# Sheet_1_2022-11-05.net
KiCad netlist of a schematic drawn in Altium Designer
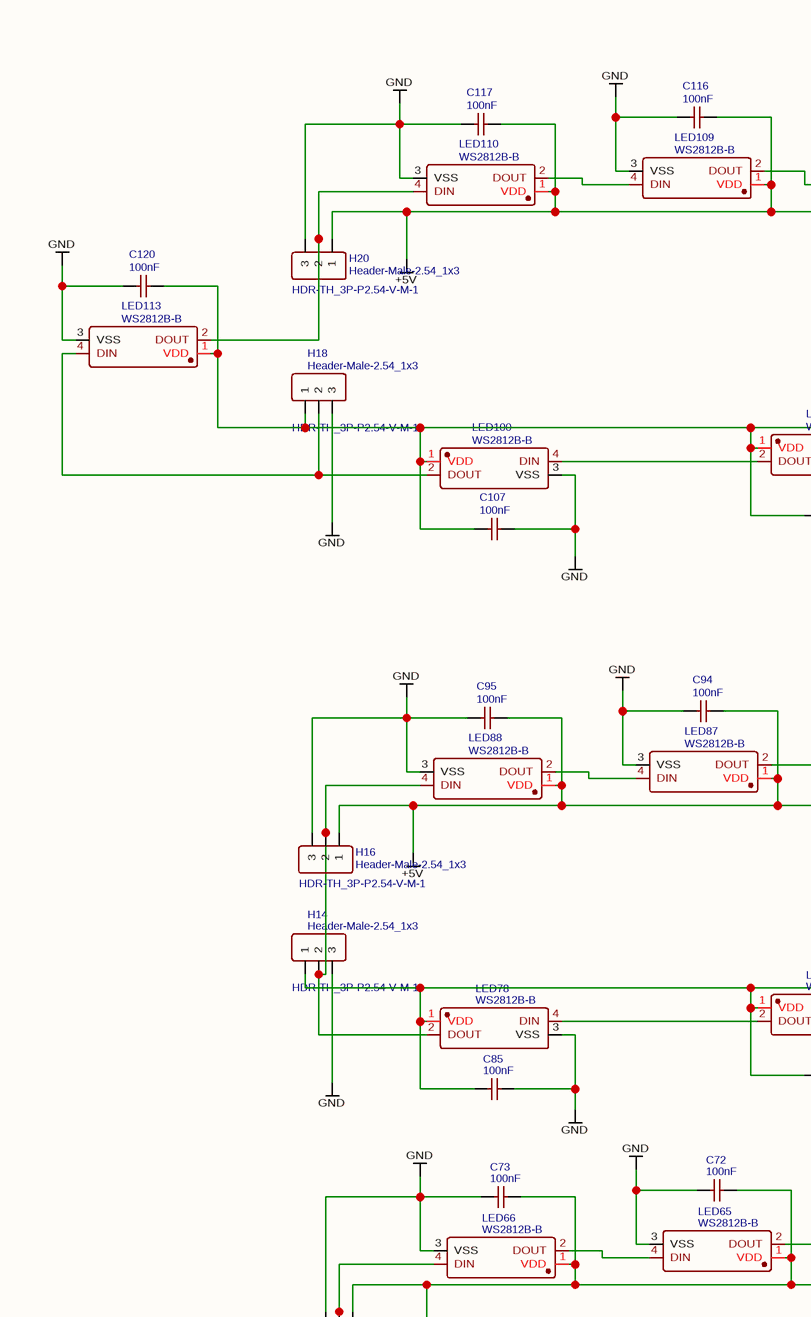
[diagram p0: Sheet_1_2022-11-05.schdoc, top left]
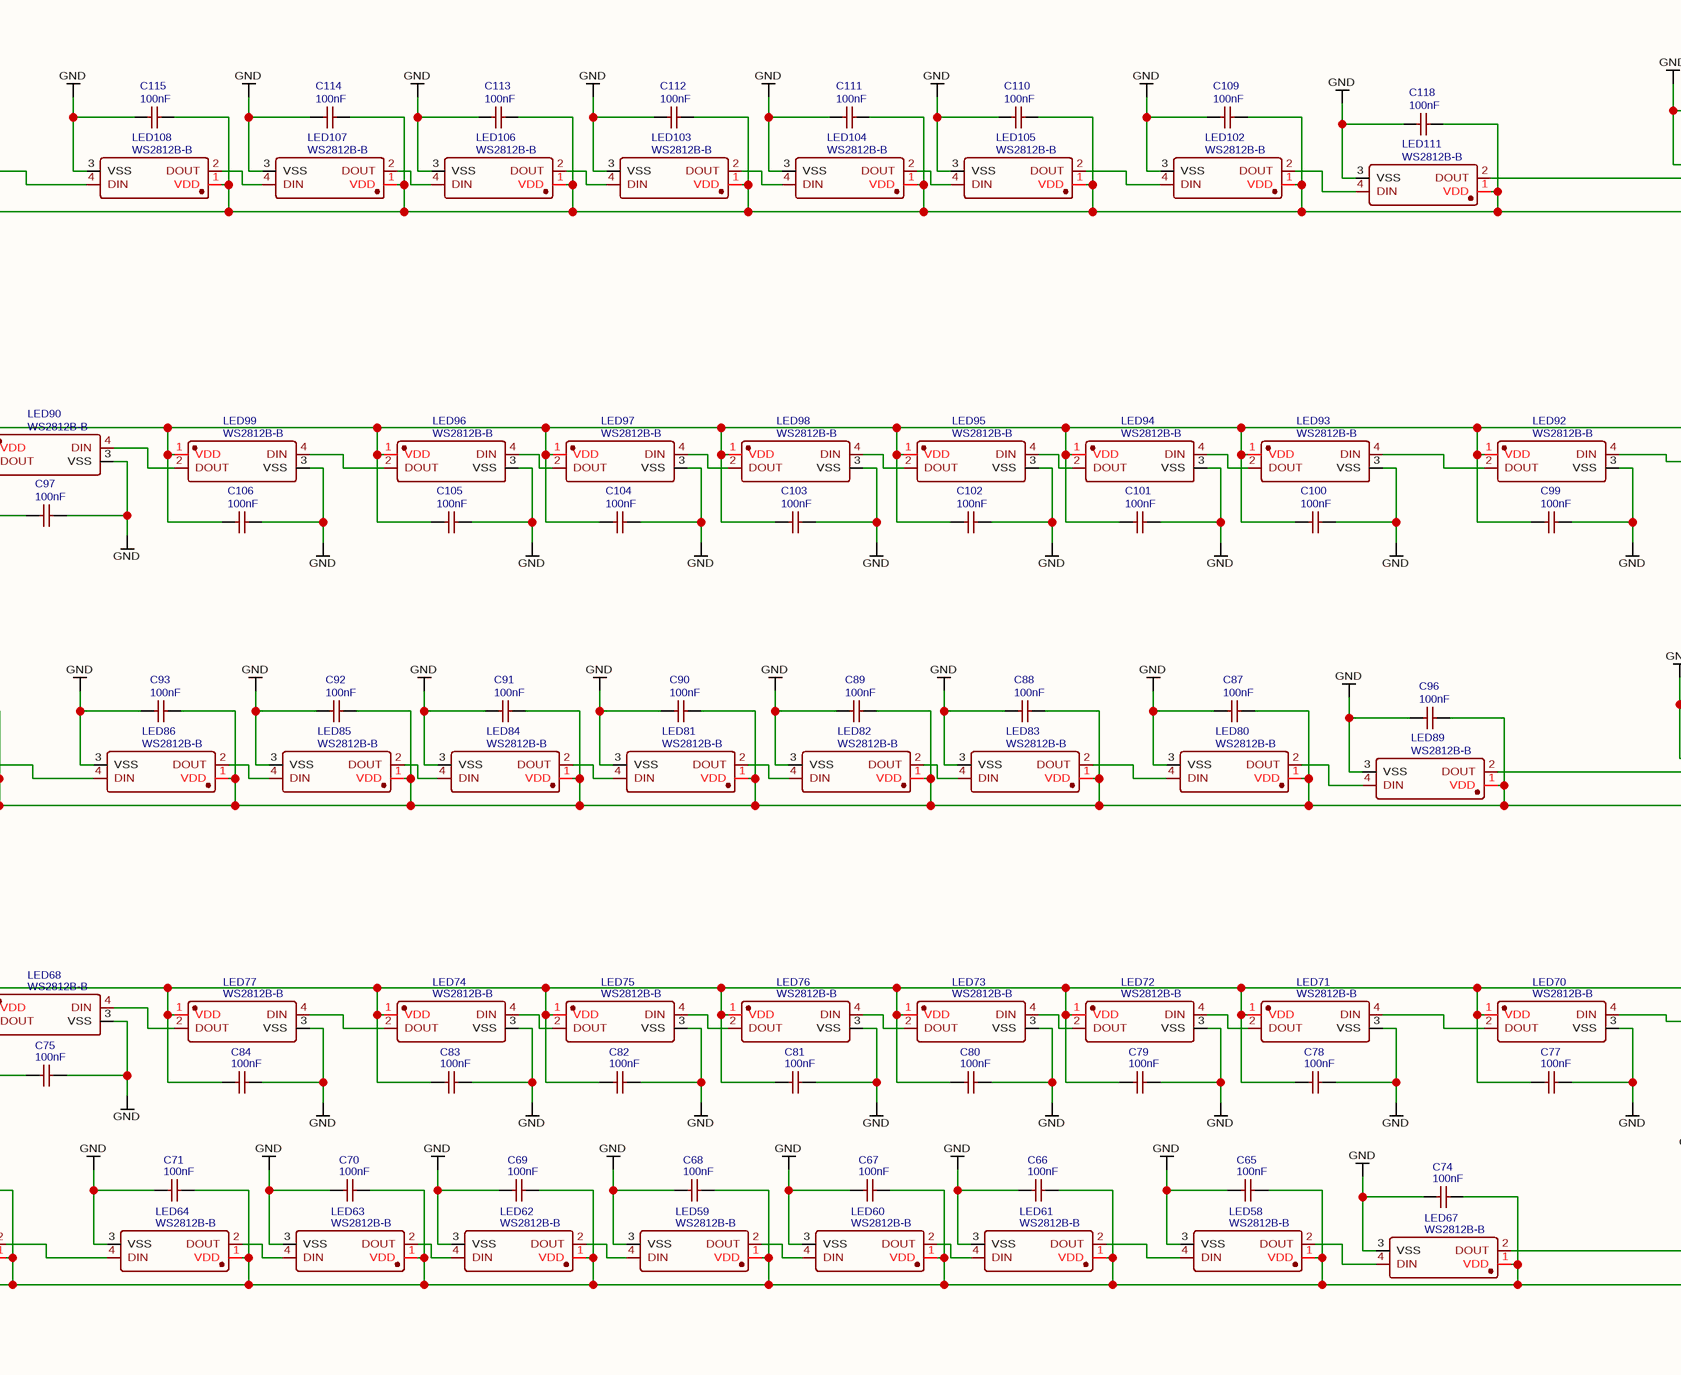
[diagram p1: Sheet_1_2022-11-05.schdoc, top middle]
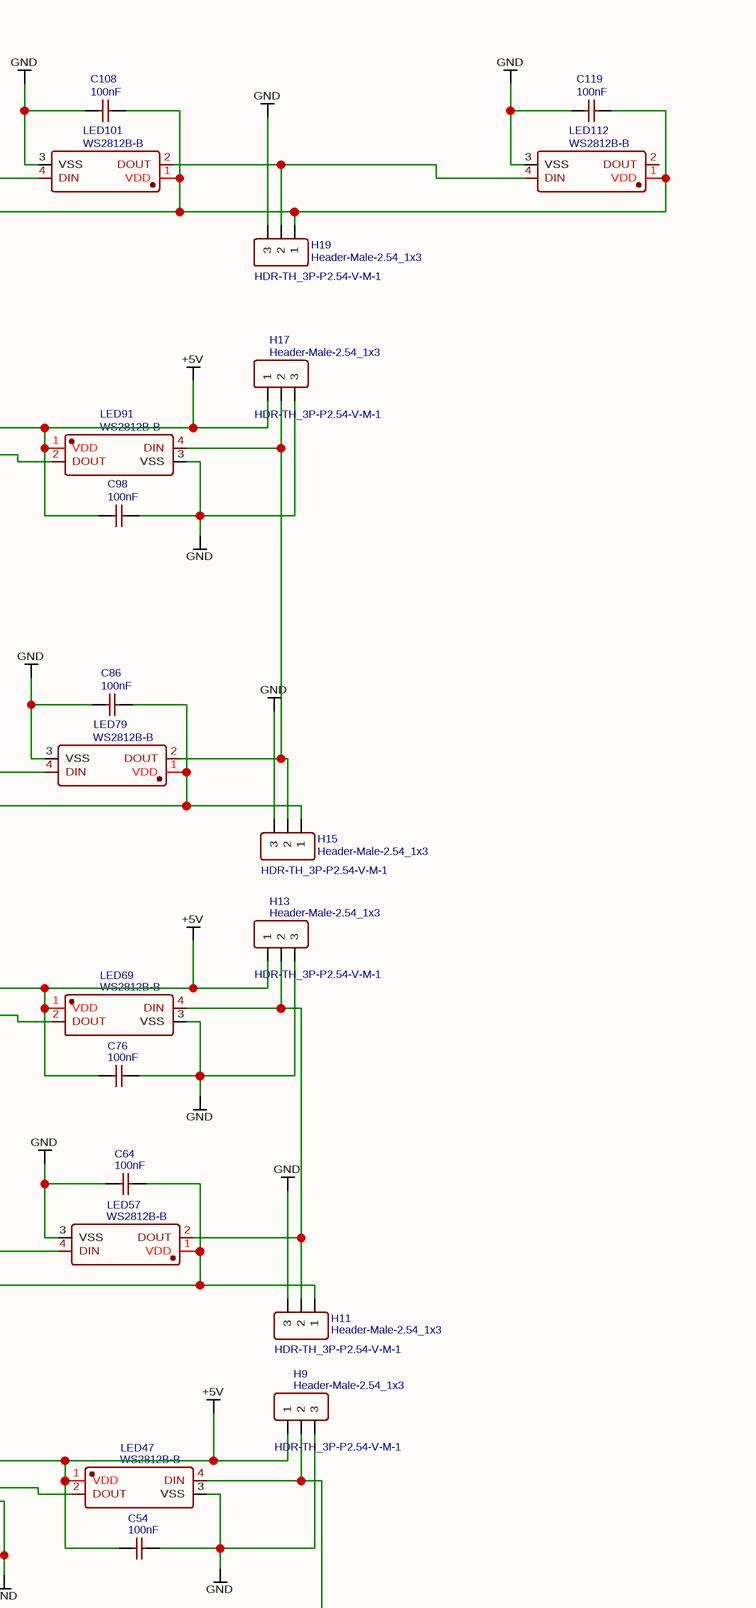
[diagram p2: Sheet_1_2022-11-05.schdoc, top right]
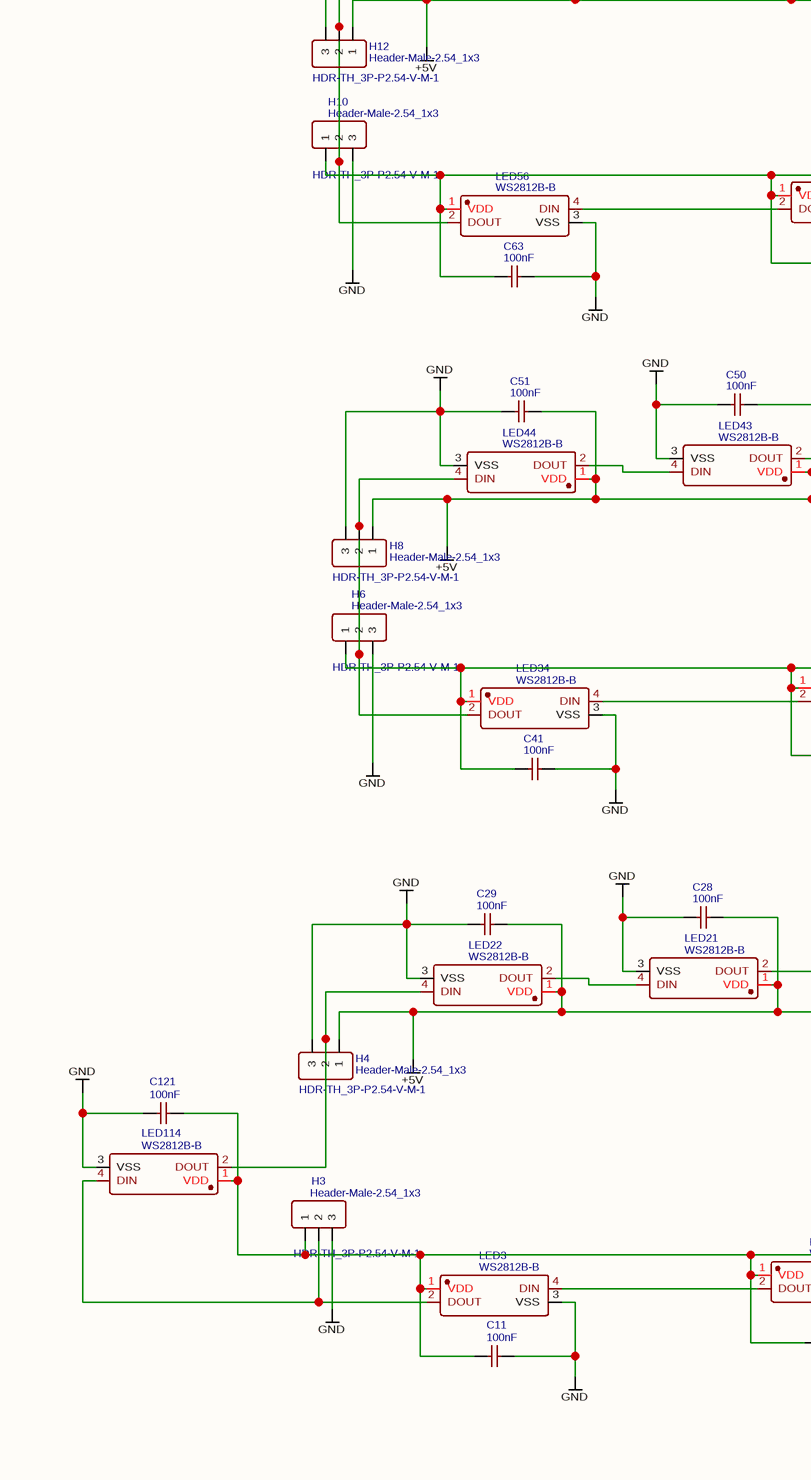
[diagram p3: Sheet_1_2022-11-05.schdoc, centre left]
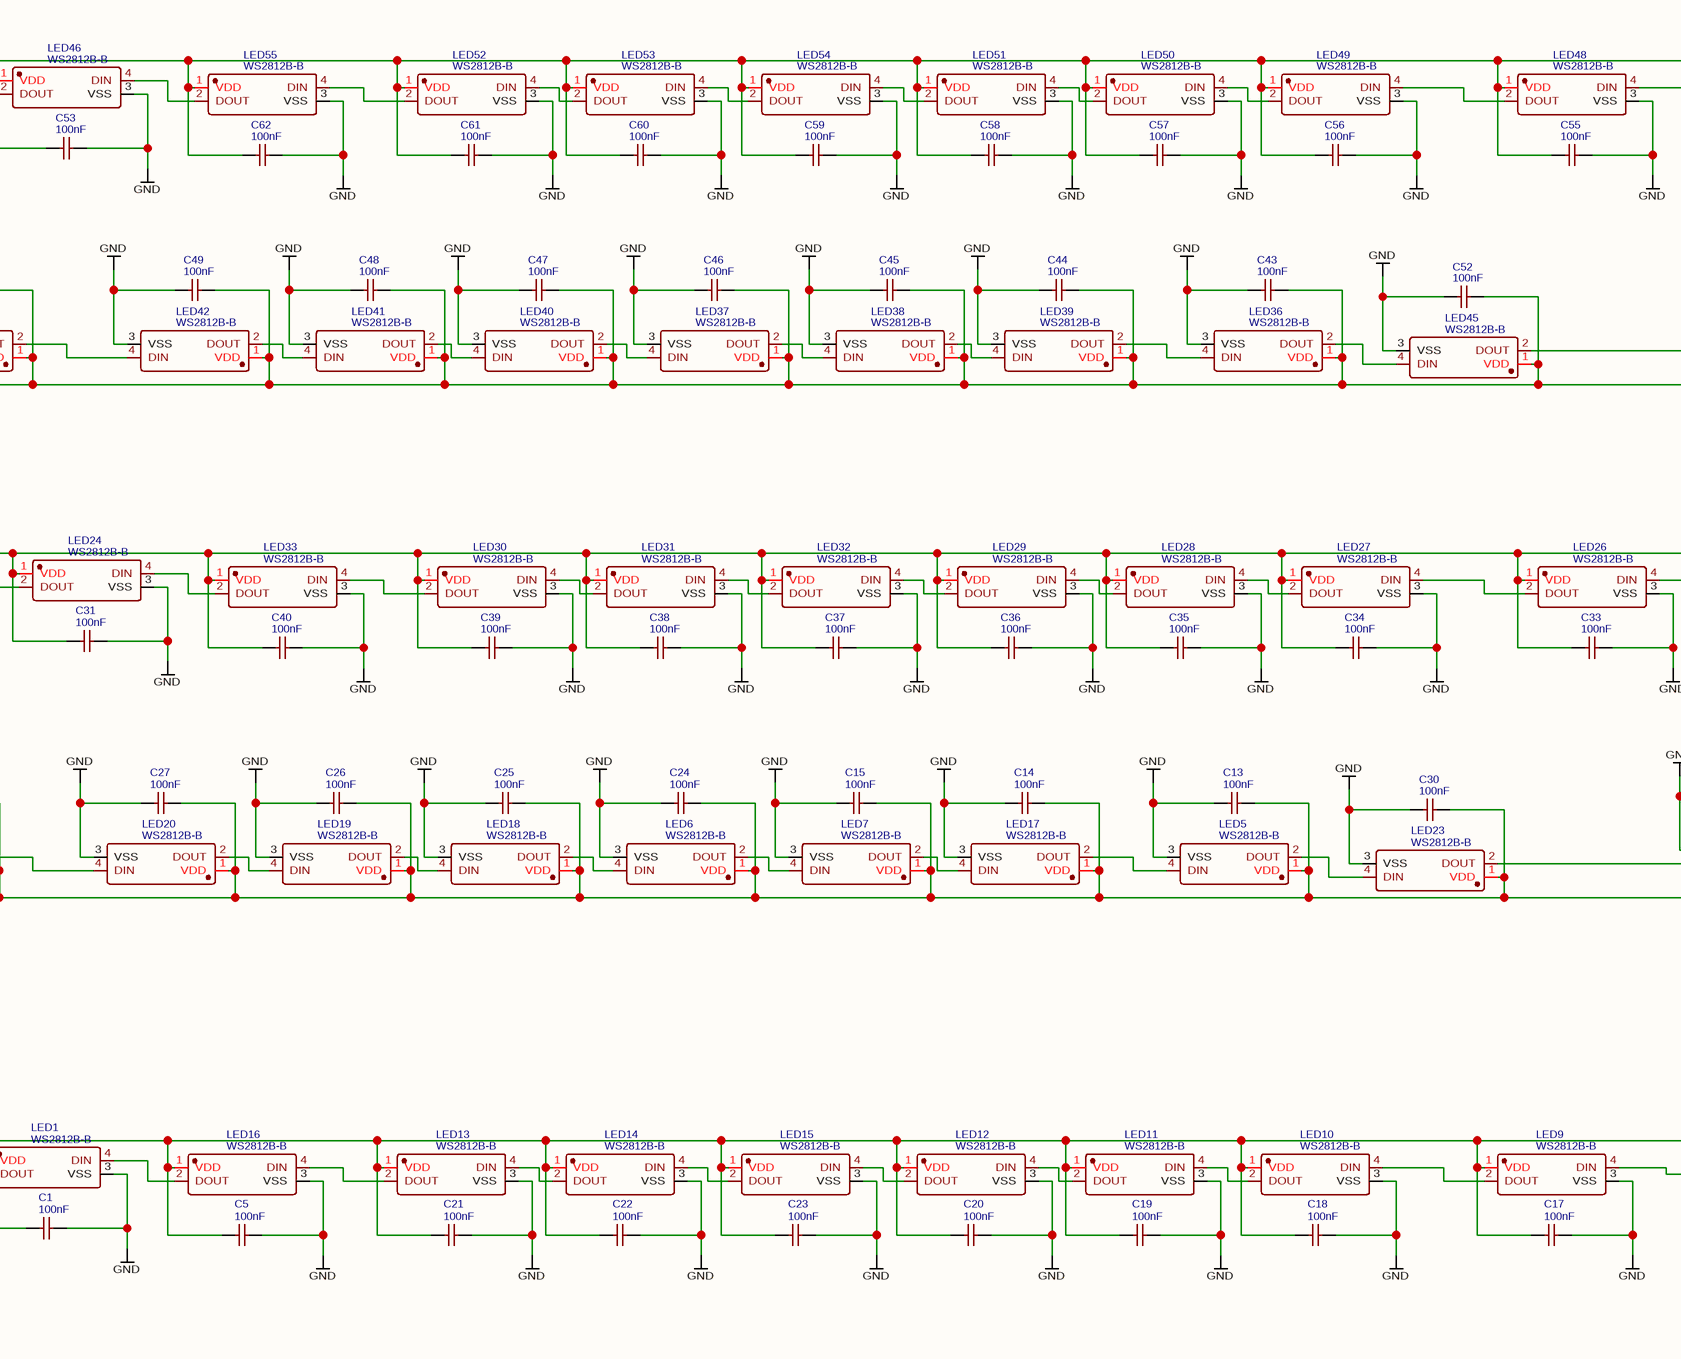
[diagram p4: Sheet_1_2022-11-05.schdoc, centre middle]
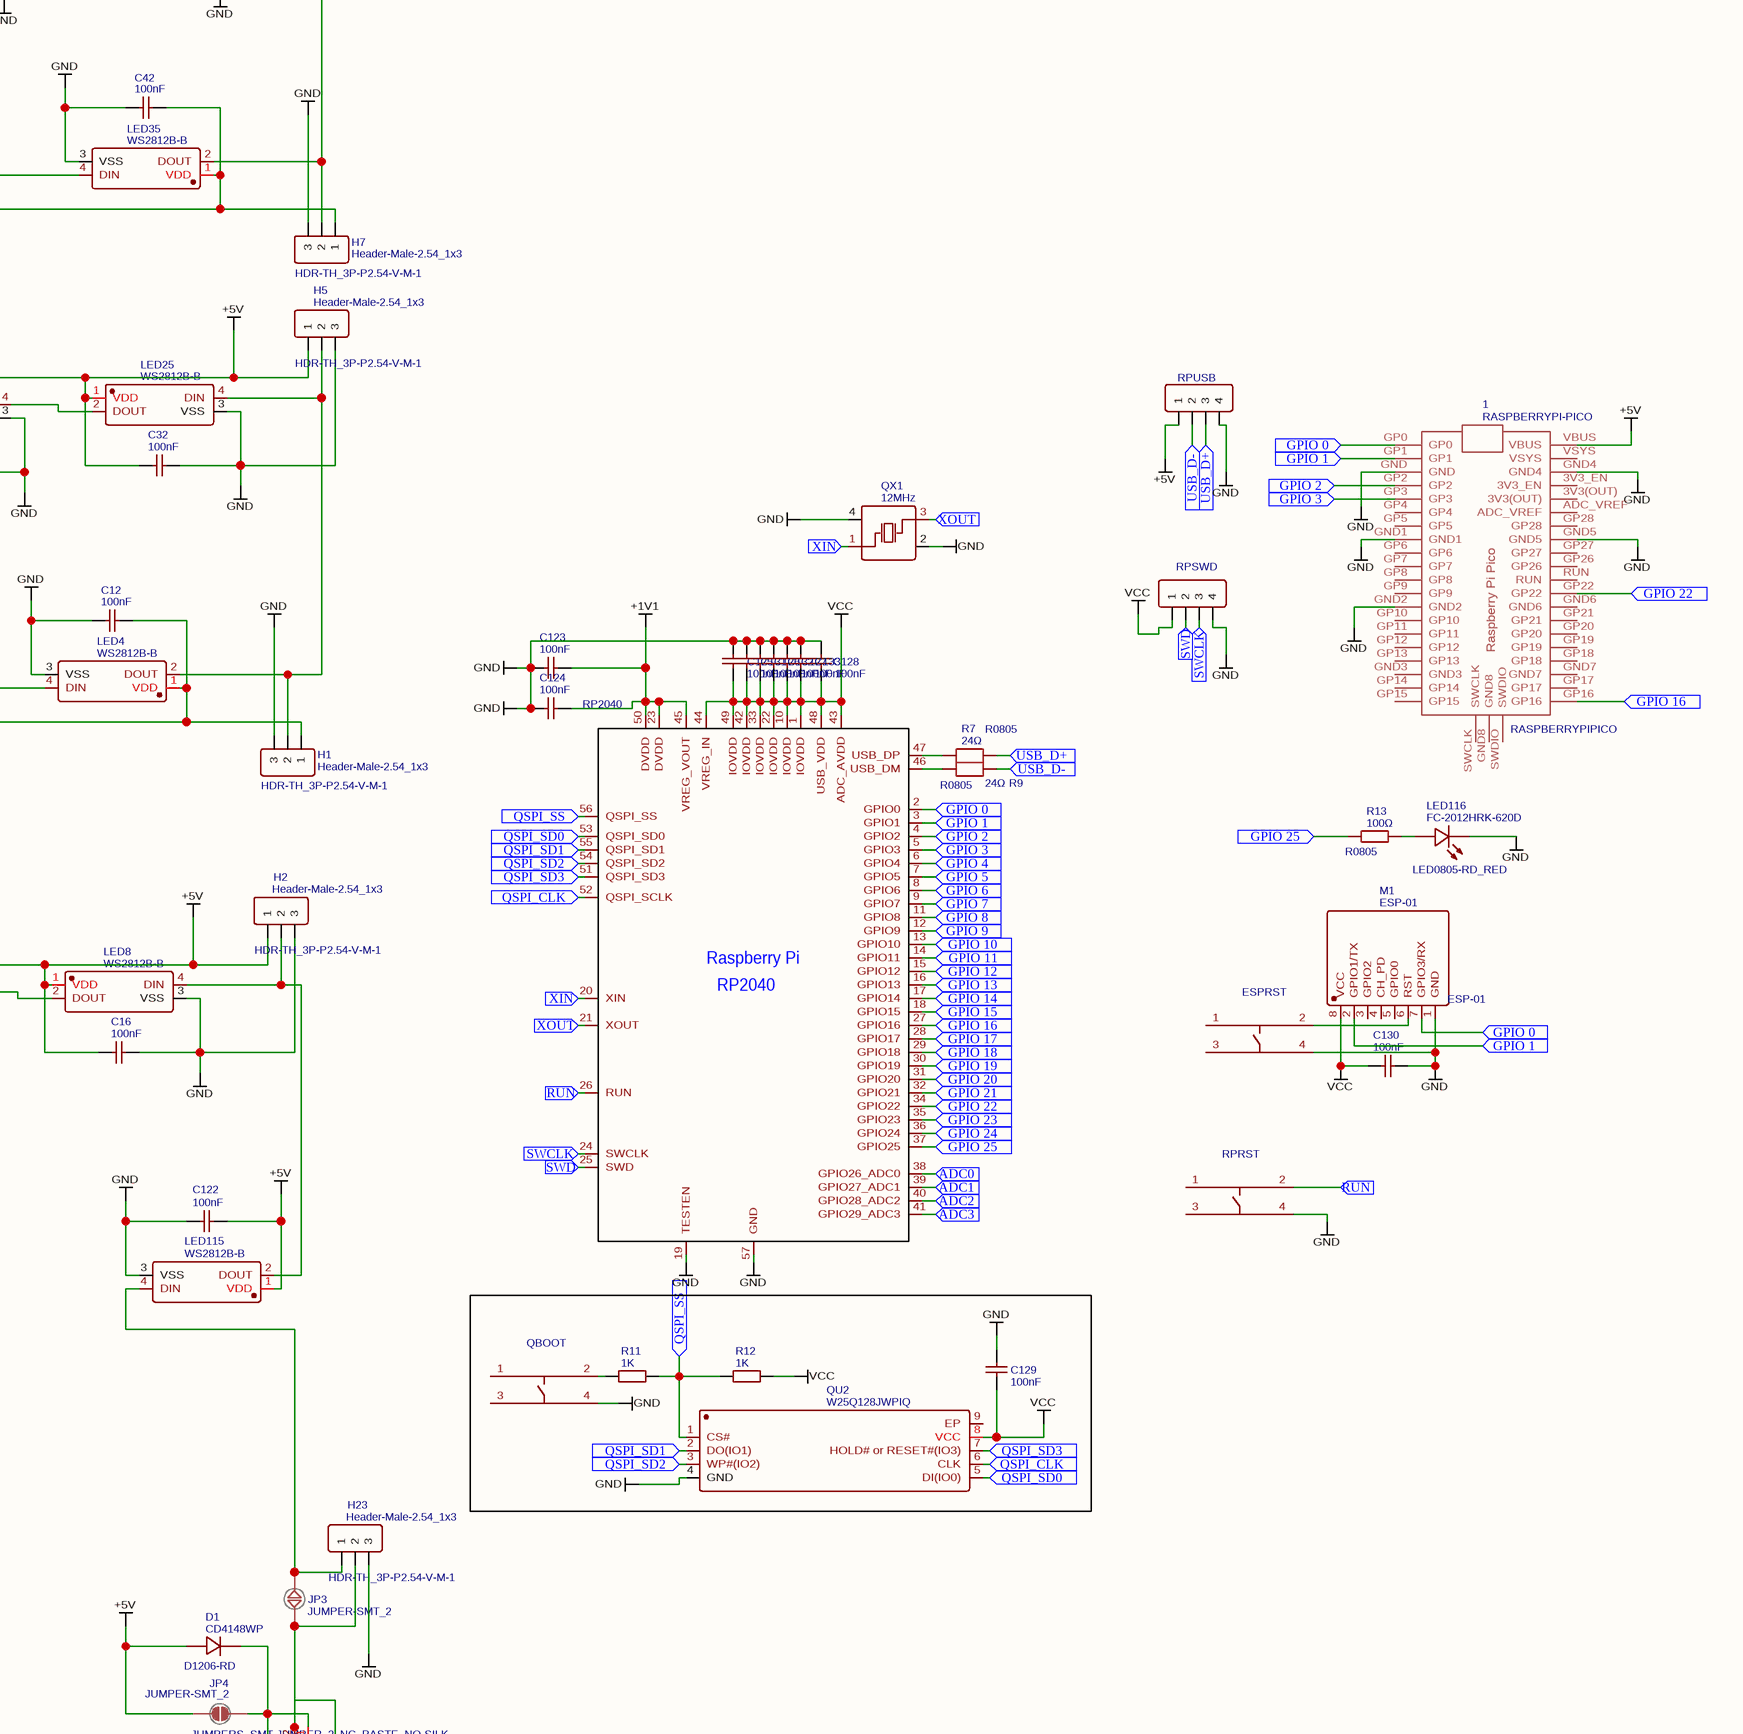
[diagram p5: Sheet_1_2022-11-05.schdoc, centre right]
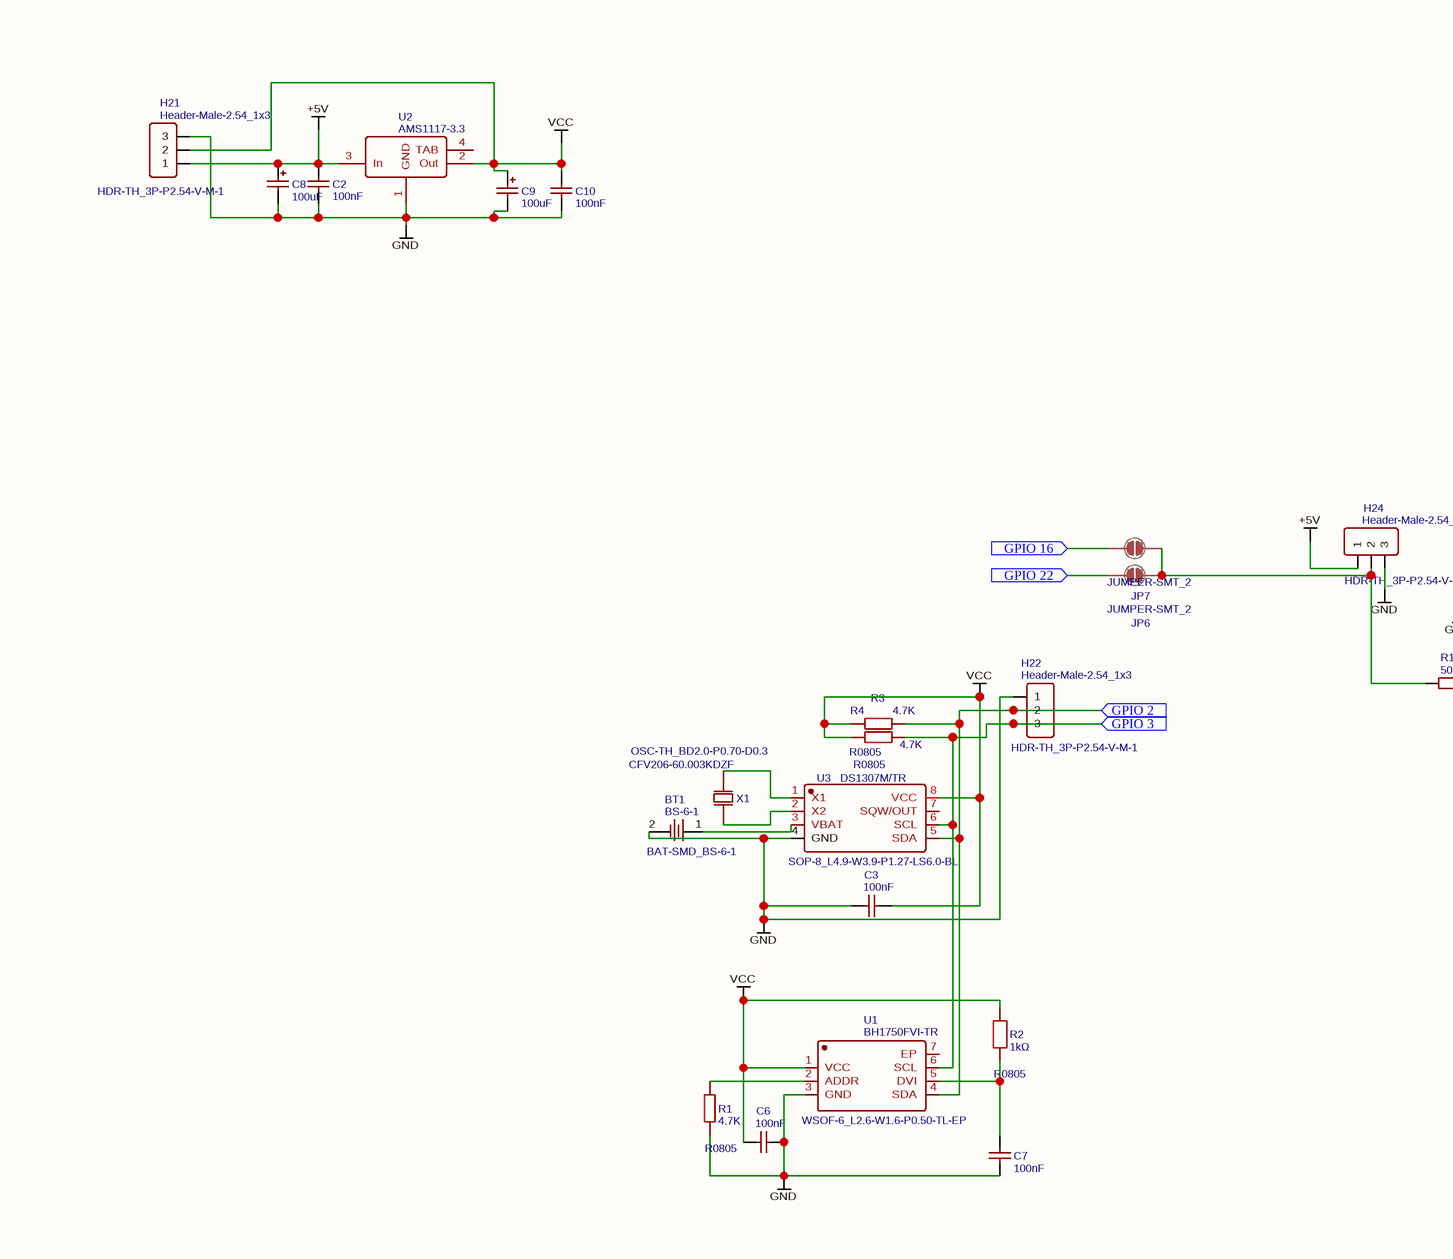
[diagram p6: Sheet_1_2022-11-05.schdoc, bottom middle]
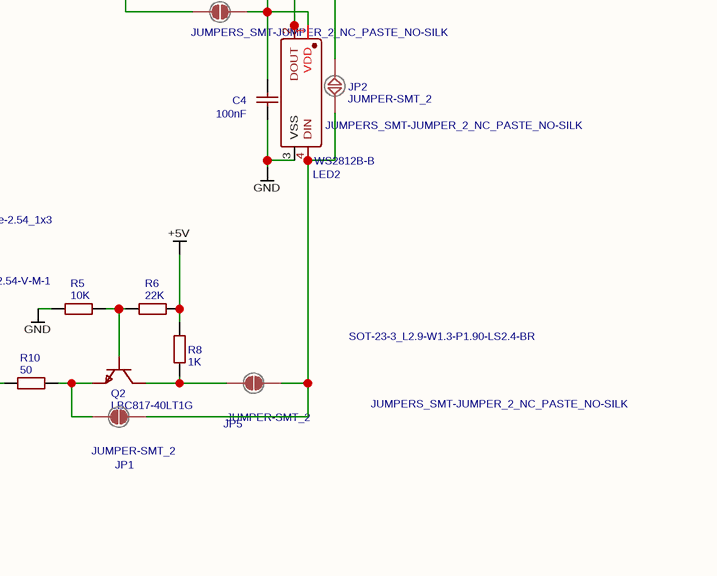
[diagram p7: Sheet_1_2022-11-05.schdoc, bottom right]

(export (version "E")
  (design (tool "Eeschema 10.0.6"))
  (components
    (comp (ref "1")
      (value "RASPBERRYPI-PICO")
      (fields
        (field (name "BOM_MANUFACTURER PART") "RASPBERRY PI PICO")
        (field (name "BOM_SUPPLIER PART") "3643332")
        (field (name "CONTRIBUTOR") "iylee")
      )
      (libsource (lib "altium-import") (part "root_3_RASPBERRYPI-PICO_"))
    )
    (comp (ref "BT1")
      (value "BS-6-1")
      (fields (field (name "BOM_SUPPLIER PART") "C969909") (field (name "CONTRIBUTOR") "LCSC"))
      (libsource (lib "altium-import") (part "root_0_BS-6-1_"))
    )
    (comp (ref "C1")
      (value "100nF")
      (fields
        (field (name "BOM_MANUFACTURER PART") "CC0805KRX7R9BB104")
        (field (name "BOM_SUPPLIER PART") "C49678")
      )
      (libsource (lib "altium-import") (part "root_0_100nF_"))
    )
    (comp (ref "C2")
      (value "100nF")
      (fields
        (field (name "BOM_MANUFACTURER PART") "CC0805KRX7R9BB104")
        (field (name "BOM_SUPPLIER PART") "C49678")
      )
      (libsource (lib "altium-import") (part "root_1_100nF_"))
    )
    (comp (ref "C3")
      (value "100nF")
      (fields
        (field (name "BOM_MANUFACTURER PART") "CC0805KRX7R9BB104")
        (field (name "BOM_SUPPLIER PART") "C49678")
      )
      (libsource (lib "altium-import") (part "root_2_100nF_"))
    )
    (comp (ref "C4")
      (value "100nF")
      (fields
        (field (name "BOM_MANUFACTURER PART") "CC0805KRX7R9BB104")
        (field (name "BOM_SUPPLIER PART") "C49678")
      )
      (libsource (lib "altium-import") (part "root_3_100nF_"))
    )
    (comp (ref "C5")
      (value "100nF")
      (fields
        (field (name "BOM_MANUFACTURER PART") "CC0805KRX7R9BB104")
        (field (name "BOM_SUPPLIER PART") "C49678")
      )
      (libsource (lib "altium-import") (part "root_0_100nF_"))
    )
    (comp (ref "C6")
      (value "100nF")
      (fields
        (field (name "BOM_MANUFACTURER PART") "CC0805KRX7R9BB104")
        (field (name "BOM_SUPPLIER PART") "C49678")
      )
      (libsource (lib "altium-import") (part "root_2_100nF_"))
    )
    (comp (ref "C7")
      (value "100nF")
      (fields
        (field (name "BOM_MANUFACTURER PART") "CC0805KRX7R9BB104")
        (field (name "BOM_SUPPLIER PART") "C49678")
      )
      (libsource (lib "altium-import") (part "root_3_100nF_"))
    )
    (comp (ref "C8")
      (value "100uF")
      (fields
        (field (name "BOM_MANUFACTURER PART") "TAJB107K006RNJ")
        (field (name "BOM_SUPPLIER PART") "C16133")
      )
      (libsource (lib "altium-import") (part "root_3_100uF_"))
    )
    (comp (ref "C9")
      (value "100uF")
      (fields
        (field (name "BOM_MANUFACTURER PART") "TAJB107K006RNJ")
        (field (name "BOM_SUPPLIER PART") "C16133")
      )
      (libsource (lib "altium-import") (part "root_3_100uF_"))
    )
    (comp (ref "C10")
      (value "100nF")
      (fields
        (field (name "BOM_MANUFACTURER PART") "CC0805KRX7R9BB104")
        (field (name "BOM_SUPPLIER PART") "C49678")
      )
      (libsource (lib "altium-import") (part "root_1_100nF_"))
    )
    (comp (ref "C11")
      (value "100nF")
      (fields
        (field (name "BOM_MANUFACTURER PART") "CC0805KRX7R9BB104")
        (field (name "BOM_SUPPLIER PART") "C49678")
      )
      (libsource (lib "altium-import") (part "root_0_100nF_"))
    )
    (comp (ref "C12")
      (value "100nF")
      (fields
        (field (name "BOM_MANUFACTURER PART") "CC0805KRX7R9BB104")
        (field (name "BOM_SUPPLIER PART") "C49678")
      )
      (libsource (lib "altium-import") (part "root_2_100nF_"))
    )
    (comp (ref "C13")
      (value "100nF")
      (fields
        (field (name "BOM_MANUFACTURER PART") "CC0805KRX7R9BB104")
        (field (name "BOM_SUPPLIER PART") "C49678")
      )
      (libsource (lib "altium-import") (part "root_2_100nF_"))
    )
    (comp (ref "C14")
      (value "100nF")
      (fields
        (field (name "BOM_MANUFACTURER PART") "CC0805KRX7R9BB104")
        (field (name "BOM_SUPPLIER PART") "C49678")
      )
      (libsource (lib "altium-import") (part "root_2_100nF_"))
    )
    (comp (ref "C15")
      (value "100nF")
      (fields
        (field (name "BOM_MANUFACTURER PART") "CC0805KRX7R9BB104")
        (field (name "BOM_SUPPLIER PART") "C49678")
      )
      (libsource (lib "altium-import") (part "root_2_100nF_"))
    )
    (comp (ref "C16")
      (value "100nF")
      (fields
        (field (name "BOM_MANUFACTURER PART") "CC0805KRX7R9BB104")
        (field (name "BOM_SUPPLIER PART") "C49678")
      )
      (libsource (lib "altium-import") (part "root_0_100nF_"))
    )
    (comp (ref "C17")
      (value "100nF")
      (fields
        (field (name "BOM_MANUFACTURER PART") "CC0805KRX7R9BB104")
        (field (name "BOM_SUPPLIER PART") "C49678")
      )
      (libsource (lib "altium-import") (part "root_0_100nF_"))
    )
    (comp (ref "C18")
      (value "100nF")
      (fields
        (field (name "BOM_MANUFACTURER PART") "CC0805KRX7R9BB104")
        (field (name "BOM_SUPPLIER PART") "C49678")
      )
      (libsource (lib "altium-import") (part "root_0_100nF_"))
    )
    (comp (ref "C19")
      (value "100nF")
      (fields
        (field (name "BOM_MANUFACTURER PART") "CC0805KRX7R9BB104")
        (field (name "BOM_SUPPLIER PART") "C49678")
      )
      (libsource (lib "altium-import") (part "root_0_100nF_"))
    )
    (comp (ref "C20")
      (value "100nF")
      (fields
        (field (name "BOM_MANUFACTURER PART") "CC0805KRX7R9BB104")
        (field (name "BOM_SUPPLIER PART") "C49678")
      )
      (libsource (lib "altium-import") (part "root_0_100nF_"))
    )
    (comp (ref "C21")
      (value "100nF")
      (fields
        (field (name "BOM_MANUFACTURER PART") "CC0805KRX7R9BB104")
        (field (name "BOM_SUPPLIER PART") "C49678")
      )
      (libsource (lib "altium-import") (part "root_0_100nF_"))
    )
    (comp (ref "C22")
      (value "100nF")
      (fields
        (field (name "BOM_MANUFACTURER PART") "CC0805KRX7R9BB104")
        (field (name "BOM_SUPPLIER PART") "C49678")
      )
      (libsource (lib "altium-import") (part "root_0_100nF_"))
    )
    (comp (ref "C23")
      (value "100nF")
      (fields
        (field (name "BOM_MANUFACTURER PART") "CC0805KRX7R9BB104")
        (field (name "BOM_SUPPLIER PART") "C49678")
      )
      (libsource (lib "altium-import") (part "root_0_100nF_"))
    )
    (comp (ref "C24")
      (value "100nF")
      (fields
        (field (name "BOM_MANUFACTURER PART") "CC0805KRX7R9BB104")
        (field (name "BOM_SUPPLIER PART") "C49678")
      )
      (libsource (lib "altium-import") (part "root_2_100nF_"))
    )
    (comp (ref "C25")
      (value "100nF")
      (fields
        (field (name "BOM_MANUFACTURER PART") "CC0805KRX7R9BB104")
        (field (name "BOM_SUPPLIER PART") "C49678")
      )
      (libsource (lib "altium-import") (part "root_2_100nF_"))
    )
    (comp (ref "C26")
      (value "100nF")
      (fields
        (field (name "BOM_MANUFACTURER PART") "CC0805KRX7R9BB104")
        (field (name "BOM_SUPPLIER PART") "C49678")
      )
      (libsource (lib "altium-import") (part "root_2_100nF_"))
    )
    (comp (ref "C27")
      (value "100nF")
      (fields
        (field (name "BOM_MANUFACTURER PART") "CC0805KRX7R9BB104")
        (field (name "BOM_SUPPLIER PART") "C49678")
      )
      (libsource (lib "altium-import") (part "root_2_100nF_"))
    )
    (comp (ref "C28")
      (value "100nF")
      (fields
        (field (name "BOM_MANUFACTURER PART") "CC0805KRX7R9BB104")
        (field (name "BOM_SUPPLIER PART") "C49678")
      )
      (libsource (lib "altium-import") (part "root_2_100nF_"))
    )
    (comp (ref "C29")
      (value "100nF")
      (fields
        (field (name "BOM_MANUFACTURER PART") "CC0805KRX7R9BB104")
        (field (name "BOM_SUPPLIER PART") "C49678")
      )
      (libsource (lib "altium-import") (part "root_2_100nF_"))
    )
    (comp (ref "C30")
      (value "100nF")
      (fields
        (field (name "BOM_MANUFACTURER PART") "CC0805KRX7R9BB104")
        (field (name "BOM_SUPPLIER PART") "C49678")
      )
      (libsource (lib "altium-import") (part "root_2_100nF_"))
    )
    (comp (ref "C31")
      (value "100nF")
      (fields
        (field (name "BOM_MANUFACTURER PART") "CC0805KRX7R9BB104")
        (field (name "BOM_SUPPLIER PART") "C49678")
      )
      (libsource (lib "altium-import") (part "root_0_100nF_"))
    )
    (comp (ref "C32")
      (value "100nF")
      (fields
        (field (name "BOM_MANUFACTURER PART") "CC0805KRX7R9BB104")
        (field (name "BOM_SUPPLIER PART") "C49678")
      )
      (libsource (lib "altium-import") (part "root_0_100nF_"))
    )
    (comp (ref "C33")
      (value "100nF")
      (fields
        (field (name "BOM_MANUFACTURER PART") "CC0805KRX7R9BB104")
        (field (name "BOM_SUPPLIER PART") "C49678")
      )
      (libsource (lib "altium-import") (part "root_0_100nF_"))
    )
    (comp (ref "C34")
      (value "100nF")
      (fields
        (field (name "BOM_MANUFACTURER PART") "CC0805KRX7R9BB104")
        (field (name "BOM_SUPPLIER PART") "C49678")
      )
      (libsource (lib "altium-import") (part "root_0_100nF_"))
    )
    (comp (ref "C35")
      (value "100nF")
      (fields
        (field (name "BOM_MANUFACTURER PART") "CC0805KRX7R9BB104")
        (field (name "BOM_SUPPLIER PART") "C49678")
      )
      (libsource (lib "altium-import") (part "root_0_100nF_"))
    )
    (comp (ref "C36")
      (value "100nF")
      (fields
        (field (name "BOM_MANUFACTURER PART") "CC0805KRX7R9BB104")
        (field (name "BOM_SUPPLIER PART") "C49678")
      )
      (libsource (lib "altium-import") (part "root_0_100nF_"))
    )
    (comp (ref "C37")
      (value "100nF")
      (fields
        (field (name "BOM_MANUFACTURER PART") "CC0805KRX7R9BB104")
        (field (name "BOM_SUPPLIER PART") "C49678")
      )
      (libsource (lib "altium-import") (part "root_0_100nF_"))
    )
    (comp (ref "C38")
      (value "100nF")
      (fields
        (field (name "BOM_MANUFACTURER PART") "CC0805KRX7R9BB104")
        (field (name "BOM_SUPPLIER PART") "C49678")
      )
      (libsource (lib "altium-import") (part "root_0_100nF_"))
    )
    (comp (ref "C39")
      (value "100nF")
      (fields
        (field (name "BOM_MANUFACTURER PART") "CC0805KRX7R9BB104")
        (field (name "BOM_SUPPLIER PART") "C49678")
      )
      (libsource (lib "altium-import") (part "root_0_100nF_"))
    )
    (comp (ref "C40")
      (value "100nF")
      (fields
        (field (name "BOM_MANUFACTURER PART") "CC0805KRX7R9BB104")
        (field (name "BOM_SUPPLIER PART") "C49678")
      )
      (libsource (lib "altium-import") (part "root_0_100nF_"))
    )
    (comp (ref "C41")
      (value "100nF")
      (fields
        (field (name "BOM_MANUFACTURER PART") "CC0805KRX7R9BB104")
        (field (name "BOM_SUPPLIER PART") "C49678")
      )
      (libsource (lib "altium-import") (part "root_0_100nF_"))
    )
    (comp (ref "C42")
      (value "100nF")
      (fields
        (field (name "BOM_MANUFACTURER PART") "CC0805KRX7R9BB104")
        (field (name "BOM_SUPPLIER PART") "C49678")
      )
      (libsource (lib "altium-import") (part "root_2_100nF_"))
    )
    (comp (ref "C43")
      (value "100nF")
      (fields
        (field (name "BOM_MANUFACTURER PART") "CC0805KRX7R9BB104")
        (field (name "BOM_SUPPLIER PART") "C49678")
      )
      (libsource (lib "altium-import") (part "root_2_100nF_"))
    )
    (comp (ref "C44")
      (value "100nF")
      (fields
        (field (name "BOM_MANUFACTURER PART") "CC0805KRX7R9BB104")
        (field (name "BOM_SUPPLIER PART") "C49678")
      )
      (libsource (lib "altium-import") (part "root_2_100nF_"))
    )
    (comp (ref "C45")
      (value "100nF")
      (fields
        (field (name "BOM_MANUFACTURER PART") "CC0805KRX7R9BB104")
        (field (name "BOM_SUPPLIER PART") "C49678")
      )
      (libsource (lib "altium-import") (part "root_2_100nF_"))
    )
    (comp (ref "C46")
      (value "100nF")
      (fields
        (field (name "BOM_MANUFACTURER PART") "CC0805KRX7R9BB104")
        (field (name "BOM_SUPPLIER PART") "C49678")
      )
      (libsource (lib "altium-import") (part "root_2_100nF_"))
    )
    (comp (ref "C47")
      (value "100nF")
      (fields
        (field (name "BOM_MANUFACTURER PART") "CC0805KRX7R9BB104")
        (field (name "BOM_SUPPLIER PART") "C49678")
      )
      (libsource (lib "altium-import") (part "root_2_100nF_"))
    )
    (comp (ref "C48")
      (value "100nF")
      (fields
        (field (name "BOM_MANUFACTURER PART") "CC0805KRX7R9BB104")
        (field (name "BOM_SUPPLIER PART") "C49678")
      )
      (libsource (lib "altium-import") (part "root_2_100nF_"))
    )
    (comp (ref "C49")
      (value "100nF")
      (fields
        (field (name "BOM_MANUFACTURER PART") "CC0805KRX7R9BB104")
        (field (name "BOM_SUPPLIER PART") "C49678")
      )
      (libsource (lib "altium-import") (part "root_2_100nF_"))
    )
    (comp (ref "C50")
      (value "100nF")
      (fields
        (field (name "BOM_MANUFACTURER PART") "CC0805KRX7R9BB104")
        (field (name "BOM_SUPPLIER PART") "C49678")
      )
      (libsource (lib "altium-import") (part "root_2_100nF_"))
    )
    (comp (ref "C51")
      (value "100nF")
      (fields
        (field (name "BOM_MANUFACTURER PART") "CC0805KRX7R9BB104")
        (field (name "BOM_SUPPLIER PART") "C49678")
      )
      (libsource (lib "altium-import") (part "root_2_100nF_"))
    )
    (comp (ref "C52")
      (value "100nF")
      (fields
        (field (name "BOM_MANUFACTURER PART") "CC0805KRX7R9BB104")
        (field (name "BOM_SUPPLIER PART") "C49678")
      )
      (libsource (lib "altium-import") (part "root_2_100nF_"))
    )
    (comp (ref "C53")
      (value "100nF")
      (fields
        (field (name "BOM_MANUFACTURER PART") "CC0805KRX7R9BB104")
        (field (name "BOM_SUPPLIER PART") "C49678")
      )
      (libsource (lib "altium-import") (part "root_0_100nF_"))
    )
    (comp (ref "C54")
      (value "100nF")
      (fields
        (field (name "BOM_MANUFACTURER PART") "CC0805KRX7R9BB104")
        (field (name "BOM_SUPPLIER PART") "C49678")
      )
      (libsource (lib "altium-import") (part "root_0_100nF_"))
    )
    (comp (ref "C55")
      (value "100nF")
      (fields
        (field (name "BOM_MANUFACTURER PART") "CC0805KRX7R9BB104")
        (field (name "BOM_SUPPLIER PART") "C49678")
      )
      (libsource (lib "altium-import") (part "root_0_100nF_"))
    )
    (comp (ref "C56")
      (value "100nF")
      (fields
        (field (name "BOM_MANUFACTURER PART") "CC0805KRX7R9BB104")
        (field (name "BOM_SUPPLIER PART") "C49678")
      )
      (libsource (lib "altium-import") (part "root_0_100nF_"))
    )
    (comp (ref "C57")
      (value "100nF")
      (fields
        (field (name "BOM_MANUFACTURER PART") "CC0805KRX7R9BB104")
        (field (name "BOM_SUPPLIER PART") "C49678")
      )
      (libsource (lib "altium-import") (part "root_0_100nF_"))
    )
    (comp (ref "C58")
      (value "100nF")
      (fields
        (field (name "BOM_MANUFACTURER PART") "CC0805KRX7R9BB104")
        (field (name "BOM_SUPPLIER PART") "C49678")
      )
      (libsource (lib "altium-import") (part "root_0_100nF_"))
    )
    (comp (ref "C59")
      (value "100nF")
      (fields
        (field (name "BOM_MANUFACTURER PART") "CC0805KRX7R9BB104")
        (field (name "BOM_SUPPLIER PART") "C49678")
      )
      (libsource (lib "altium-import") (part "root_0_100nF_"))
    )
    (comp (ref "C60")
      (value "100nF")
      (fields
        (field (name "BOM_MANUFACTURER PART") "CC0805KRX7R9BB104")
        (field (name "BOM_SUPPLIER PART") "C49678")
      )
      (libsource (lib "altium-import") (part "root_0_100nF_"))
    )
    (comp (ref "C61")
      (value "100nF")
      (fields
        (field (name "BOM_MANUFACTURER PART") "CC0805KRX7R9BB104")
        (field (name "BOM_SUPPLIER PART") "C49678")
      )
      (libsource (lib "altium-import") (part "root_0_100nF_"))
    )
    (comp (ref "C62")
      (value "100nF")
      (fields
        (field (name "BOM_MANUFACTURER PART") "CC0805KRX7R9BB104")
        (field (name "BOM_SUPPLIER PART") "C49678")
      )
      (libsource (lib "altium-import") (part "root_0_100nF_"))
    )
    (comp (ref "C63")
      (value "100nF")
      (fields
        (field (name "BOM_MANUFACTURER PART") "CC0805KRX7R9BB104")
        (field (name "BOM_SUPPLIER PART") "C49678")
      )
      (libsource (lib "altium-import") (part "root_0_100nF_"))
    )
    (comp (ref "C64")
      (value "100nF")
      (fields
        (field (name "BOM_MANUFACTURER PART") "CC0805KRX7R9BB104")
        (field (name "BOM_SUPPLIER PART") "C49678")
      )
      (libsource (lib "altium-import") (part "root_2_100nF_"))
    )
    (comp (ref "C65")
      (value "100nF")
      (fields
        (field (name "BOM_MANUFACTURER PART") "CC0805KRX7R9BB104")
        (field (name "BOM_SUPPLIER PART") "C49678")
      )
      (libsource (lib "altium-import") (part "root_2_100nF_"))
    )
    (comp (ref "C66")
      (value "100nF")
      (fields
        (field (name "BOM_MANUFACTURER PART") "CC0805KRX7R9BB104")
        (field (name "BOM_SUPPLIER PART") "C49678")
      )
      (libsource (lib "altium-import") (part "root_2_100nF_"))
    )
    (comp (ref "C67")
      (value "100nF")
      (fields
        (field (name "BOM_MANUFACTURER PART") "CC0805KRX7R9BB104")
        (field (name "BOM_SUPPLIER PART") "C49678")
      )
      (libsource (lib "altium-import") (part "root_2_100nF_"))
    )
    (comp (ref "C68")
      (value "100nF")
      (fields
        (field (name "BOM_MANUFACTURER PART") "CC0805KRX7R9BB104")
        (field (name "BOM_SUPPLIER PART") "C49678")
      )
      (libsource (lib "altium-import") (part "root_2_100nF_"))
    )
    (comp (ref "C69")
      (value "100nF")
      (fields
        (field (name "BOM_MANUFACTURER PART") "CC0805KRX7R9BB104")
        (field (name "BOM_SUPPLIER PART") "C49678")
      )
      (libsource (lib "altium-import") (part "root_2_100nF_"))
    )
    (comp (ref "C70")
      (value "100nF")
      (fields
        (field (name "BOM_MANUFACTURER PART") "CC0805KRX7R9BB104")
        (field (name "BOM_SUPPLIER PART") "C49678")
      )
      (libsource (lib "altium-import") (part "root_2_100nF_"))
    )
    (comp (ref "C71")
      (value "100nF")
      (fields
        (field (name "BOM_MANUFACTURER PART") "CC0805KRX7R9BB104")
        (field (name "BOM_SUPPLIER PART") "C49678")
      )
      (libsource (lib "altium-import") (part "root_2_100nF_"))
    )
    (comp (ref "C72")
      (value "100nF")
      (fields
        (field (name "BOM_MANUFACTURER PART") "CC0805KRX7R9BB104")
        (field (name "BOM_SUPPLIER PART") "C49678")
      )
      (libsource (lib "altium-import") (part "root_2_100nF_"))
    )
    (comp (ref "C73")
      (value "100nF")
      (fields
        (field (name "BOM_MANUFACTURER PART") "CC0805KRX7R9BB104")
        (field (name "BOM_SUPPLIER PART") "C49678")
      )
      (libsource (lib "altium-import") (part "root_2_100nF_"))
    )
    (comp (ref "C74")
      (value "100nF")
      (fields
        (field (name "BOM_MANUFACTURER PART") "CC0805KRX7R9BB104")
        (field (name "BOM_SUPPLIER PART") "C49678")
      )
      (libsource (lib "altium-import") (part "root_2_100nF_"))
    )
    (comp (ref "C75")
      (value "100nF")
      (fields
        (field (name "BOM_MANUFACTURER PART") "CC0805KRX7R9BB104")
        (field (name "BOM_SUPPLIER PART") "C49678")
      )
      (libsource (lib "altium-import") (part "root_0_100nF_"))
    )
    (comp (ref "C76")
      (value "100nF")
      (fields
        (field (name "BOM_MANUFACTURER PART") "CC0805KRX7R9BB104")
        (field (name "BOM_SUPPLIER PART") "C49678")
      )
      (libsource (lib "altium-import") (part "root_0_100nF_"))
    )
    (comp (ref "C77")
      (value "100nF")
      (fields
        (field (name "BOM_MANUFACTURER PART") "CC0805KRX7R9BB104")
        (field (name "BOM_SUPPLIER PART") "C49678")
      )
      (libsource (lib "altium-import") (part "root_0_100nF_"))
    )
    (comp (ref "C78")
      (value "100nF")
      (fields
        (field (name "BOM_MANUFACTURER PART") "CC0805KRX7R9BB104")
        (field (name "BOM_SUPPLIER PART") "C49678")
      )
      (libsource (lib "altium-import") (part "root_0_100nF_"))
    )
    (comp (ref "C79")
      (value "100nF")
      (fields
        (field (name "BOM_MANUFACTURER PART") "CC0805KRX7R9BB104")
        (field (name "BOM_SUPPLIER PART") "C49678")
      )
      (libsource (lib "altium-import") (part "root_0_100nF_"))
    )
    (comp (ref "C80")
      (value "100nF")
      (fields
        (field (name "BOM_MANUFACTURER PART") "CC0805KRX7R9BB104")
        (field (name "BOM_SUPPLIER PART") "C49678")
      )
      (libsource (lib "altium-import") (part "root_0_100nF_"))
    )
    (comp (ref "C81")
      (value "100nF")
      (fields
        (field (name "BOM_MANUFACTURER PART") "CC0805KRX7R9BB104")
        (field (name "BOM_SUPPLIER PART") "C49678")
      )
      (libsource (lib "altium-import") (part "root_0_100nF_"))
    )
    (comp (ref "C82")
      (value "100nF")
      (fields
        (field (name "BOM_MANUFACTURER PART") "CC0805KRX7R9BB104")
        (field (name "BOM_SUPPLIER PART") "C49678")
      )
      (libsource (lib "altium-import") (part "root_0_100nF_"))
    )
    (comp (ref "C83")
      (value "100nF")
      (fields
        (field (name "BOM_MANUFACTURER PART") "CC0805KRX7R9BB104")
        (field (name "BOM_SUPPLIER PART") "C49678")
      )
      (libsource (lib "altium-import") (part "root_0_100nF_"))
    )
    (comp (ref "C84")
      (value "100nF")
      (fields
        (field (name "BOM_MANUFACTURER PART") "CC0805KRX7R9BB104")
        (field (name "BOM_SUPPLIER PART") "C49678")
      )
      (libsource (lib "altium-import") (part "root_0_100nF_"))
    )
    (comp (ref "C85")
      (value "100nF")
      (fields
        (field (name "BOM_MANUFACTURER PART") "CC0805KRX7R9BB104")
        (field (name "BOM_SUPPLIER PART") "C49678")
      )
      (libsource (lib "altium-import") (part "root_0_100nF_"))
    )
    (comp (ref "C86")
      (value "100nF")
      (fields
        (field (name "BOM_MANUFACTURER PART") "CC0805KRX7R9BB104")
        (field (name "BOM_SUPPLIER PART") "C49678")
      )
      (libsource (lib "altium-import") (part "root_2_100nF_"))
    )
    (comp (ref "C87")
      (value "100nF")
      (fields
        (field (name "BOM_MANUFACTURER PART") "CC0805KRX7R9BB104")
        (field (name "BOM_SUPPLIER PART") "C49678")
      )
      (libsource (lib "altium-import") (part "root_2_100nF_"))
    )
    (comp (ref "C88")
      (value "100nF")
      (fields
        (field (name "BOM_MANUFACTURER PART") "CC0805KRX7R9BB104")
        (field (name "BOM_SUPPLIER PART") "C49678")
      )
      (libsource (lib "altium-import") (part "root_2_100nF_"))
    )
    (comp (ref "C89")
      (value "100nF")
      (fields
        (field (name "BOM_MANUFACTURER PART") "CC0805KRX7R9BB104")
        (field (name "BOM_SUPPLIER PART") "C49678")
      )
      (libsource (lib "altium-import") (part "root_2_100nF_"))
    )
    (comp (ref "C90")
      (value "100nF")
      (fields
        (field (name "BOM_MANUFACTURER PART") "CC0805KRX7R9BB104")
        (field (name "BOM_SUPPLIER PART") "C49678")
      )
      (libsource (lib "altium-import") (part "root_2_100nF_"))
    )
    (comp (ref "C91")
      (value "100nF")
      (fields
        (field (name "BOM_MANUFACTURER PART") "CC0805KRX7R9BB104")
        (field (name "BOM_SUPPLIER PART") "C49678")
      )
      (libsource (lib "altium-import") (part "root_2_100nF_"))
    )
    (comp (ref "C92")
      (value "100nF")
      (fields
        (field (name "BOM_MANUFACTURER PART") "CC0805KRX7R9BB104")
        (field (name "BOM_SUPPLIER PART") "C49678")
      )
      (libsource (lib "altium-import") (part "root_2_100nF_"))
    )
    (comp (ref "C93")
      (value "100nF")
      (fields
        (field (name "BOM_MANUFACTURER PART") "CC0805KRX7R9BB104")
        (field (name "BOM_SUPPLIER PART") "C49678")
      )
      (libsource (lib "altium-import") (part "root_2_100nF_"))
    )
    (comp (ref "C94")
      (value "100nF")
      (fields
        (field (name "BOM_MANUFACTURER PART") "CC0805KRX7R9BB104")
        (field (name "BOM_SUPPLIER PART") "C49678")
      )
      (libsource (lib "altium-import") (part "root_2_100nF_"))
    )
    (comp (ref "C95")
      (value "100nF")
      (fields
        (field (name "BOM_MANUFACTURER PART") "CC0805KRX7R9BB104")
        (field (name "BOM_SUPPLIER PART") "C49678")
      )
      (libsource (lib "altium-import") (part "root_2_100nF_"))
    )
    (comp (ref "C96")
      (value "100nF")
      (fields
        (field (name "BOM_MANUFACTURER PART") "CC0805KRX7R9BB104")
        (field (name "BOM_SUPPLIER PART") "C49678")
      )
      (libsource (lib "altium-import") (part "root_2_100nF_"))
    )
    (comp (ref "C97")
      (value "100nF")
      (fields
        (field (name "BOM_MANUFACTURER PART") "CC0805KRX7R9BB104")
        (field (name "BOM_SUPPLIER PART") "C49678")
      )
      (libsource (lib "altium-import") (part "root_0_100nF_"))
    )
    (comp (ref "C98")
      (value "100nF")
      (fields
        (field (name "BOM_MANUFACTURER PART") "CC0805KRX7R9BB104")
        (field (name "BOM_SUPPLIER PART") "C49678")
      )
      (libsource (lib "altium-import") (part "root_0_100nF_"))
    )
    (comp (ref "C99")
      (value "100nF")
      (fields
        (field (name "BOM_MANUFACTURER PART") "CC0805KRX7R9BB104")
        (field (name "BOM_SUPPLIER PART") "C49678")
      )
      (libsource (lib "altium-import") (part "root_0_100nF_"))
    )
    (comp (ref "C100")
      (value "100nF")
      (fields
        (field (name "BOM_MANUFACTURER PART") "CC0805KRX7R9BB104")
        (field (name "BOM_SUPPLIER PART") "C49678")
      )
      (libsource (lib "altium-import") (part "root_0_100nF_"))
    )
    (comp (ref "C101")
      (value "100nF")
      (fields
        (field (name "BOM_MANUFACTURER PART") "CC0805KRX7R9BB104")
        (field (name "BOM_SUPPLIER PART") "C49678")
      )
      (libsource (lib "altium-import") (part "root_0_100nF_"))
    )
    (comp (ref "C102")
      (value "100nF")
      (fields
        (field (name "BOM_MANUFACTURER PART") "CC0805KRX7R9BB104")
        (field (name "BOM_SUPPLIER PART") "C49678")
      )
      (libsource (lib "altium-import") (part "root_0_100nF_"))
    )
    (comp (ref "C103")
      (value "100nF")
      (fields
        (field (name "BOM_MANUFACTURER PART") "CC0805KRX7R9BB104")
        (field (name "BOM_SUPPLIER PART") "C49678")
      )
      (libsource (lib "altium-import") (part "root_0_100nF_"))
    )
    (comp (ref "C104")
      (value "100nF")
      (fields
        (field (name "BOM_MANUFACTURER PART") "CC0805KRX7R9BB104")
        (field (name "BOM_SUPPLIER PART") "C49678")
      )
      (libsource (lib "altium-import") (part "root_0_100nF_"))
    )
    (comp (ref "C105")
      (value "100nF")
      (fields
        (field (name "BOM_MANUFACTURER PART") "CC0805KRX7R9BB104")
        (field (name "BOM_SUPPLIER PART") "C49678")
      )
      (libsource (lib "altium-import") (part "root_0_100nF_"))
    )
    (comp (ref "C106")
      (value "100nF")
      (fields
        (field (name "BOM_MANUFACTURER PART") "CC0805KRX7R9BB104")
        (field (name "BOM_SUPPLIER PART") "C49678")
      )
      (libsource (lib "altium-import") (part "root_0_100nF_"))
    )
    (comp (ref "C107")
      (value "100nF")
      (fields
        (field (name "BOM_MANUFACTURER PART") "CC0805KRX7R9BB104")
        (field (name "BOM_SUPPLIER PART") "C49678")
      )
      (libsource (lib "altium-import") (part "root_0_100nF_"))
    )
    (comp (ref "C108")
      (value "100nF")
      (fields
        (field (name "BOM_MANUFACTURER PART") "CC0805KRX7R9BB104")
        (field (name "BOM_SUPPLIER PART") "C49678")
      )
      (libsource (lib "altium-import") (part "root_2_100nF_"))
    )
    (comp (ref "C109")
      (value "100nF")
      (fields
        (field (name "BOM_MANUFACTURER PART") "CC0805KRX7R9BB104")
        (field (name "BOM_SUPPLIER PART") "C49678")
      )
      (libsource (lib "altium-import") (part "root_2_100nF_"))
    )
    (comp (ref "C110")
      (value "100nF")
      (fields
        (field (name "BOM_MANUFACTURER PART") "CC0805KRX7R9BB104")
        (field (name "BOM_SUPPLIER PART") "C49678")
      )
      (libsource (lib "altium-import") (part "root_2_100nF_"))
    )
    (comp (ref "C111")
      (value "100nF")
      (fields
        (field (name "BOM_MANUFACTURER PART") "CC0805KRX7R9BB104")
        (field (name "BOM_SUPPLIER PART") "C49678")
      )
      (libsource (lib "altium-import") (part "root_2_100nF_"))
    )
    (comp (ref "C112")
      (value "100nF")
      (fields
        (field (name "BOM_MANUFACTURER PART") "CC0805KRX7R9BB104")
        (field (name "BOM_SUPPLIER PART") "C49678")
      )
      (libsource (lib "altium-import") (part "root_2_100nF_"))
    )
    (comp (ref "C113")
      (value "100nF")
      (fields
        (field (name "BOM_MANUFACTURER PART") "CC0805KRX7R9BB104")
        (field (name "BOM_SUPPLIER PART") "C49678")
      )
      (libsource (lib "altium-import") (part "root_2_100nF_"))
    )
    (comp (ref "C114")
      (value "100nF")
      (fields
        (field (name "BOM_MANUFACTURER PART") "CC0805KRX7R9BB104")
        (field (name "BOM_SUPPLIER PART") "C49678")
      )
      (libsource (lib "altium-import") (part "root_2_100nF_"))
    )
    (comp (ref "C115")
      (value "100nF")
      (fields
        (field (name "BOM_MANUFACTURER PART") "CC0805KRX7R9BB104")
        (field (name "BOM_SUPPLIER PART") "C49678")
      )
      (libsource (lib "altium-import") (part "root_2_100nF_"))
    )
    (comp (ref "C116")
      (value "100nF")
      (fields
        (field (name "BOM_MANUFACTURER PART") "CC0805KRX7R9BB104")
        (field (name "BOM_SUPPLIER PART") "C49678")
      )
      (libsource (lib "altium-import") (part "root_2_100nF_"))
    )
    (comp (ref "C117")
      (value "100nF")
      (fields
        (field (name "BOM_MANUFACTURER PART") "CC0805KRX7R9BB104")
        (field (name "BOM_SUPPLIER PART") "C49678")
      )
      (libsource (lib "altium-import") (part "root_2_100nF_"))
    )
    (comp (ref "C118")
      (value "100nF")
      (fields
        (field (name "BOM_MANUFACTURER PART") "CC0805KRX7R9BB104")
        (field (name "BOM_SUPPLIER PART") "C49678")
      )
      (libsource (lib "altium-import") (part "root_2_100nF_"))
    )
    (comp (ref "C119")
      (value "100nF")
      (fields
        (field (name "BOM_MANUFACTURER PART") "CC0805KRX7R9BB104")
        (field (name "BOM_SUPPLIER PART") "C49678")
      )
      (libsource (lib "altium-import") (part "root_2_100nF_"))
    )
    (comp (ref "C120")
      (value "100nF")
      (fields
        (field (name "BOM_MANUFACTURER PART") "CC0805KRX7R9BB104")
        (field (name "BOM_SUPPLIER PART") "C49678")
      )
      (libsource (lib "altium-import") (part "root_2_100nF_"))
    )
    (comp (ref "C121")
      (value "100nF")
      (fields
        (field (name "BOM_MANUFACTURER PART") "CC0805KRX7R9BB104")
        (field (name "BOM_SUPPLIER PART") "C49678")
      )
      (libsource (lib "altium-import") (part "root_2_100nF_"))
    )
    (comp (ref "C122")
      (value "100nF")
      (fields
        (field (name "BOM_MANUFACTURER PART") "CC0805KRX7R9BB104")
        (field (name "BOM_SUPPLIER PART") "C49678")
      )
      (libsource (lib "altium-import") (part "root_2_100nF_"))
    )
    (comp (ref "C123")
      (value "100nF")
      (fields
        (field (name "BOM_MANUFACTURER PART") "CC0805KRX7R9BB104")
        (field (name "BOM_SUPPLIER PART") "C49678")
      )
      (libsource (lib "altium-import") (part "root_2_100nF_"))
    )
    (comp (ref "C124")
      (value "100nF")
      (fields
        (field (name "BOM_MANUFACTURER PART") "CC0805KRX7R9BB104")
        (field (name "BOM_SUPPLIER PART") "C49678")
      )
      (libsource (lib "altium-import") (part "root_2_100nF_"))
    )
    (comp (ref "C125")
      (value "100nF")
      (fields
        (field (name "BOM_MANUFACTURER PART") "CC0805KRX7R9BB104")
        (field (name "BOM_SUPPLIER PART") "C49678")
      )
      (libsource (lib "altium-import") (part "root_3_100nF_"))
    )
    (comp (ref "C126")
      (value "100nF")
      (fields
        (field (name "BOM_MANUFACTURER PART") "CC0805KRX7R9BB104")
        (field (name "BOM_SUPPLIER PART") "C49678")
      )
      (libsource (lib "altium-import") (part "root_3_100nF_"))
    )
    (comp (ref "C127")
      (value "100nF")
      (fields
        (field (name "BOM_MANUFACTURER PART") "CC0805KRX7R9BB104")
        (field (name "BOM_SUPPLIER PART") "C49678")
      )
      (libsource (lib "altium-import") (part "root_3_100nF_"))
    )
    (comp (ref "C128")
      (value "100nF")
      (fields
        (field (name "BOM_MANUFACTURER PART") "CC0805KRX7R9BB104")
        (field (name "BOM_SUPPLIER PART") "C49678")
      )
      (libsource (lib "altium-import") (part "root_3_100nF_"))
    )
    (comp (ref "C129")
      (value "100nF")
      (fields
        (field (name "BOM_MANUFACTURER PART") "CC0805KRX7R9BB104")
        (field (name "BOM_SUPPLIER PART") "C49678")
      )
      (libsource (lib "altium-import") (part "root_3_100nF_"))
    )
    (comp (ref "C130")
      (value "100nF")
      (fields
        (field (name "BOM_MANUFACTURER PART") "CC0805KRX7R9BB104")
        (field (name "BOM_SUPPLIER PART") "C49678")
      )
      (libsource (lib "altium-import") (part "root_0_100nF_"))
    )
    (comp (ref "C131")
      (value "100nF")
      (fields
        (field (name "BOM_MANUFACTURER PART") "CC0805KRX7R9BB104")
        (field (name "BOM_SUPPLIER PART") "C49678")
      )
      (libsource (lib "altium-import") (part "root_3_100nF_"))
    )
    (comp (ref "C132")
      (value "100nF")
      (fields
        (field (name "BOM_MANUFACTURER PART") "CC0805KRX7R9BB104")
        (field (name "BOM_SUPPLIER PART") "C49678")
      )
      (libsource (lib "altium-import") (part "root_3_100nF_"))
    )
    (comp (ref "C133")
      (value "100nF")
      (fields
        (field (name "BOM_MANUFACTURER PART") "CC0805KRX7R9BB104")
        (field (name "BOM_SUPPLIER PART") "C49678")
      )
      (libsource (lib "altium-import") (part "root_3_100nF_"))
    )
    (comp (ref "D1")
      (value "CD4148WP")
      (fields (field (name "BOM_SUPPLIER PART") "C109000"))
      (libsource (lib "altium-import") (part "root_2_CD4148WP_"))
    )
    (comp (ref "ESPRST")
      (value "PTS810SJM250SMTRLFS")
      (fields (field (name "BOM_SUPPLIER PART") "C116501") (field (name "CONTRIBUTOR") "LCSC"))
      (libsource (lib "altium-import") (part "root_0_PTS810SJM250SMTRLFS_"))
    )
    (comp (ref "H1")
      (value "Header-Male-2.54_1x3")
      (fields
        (field (name "BOM_MANUFACTURER PART") "Header2.54mm 1*3P")
        (field (name "BOM_SUPPLIER PART") "C49257")
      )
      (libsource (lib "altium-import") (part "root_3_Header-Male-2.54_1x3_"))
    )
    (comp (ref "H2")
      (value "Header-Male-2.54_1x3")
      (fields
        (field (name "BOM_MANUFACTURER PART") "Header2.54mm 1*3P")
        (field (name "BOM_SUPPLIER PART") "C49257")
      )
      (libsource (lib "altium-import") (part "root_1_Header-Male-2.54_1x3_"))
    )
    (comp (ref "H3")
      (value "Header-Male-2.54_1x3")
      (fields
        (field (name "BOM_MANUFACTURER PART") "Header2.54mm 1*3P")
        (field (name "BOM_SUPPLIER PART") "C49257")
      )
      (libsource (lib "altium-import") (part "root_1_Header-Male-2.54_1x3_"))
    )
    (comp (ref "H4")
      (value "Header-Male-2.54_1x3")
      (fields
        (field (name "BOM_MANUFACTURER PART") "Header2.54mm 1*3P")
        (field (name "BOM_SUPPLIER PART") "C49257")
      )
      (libsource (lib "altium-import") (part "root_3_Header-Male-2.54_1x3_"))
    )
    (comp (ref "H5")
      (value "Header-Male-2.54_1x3")
      (fields
        (field (name "BOM_MANUFACTURER PART") "Header2.54mm 1*3P")
        (field (name "BOM_SUPPLIER PART") "C49257")
      )
      (libsource (lib "altium-import") (part "root_1_Header-Male-2.54_1x3_"))
    )
    (comp (ref "H6")
      (value "Header-Male-2.54_1x3")
      (fields
        (field (name "BOM_MANUFACTURER PART") "Header2.54mm 1*3P")
        (field (name "BOM_SUPPLIER PART") "C49257")
      )
      (libsource (lib "altium-import") (part "root_1_Header-Male-2.54_1x3_"))
    )
    (comp (ref "H7")
      (value "Header-Male-2.54_1x3")
      (fields
        (field (name "BOM_MANUFACTURER PART") "Header2.54mm 1*3P")
        (field (name "BOM_SUPPLIER PART") "C49257")
      )
      (libsource (lib "altium-import") (part "root_3_Header-Male-2.54_1x3_"))
    )
    (comp (ref "H8")
      (value "Header-Male-2.54_1x3")
      (fields
        (field (name "BOM_MANUFACTURER PART") "Header2.54mm 1*3P")
        (field (name "BOM_SUPPLIER PART") "C49257")
      )
      (libsource (lib "altium-import") (part "root_3_Header-Male-2.54_1x3_"))
    )
    (comp (ref "H9")
      (value "Header-Male-2.54_1x3")
      (fields
        (field (name "BOM_MANUFACTURER PART") "Header2.54mm 1*3P")
        (field (name "BOM_SUPPLIER PART") "C49257")
      )
      (libsource (lib "altium-import") (part "root_1_Header-Male-2.54_1x3_"))
    )
    (comp (ref "H10")
      (value "Header-Male-2.54_1x3")
      (fields
        (field (name "BOM_MANUFACTURER PART") "Header2.54mm 1*3P")
        (field (name "BOM_SUPPLIER PART") "C49257")
      )
      (libsource (lib "altium-import") (part "root_1_Header-Male-2.54_1x3_"))
    )
    (comp (ref "H11")
      (value "Header-Male-2.54_1x3")
      (fields
        (field (name "BOM_MANUFACTURER PART") "Header2.54mm 1*3P")
        (field (name "BOM_SUPPLIER PART") "C49257")
      )
      (libsource (lib "altium-import") (part "root_3_Header-Male-2.54_1x3_"))
    )
    (comp (ref "H12")
      (value "Header-Male-2.54_1x3")
      (fields
        (field (name "BOM_MANUFACTURER PART") "Header2.54mm 1*3P")
        (field (name "BOM_SUPPLIER PART") "C49257")
      )
      (libsource (lib "altium-import") (part "root_3_Header-Male-2.54_1x3_"))
    )
    (comp (ref "H13")
      (value "Header-Male-2.54_1x3")
      (fields
        (field (name "BOM_MANUFACTURER PART") "Header2.54mm 1*3P")
        (field (name "BOM_SUPPLIER PART") "C49257")
      )
      (libsource (lib "altium-import") (part "root_1_Header-Male-2.54_1x3_"))
    )
    (comp (ref "H14")
      (value "Header-Male-2.54_1x3")
      (fields
        (field (name "BOM_MANUFACTURER PART") "Header2.54mm 1*3P")
        (field (name "BOM_SUPPLIER PART") "C49257")
      )
      (libsource (lib "altium-import") (part "root_1_Header-Male-2.54_1x3_"))
    )
    (comp (ref "H15")
      (value "Header-Male-2.54_1x3")
      (fields
        (field (name "BOM_MANUFACTURER PART") "Header2.54mm 1*3P")
        (field (name "BOM_SUPPLIER PART") "C49257")
      )
      (libsource (lib "altium-import") (part "root_3_Header-Male-2.54_1x3_"))
    )
    (comp (ref "H16")
      (value "Header-Male-2.54_1x3")
      (fields
        (field (name "BOM_MANUFACTURER PART") "Header2.54mm 1*3P")
        (field (name "BOM_SUPPLIER PART") "C49257")
      )
      (libsource (lib "altium-import") (part "root_3_Header-Male-2.54_1x3_"))
    )
    (comp (ref "H17")
      (value "Header-Male-2.54_1x3")
      (fields
        (field (name "BOM_MANUFACTURER PART") "Header2.54mm 1*3P")
        (field (name "BOM_SUPPLIER PART") "C49257")
      )
      (libsource (lib "altium-import") (part "root_1_Header-Male-2.54_1x3_"))
    )
    (comp (ref "H18")
      (value "Header-Male-2.54_1x3")
      (fields
        (field (name "BOM_MANUFACTURER PART") "Header2.54mm 1*3P")
        (field (name "BOM_SUPPLIER PART") "C49257")
      )
      (libsource (lib "altium-import") (part "root_1_Header-Male-2.54_1x3_"))
    )
    (comp (ref "H19")
      (value "Header-Male-2.54_1x3")
      (fields
        (field (name "BOM_MANUFACTURER PART") "Header2.54mm 1*3P")
        (field (name "BOM_SUPPLIER PART") "C49257")
      )
      (libsource (lib "altium-import") (part "root_3_Header-Male-2.54_1x3_"))
    )
    (comp (ref "H20")
      (value "Header-Male-2.54_1x3")
      (fields
        (field (name "BOM_MANUFACTURER PART") "Header2.54mm 1*3P")
        (field (name "BOM_SUPPLIER PART") "C49257")
      )
      (libsource (lib "altium-import") (part "root_3_Header-Male-2.54_1x3_"))
    )
    (comp (ref "H21")
      (value "Header-Male-2.54_1x3")
      (fields
        (field (name "BOM_MANUFACTURER PART") "Header2.54mm 1*3P")
        (field (name "BOM_SUPPLIER PART") "C49257")
      )
      (libsource (lib "altium-import") (part "root_2_Header-Male-2.54_1x3_"))
    )
    (comp (ref "H22")
      (value "Header-Male-2.54_1x3")
      (fields
        (field (name "BOM_MANUFACTURER PART") "Header2.54mm 1*3P")
        (field (name "BOM_SUPPLIER PART") "C49257")
      )
      (libsource (lib "altium-import") (part "root_0_Header-Male-2.54_1x3_"))
    )
    (comp (ref "H23")
      (value "Header-Male-2.54_1x3")
      (fields
        (field (name "BOM_MANUFACTURER PART") "Header2.54mm 1*3P")
        (field (name "BOM_SUPPLIER PART") "C49257")
      )
      (libsource (lib "altium-import") (part "root_1_Header-Male-2.54_1x3_"))
    )
    (comp (ref "H24")
      (value "Header-Male-2.54_1x3")
      (fields
        (field (name "BOM_MANUFACTURER PART") "Header2.54mm 1*3P")
        (field (name "BOM_SUPPLIER PART") "C49257")
      )
      (libsource (lib "altium-import") (part "root_1_Header-Male-2.54_1x3_"))
    )
    (comp (ref "JP1")
      (value "JUMPER-SMT_2")
      (fields (field (name "CONTRIBUTOR") "Celeron"))
      (libsource (lib "altium-import") (part "root_0_JUMPER-SMT_2_"))
    )
    (comp (ref "JP2")
      (value "JUMPER-SMT_2")
      (fields (field (name "CONTRIBUTOR") "Celeron"))
      (libsource (lib "altium-import") (part "root_3_JUMPER-SMT_2_"))
    )
    (comp (ref "JP3")
      (value "JUMPER-SMT_2")
      (fields (field (name "CONTRIBUTOR") "Celeron"))
      (libsource (lib "altium-import") (part "root_3_JUMPER-SMT_2_"))
    )
    (comp (ref "JP4")
      (value "JUMPER-SMT_2")
      (fields (field (name "CONTRIBUTOR") "Celeron"))
      (libsource (lib "altium-import") (part "root_0_JUMPER-SMT_2_"))
    )
    (comp (ref "JP5")
      (value "JUMPER-SMT_2")
      (fields (field (name "CONTRIBUTOR") "Celeron"))
      (libsource (lib "altium-import") (part "root_0_JUMPER-SMT_2_"))
    )
    (comp (ref "JP6")
      (value "JUMPER-SMT_2")
      (fields (field (name "CONTRIBUTOR") "Celeron"))
      (libsource (lib "altium-import") (part "root_0_JUMPER-SMT_2_"))
    )
    (comp (ref "JP7")
      (value "JUMPER-SMT_2")
      (fields (field (name "CONTRIBUTOR") "Celeron"))
      (libsource (lib "altium-import") (part "root_0_JUMPER-SMT_2_"))
    )
    (comp (ref "LED1")
      (value "WS2812B-B")
      (fields (field (name "BOM_SUPPLIER PART") "C114586") (field (name "CONTRIBUTOR") "LCSC"))
      (libsource (lib "altium-import") (part "root_0_WS2812B-B_"))
    )
    (comp (ref "LED2")
      (value "WS2812B-B")
      (fields (field (name "BOM_SUPPLIER PART") "C114586") (field (name "CONTRIBUTOR") "LCSC"))
      (libsource (lib "altium-import") (part "root_3_WS2812B-B_"))
    )
    (comp (ref "LED3")
      (value "WS2812B-B")
      (fields (field (name "BOM_SUPPLIER PART") "C114586") (field (name "CONTRIBUTOR") "LCSC"))
      (libsource (lib "altium-import") (part "root_0_WS2812B-B_"))
    )
    (comp (ref "LED4")
      (value "WS2812B-B")
      (fields (field (name "BOM_SUPPLIER PART") "C114586") (field (name "CONTRIBUTOR") "LCSC"))
      (libsource (lib "altium-import") (part "root_2_WS2812B-B_"))
    )
    (comp (ref "LED5")
      (value "WS2812B-B")
      (fields (field (name "BOM_SUPPLIER PART") "C114586") (field (name "CONTRIBUTOR") "LCSC"))
      (libsource (lib "altium-import") (part "root_2_WS2812B-B_"))
    )
    (comp (ref "LED6")
      (value "WS2812B-B")
      (fields (field (name "BOM_SUPPLIER PART") "C114586") (field (name "CONTRIBUTOR") "LCSC"))
      (libsource (lib "altium-import") (part "root_2_WS2812B-B_"))
    )
    (comp (ref "LED7")
      (value "WS2812B-B")
      (fields (field (name "BOM_SUPPLIER PART") "C114586") (field (name "CONTRIBUTOR") "LCSC"))
      (libsource (lib "altium-import") (part "root_2_WS2812B-B_"))
    )
    (comp (ref "LED8")
      (value "WS2812B-B")
      (fields (field (name "BOM_SUPPLIER PART") "C114586") (field (name "CONTRIBUTOR") "LCSC"))
      (libsource (lib "altium-import") (part "root_0_WS2812B-B_"))
    )
    (comp (ref "LED9")
      (value "WS2812B-B")
      (fields (field (name "BOM_SUPPLIER PART") "C114586") (field (name "CONTRIBUTOR") "LCSC"))
      (libsource (lib "altium-import") (part "root_0_WS2812B-B_"))
    )
    (comp (ref "LED10")
      (value "WS2812B-B")
      (fields (field (name "BOM_SUPPLIER PART") "C114586") (field (name "CONTRIBUTOR") "LCSC"))
      (libsource (lib "altium-import") (part "root_0_WS2812B-B_"))
    )
    (comp (ref "LED11")
      (value "WS2812B-B")
      (fields (field (name "BOM_SUPPLIER PART") "C114586") (field (name "CONTRIBUTOR") "LCSC"))
      (libsource (lib "altium-import") (part "root_0_WS2812B-B_"))
    )
    (comp (ref "LED12")
      (value "WS2812B-B")
      (fields (field (name "BOM_SUPPLIER PART") "C114586") (field (name "CONTRIBUTOR") "LCSC"))
      (libsource (lib "altium-import") (part "root_0_WS2812B-B_"))
    )
    (comp (ref "LED13")
      (value "WS2812B-B")
      (fields (field (name "BOM_SUPPLIER PART") "C114586") (field (name "CONTRIBUTOR") "LCSC"))
      (libsource (lib "altium-import") (part "root_0_WS2812B-B_"))
    )
    (comp (ref "LED14")
      (value "WS2812B-B")
      (fields (field (name "BOM_SUPPLIER PART") "C114586") (field (name "CONTRIBUTOR") "LCSC"))
      (libsource (lib "altium-import") (part "root_0_WS2812B-B_"))
    )
    (comp (ref "LED15")
      (value "WS2812B-B")
      (fields (field (name "BOM_SUPPLIER PART") "C114586") (field (name "CONTRIBUTOR") "LCSC"))
      (libsource (lib "altium-import") (part "root_0_WS2812B-B_"))
    )
    (comp (ref "LED16")
      (value "WS2812B-B")
      (fields (field (name "BOM_SUPPLIER PART") "C114586") (field (name "CONTRIBUTOR") "LCSC"))
      (libsource (lib "altium-import") (part "root_0_WS2812B-B_"))
    )
    (comp (ref "LED17")
      (value "WS2812B-B")
      (fields (field (name "BOM_SUPPLIER PART") "C114586") (field (name "CONTRIBUTOR") "LCSC"))
      (libsource (lib "altium-import") (part "root_2_WS2812B-B_"))
    )
    (comp (ref "LED18")
      (value "WS2812B-B")
      (fields (field (name "BOM_SUPPLIER PART") "C114586") (field (name "CONTRIBUTOR") "LCSC"))
      (libsource (lib "altium-import") (part "root_2_WS2812B-B_"))
    )
    (comp (ref "LED19")
      (value "WS2812B-B")
      (fields (field (name "BOM_SUPPLIER PART") "C114586") (field (name "CONTRIBUTOR") "LCSC"))
      (libsource (lib "altium-import") (part "root_2_WS2812B-B_"))
    )
    (comp (ref "LED20")
      (value "WS2812B-B")
      (fields (field (name "BOM_SUPPLIER PART") "C114586") (field (name "CONTRIBUTOR") "LCSC"))
      (libsource (lib "altium-import") (part "root_2_WS2812B-B_"))
    )
    (comp (ref "LED21")
      (value "WS2812B-B")
      (fields (field (name "BOM_SUPPLIER PART") "C114586") (field (name "CONTRIBUTOR") "LCSC"))
      (libsource (lib "altium-import") (part "root_2_WS2812B-B_"))
    )
    (comp (ref "LED22")
      (value "WS2812B-B")
      (fields (field (name "BOM_SUPPLIER PART") "C114586") (field (name "CONTRIBUTOR") "LCSC"))
      (libsource (lib "altium-import") (part "root_2_WS2812B-B_"))
    )
    (comp (ref "LED23")
      (value "WS2812B-B")
      (fields (field (name "BOM_SUPPLIER PART") "C114586") (field (name "CONTRIBUTOR") "LCSC"))
      (libsource (lib "altium-import") (part "root_2_WS2812B-B_"))
    )
    (comp (ref "LED24")
      (value "WS2812B-B")
      (fields (field (name "BOM_SUPPLIER PART") "C114586") (field (name "CONTRIBUTOR") "LCSC"))
      (libsource (lib "altium-import") (part "root_0_WS2812B-B_"))
    )
    (comp (ref "LED25")
      (value "WS2812B-B")
      (fields (field (name "BOM_SUPPLIER PART") "C114586") (field (name "CONTRIBUTOR") "LCSC"))
      (libsource (lib "altium-import") (part "root_0_WS2812B-B_"))
    )
    (comp (ref "LED26")
      (value "WS2812B-B")
      (fields (field (name "BOM_SUPPLIER PART") "C114586") (field (name "CONTRIBUTOR") "LCSC"))
      (libsource (lib "altium-import") (part "root_0_WS2812B-B_"))
    )
    (comp (ref "LED27")
      (value "WS2812B-B")
      (fields (field (name "BOM_SUPPLIER PART") "C114586") (field (name "CONTRIBUTOR") "LCSC"))
      (libsource (lib "altium-import") (part "root_0_WS2812B-B_"))
    )
    (comp (ref "LED28")
      (value "WS2812B-B")
      (fields (field (name "BOM_SUPPLIER PART") "C114586") (field (name "CONTRIBUTOR") "LCSC"))
      (libsource (lib "altium-import") (part "root_0_WS2812B-B_"))
    )
    (comp (ref "LED29")
      (value "WS2812B-B")
      (fields (field (name "BOM_SUPPLIER PART") "C114586") (field (name "CONTRIBUTOR") "LCSC"))
      (libsource (lib "altium-import") (part "root_0_WS2812B-B_"))
    )
    (comp (ref "LED30")
      (value "WS2812B-B")
      (fields (field (name "BOM_SUPPLIER PART") "C114586") (field (name "CONTRIBUTOR") "LCSC"))
      (libsource (lib "altium-import") (part "root_0_WS2812B-B_"))
    )
    (comp (ref "LED31")
      (value "WS2812B-B")
      (fields (field (name "BOM_SUPPLIER PART") "C114586") (field (name "CONTRIBUTOR") "LCSC"))
      (libsource (lib "altium-import") (part "root_0_WS2812B-B_"))
    )
    (comp (ref "LED32")
      (value "WS2812B-B")
      (fields (field (name "BOM_SUPPLIER PART") "C114586") (field (name "CONTRIBUTOR") "LCSC"))
      (libsource (lib "altium-import") (part "root_0_WS2812B-B_"))
    )
    (comp (ref "LED33")
      (value "WS2812B-B")
      (fields (field (name "BOM_SUPPLIER PART") "C114586") (field (name "CONTRIBUTOR") "LCSC"))
      (libsource (lib "altium-import") (part "root_0_WS2812B-B_"))
    )
    (comp (ref "LED34")
      (value "WS2812B-B")
      (fields (field (name "BOM_SUPPLIER PART") "C114586") (field (name "CONTRIBUTOR") "LCSC"))
      (libsource (lib "altium-import") (part "root_0_WS2812B-B_"))
    )
    (comp (ref "LED35")
      (value "WS2812B-B")
      (fields (field (name "BOM_SUPPLIER PART") "C114586") (field (name "CONTRIBUTOR") "LCSC"))
      (libsource (lib "altium-import") (part "root_2_WS2812B-B_"))
    )
    (comp (ref "LED36")
      (value "WS2812B-B")
      (fields (field (name "BOM_SUPPLIER PART") "C114586") (field (name "CONTRIBUTOR") "LCSC"))
      (libsource (lib "altium-import") (part "root_2_WS2812B-B_"))
    )
    (comp (ref "LED37")
      (value "WS2812B-B")
      (fields (field (name "BOM_SUPPLIER PART") "C114586") (field (name "CONTRIBUTOR") "LCSC"))
      (libsource (lib "altium-import") (part "root_2_WS2812B-B_"))
    )
    (comp (ref "LED38")
      (value "WS2812B-B")
      (fields (field (name "BOM_SUPPLIER PART") "C114586") (field (name "CONTRIBUTOR") "LCSC"))
      (libsource (lib "altium-import") (part "root_2_WS2812B-B_"))
    )
    (comp (ref "LED39")
      (value "WS2812B-B")
      (fields (field (name "BOM_SUPPLIER PART") "C114586") (field (name "CONTRIBUTOR") "LCSC"))
      (libsource (lib "altium-import") (part "root_2_WS2812B-B_"))
    )
    (comp (ref "LED40")
      (value "WS2812B-B")
      (fields (field (name "BOM_SUPPLIER PART") "C114586") (field (name "CONTRIBUTOR") "LCSC"))
      (libsource (lib "altium-import") (part "root_2_WS2812B-B_"))
    )
    (comp (ref "LED41")
      (value "WS2812B-B")
      (fields (field (name "BOM_SUPPLIER PART") "C114586") (field (name "CONTRIBUTOR") "LCSC"))
      (libsource (lib "altium-import") (part "root_2_WS2812B-B_"))
    )
    (comp (ref "LED42")
      (value "WS2812B-B")
      (fields (field (name "BOM_SUPPLIER PART") "C114586") (field (name "CONTRIBUTOR") "LCSC"))
      (libsource (lib "altium-import") (part "root_2_WS2812B-B_"))
    )
    (comp (ref "LED43")
      (value "WS2812B-B")
      (fields (field (name "BOM_SUPPLIER PART") "C114586") (field (name "CONTRIBUTOR") "LCSC"))
      (libsource (lib "altium-import") (part "root_2_WS2812B-B_"))
    )
    (comp (ref "LED44")
      (value "WS2812B-B")
      (fields (field (name "BOM_SUPPLIER PART") "C114586") (field (name "CONTRIBUTOR") "LCSC"))
      (libsource (lib "altium-import") (part "root_2_WS2812B-B_"))
    )
    (comp (ref "LED45")
      (value "WS2812B-B")
      (fields (field (name "BOM_SUPPLIER PART") "C114586") (field (name "CONTRIBUTOR") "LCSC"))
      (libsource (lib "altium-import") (part "root_2_WS2812B-B_"))
    )
    (comp (ref "LED46")
      (value "WS2812B-B")
      (fields (field (name "BOM_SUPPLIER PART") "C114586") (field (name "CONTRIBUTOR") "LCSC"))
      (libsource (lib "altium-import") (part "root_0_WS2812B-B_"))
    )
    (comp (ref "LED47")
      (value "WS2812B-B")
      (fields (field (name "BOM_SUPPLIER PART") "C114586") (field (name "CONTRIBUTOR") "LCSC"))
      (libsource (lib "altium-import") (part "root_0_WS2812B-B_"))
    )
    (comp (ref "LED48")
      (value "WS2812B-B")
      (fields (field (name "BOM_SUPPLIER PART") "C114586") (field (name "CONTRIBUTOR") "LCSC"))
      (libsource (lib "altium-import") (part "root_0_WS2812B-B_"))
    )
    (comp (ref "LED49")
      (value "WS2812B-B")
      (fields (field (name "BOM_SUPPLIER PART") "C114586") (field (name "CONTRIBUTOR") "LCSC"))
      (libsource (lib "altium-import") (part "root_0_WS2812B-B_"))
    )
    (comp (ref "LED50")
      (value "WS2812B-B")
      (fields (field (name "BOM_SUPPLIER PART") "C114586") (field (name "CONTRIBUTOR") "LCSC"))
      (libsource (lib "altium-import") (part "root_0_WS2812B-B_"))
    )
    (comp (ref "LED51")
      (value "WS2812B-B")
      (fields (field (name "BOM_SUPPLIER PART") "C114586") (field (name "CONTRIBUTOR") "LCSC"))
      (libsource (lib "altium-import") (part "root_0_WS2812B-B_"))
    )
    (comp (ref "LED52")
      (value "WS2812B-B")
      (fields (field (name "BOM_SUPPLIER PART") "C114586") (field (name "CONTRIBUTOR") "LCSC"))
      (libsource (lib "altium-import") (part "root_0_WS2812B-B_"))
    )
    (comp (ref "LED53")
      (value "WS2812B-B")
      (fields (field (name "BOM_SUPPLIER PART") "C114586") (field (name "CONTRIBUTOR") "LCSC"))
      (libsource (lib "altium-import") (part "root_0_WS2812B-B_"))
    )
    (comp (ref "LED54")
      (value "WS2812B-B")
      (fields (field (name "BOM_SUPPLIER PART") "C114586") (field (name "CONTRIBUTOR") "LCSC"))
      (libsource (lib "altium-import") (part "root_0_WS2812B-B_"))
    )
    (comp (ref "LED55")
      (value "WS2812B-B")
      (fields (field (name "BOM_SUPPLIER PART") "C114586") (field (name "CONTRIBUTOR") "LCSC"))
      (libsource (lib "altium-import") (part "root_0_WS2812B-B_"))
    )
    (comp (ref "LED56")
      (value "WS2812B-B")
      (fields (field (name "BOM_SUPPLIER PART") "C114586") (field (name "CONTRIBUTOR") "LCSC"))
      (libsource (lib "altium-import") (part "root_0_WS2812B-B_"))
    )
    (comp (ref "LED57")
      (value "WS2812B-B")
      (fields (field (name "BOM_SUPPLIER PART") "C114586") (field (name "CONTRIBUTOR") "LCSC"))
      (libsource (lib "altium-import") (part "root_2_WS2812B-B_"))
    )
    (comp (ref "LED58")
      (value "WS2812B-B")
      (fields (field (name "BOM_SUPPLIER PART") "C114586") (field (name "CONTRIBUTOR") "LCSC"))
      (libsource (lib "altium-import") (part "root_2_WS2812B-B_"))
    )
    (comp (ref "LED59")
      (value "WS2812B-B")
      (fields (field (name "BOM_SUPPLIER PART") "C114586") (field (name "CONTRIBUTOR") "LCSC"))
      (libsource (lib "altium-import") (part "root_2_WS2812B-B_"))
    )
    (comp (ref "LED60")
      (value "WS2812B-B")
      (fields (field (name "BOM_SUPPLIER PART") "C114586") (field (name "CONTRIBUTOR") "LCSC"))
      (libsource (lib "altium-import") (part "root_2_WS2812B-B_"))
    )
    (comp (ref "LED61")
      (value "WS2812B-B")
      (fields (field (name "BOM_SUPPLIER PART") "C114586") (field (name "CONTRIBUTOR") "LCSC"))
      (libsource (lib "altium-import") (part "root_2_WS2812B-B_"))
    )
    (comp (ref "LED62")
      (value "WS2812B-B")
      (fields (field (name "BOM_SUPPLIER PART") "C114586") (field (name "CONTRIBUTOR") "LCSC"))
      (libsource (lib "altium-import") (part "root_2_WS2812B-B_"))
    )
    (comp (ref "LED63")
      (value "WS2812B-B")
      (fields (field (name "BOM_SUPPLIER PART") "C114586") (field (name "CONTRIBUTOR") "LCSC"))
      (libsource (lib "altium-import") (part "root_2_WS2812B-B_"))
    )
    (comp (ref "LED64")
      (value "WS2812B-B")
      (fields (field (name "BOM_SUPPLIER PART") "C114586") (field (name "CONTRIBUTOR") "LCSC"))
      (libsource (lib "altium-import") (part "root_2_WS2812B-B_"))
    )
    (comp (ref "LED65")
      (value "WS2812B-B")
      (fields (field (name "BOM_SUPPLIER PART") "C114586") (field (name "CONTRIBUTOR") "LCSC"))
      (libsource (lib "altium-import") (part "root_2_WS2812B-B_"))
    )
    (comp (ref "LED66")
      (value "WS2812B-B")
      (fields (field (name "BOM_SUPPLIER PART") "C114586") (field (name "CONTRIBUTOR") "LCSC"))
      (libsource (lib "altium-import") (part "root_2_WS2812B-B_"))
    )
    (comp (ref "LED67")
      (value "WS2812B-B")
      (fields (field (name "BOM_SUPPLIER PART") "C114586") (field (name "CONTRIBUTOR") "LCSC"))
      (libsource (lib "altium-import") (part "root_2_WS2812B-B_"))
    )
    (comp (ref "LED68")
      (value "WS2812B-B")
      (fields (field (name "BOM_SUPPLIER PART") "C114586") (field (name "CONTRIBUTOR") "LCSC"))
      (libsource (lib "altium-import") (part "root_0_WS2812B-B_"))
    )
    (comp (ref "LED69")
      (value "WS2812B-B")
      (fields (field (name "BOM_SUPPLIER PART") "C114586") (field (name "CONTRIBUTOR") "LCSC"))
      (libsource (lib "altium-import") (part "root_0_WS2812B-B_"))
    )
    (comp (ref "LED70")
      (value "WS2812B-B")
      (fields (field (name "BOM_SUPPLIER PART") "C114586") (field (name "CONTRIBUTOR") "LCSC"))
      (libsource (lib "altium-import") (part "root_0_WS2812B-B_"))
    )
    (comp (ref "LED71")
      (value "WS2812B-B")
      (fields (field (name "BOM_SUPPLIER PART") "C114586") (field (name "CONTRIBUTOR") "LCSC"))
      (libsource (lib "altium-import") (part "root_0_WS2812B-B_"))
    )
    (comp (ref "LED72")
      (value "WS2812B-B")
      (fields (field (name "BOM_SUPPLIER PART") "C114586") (field (name "CONTRIBUTOR") "LCSC"))
      (libsource (lib "altium-import") (part "root_0_WS2812B-B_"))
    )
    (comp (ref "LED73")
      (value "WS2812B-B")
      (fields (field (name "BOM_SUPPLIER PART") "C114586") (field (name "CONTRIBUTOR") "LCSC"))
      (libsource (lib "altium-import") (part "root_0_WS2812B-B_"))
    )
    (comp (ref "LED74")
      (value "WS2812B-B")
      (fields (field (name "BOM_SUPPLIER PART") "C114586") (field (name "CONTRIBUTOR") "LCSC"))
      (libsource (lib "altium-import") (part "root_0_WS2812B-B_"))
    )
    (comp (ref "LED75")
      (value "WS2812B-B")
      (fields (field (name "BOM_SUPPLIER PART") "C114586") (field (name "CONTRIBUTOR") "LCSC"))
      (libsource (lib "altium-import") (part "root_0_WS2812B-B_"))
    )
    (comp (ref "LED76")
      (value "WS2812B-B")
      (fields (field (name "BOM_SUPPLIER PART") "C114586") (field (name "CONTRIBUTOR") "LCSC"))
      (libsource (lib "altium-import") (part "root_0_WS2812B-B_"))
    )
    (comp (ref "LED77")
      (value "WS2812B-B")
      (fields (field (name "BOM_SUPPLIER PART") "C114586") (field (name "CONTRIBUTOR") "LCSC"))
      (libsource (lib "altium-import") (part "root_0_WS2812B-B_"))
    )
    (comp (ref "LED78")
      (value "WS2812B-B")
      (fields (field (name "BOM_SUPPLIER PART") "C114586") (field (name "CONTRIBUTOR") "LCSC"))
      (libsource (lib "altium-import") (part "root_0_WS2812B-B_"))
    )
    (comp (ref "LED79")
      (value "WS2812B-B")
      (fields (field (name "BOM_SUPPLIER PART") "C114586") (field (name "CONTRIBUTOR") "LCSC"))
      (libsource (lib "altium-import") (part "root_2_WS2812B-B_"))
    )
    (comp (ref "LED80")
      (value "WS2812B-B")
      (fields (field (name "BOM_SUPPLIER PART") "C114586") (field (name "CONTRIBUTOR") "LCSC"))
      (libsource (lib "altium-import") (part "root_2_WS2812B-B_"))
    )
    (comp (ref "LED81")
      (value "WS2812B-B")
      (fields (field (name "BOM_SUPPLIER PART") "C114586") (field (name "CONTRIBUTOR") "LCSC"))
      (libsource (lib "altium-import") (part "root_2_WS2812B-B_"))
    )
    (comp (ref "LED82")
      (value "WS2812B-B")
      (fields (field (name "BOM_SUPPLIER PART") "C114586") (field (name "CONTRIBUTOR") "LCSC"))
      (libsource (lib "altium-import") (part "root_2_WS2812B-B_"))
    )
    (comp (ref "LED83")
      (value "WS2812B-B")
      (fields (field (name "BOM_SUPPLIER PART") "C114586") (field (name "CONTRIBUTOR") "LCSC"))
      (libsource (lib "altium-import") (part "root_2_WS2812B-B_"))
    )
    (comp (ref "LED84")
      (value "WS2812B-B")
      (fields (field (name "BOM_SUPPLIER PART") "C114586") (field (name "CONTRIBUTOR") "LCSC"))
      (libsource (lib "altium-import") (part "root_2_WS2812B-B_"))
    )
    (comp (ref "LED85")
      (value "WS2812B-B")
      (fields (field (name "BOM_SUPPLIER PART") "C114586") (field (name "CONTRIBUTOR") "LCSC"))
      (libsource (lib "altium-import") (part "root_2_WS2812B-B_"))
    )
    (comp (ref "LED86")
      (value "WS2812B-B")
      (fields (field (name "BOM_SUPPLIER PART") "C114586") (field (name "CONTRIBUTOR") "LCSC"))
      (libsource (lib "altium-import") (part "root_2_WS2812B-B_"))
    )
    (comp (ref "LED87")
      (value "WS2812B-B")
      (fields (field (name "BOM_SUPPLIER PART") "C114586") (field (name "CONTRIBUTOR") "LCSC"))
      (libsource (lib "altium-import") (part "root_2_WS2812B-B_"))
    )
    (comp (ref "LED88")
      (value "WS2812B-B")
      (fields (field (name "BOM_SUPPLIER PART") "C114586") (field (name "CONTRIBUTOR") "LCSC"))
      (libsource (lib "altium-import") (part "root_2_WS2812B-B_"))
    )
    (comp (ref "LED89")
      (value "WS2812B-B")
      (fields (field (name "BOM_SUPPLIER PART") "C114586") (field (name "CONTRIBUTOR") "LCSC"))
      (libsource (lib "altium-import") (part "root_2_WS2812B-B_"))
    )
    (comp (ref "LED90")
      (value "WS2812B-B")
      (fields (field (name "BOM_SUPPLIER PART") "C114586") (field (name "CONTRIBUTOR") "LCSC"))
      (libsource (lib "altium-import") (part "root_0_WS2812B-B_"))
    )
    (comp (ref "LED91")
      (value "WS2812B-B")
      (fields (field (name "BOM_SUPPLIER PART") "C114586") (field (name "CONTRIBUTOR") "LCSC"))
      (libsource (lib "altium-import") (part "root_0_WS2812B-B_"))
    )
    (comp (ref "LED92")
      (value "WS2812B-B")
      (fields (field (name "BOM_SUPPLIER PART") "C114586") (field (name "CONTRIBUTOR") "LCSC"))
      (libsource (lib "altium-import") (part "root_0_WS2812B-B_"))
    )
    (comp (ref "LED93")
      (value "WS2812B-B")
      (fields (field (name "BOM_SUPPLIER PART") "C114586") (field (name "CONTRIBUTOR") "LCSC"))
      (libsource (lib "altium-import") (part "root_0_WS2812B-B_"))
    )
    (comp (ref "LED94")
      (value "WS2812B-B")
      (fields (field (name "BOM_SUPPLIER PART") "C114586") (field (name "CONTRIBUTOR") "LCSC"))
      (libsource (lib "altium-import") (part "root_0_WS2812B-B_"))
    )
    (comp (ref "LED95")
      (value "WS2812B-B")
      (fields (field (name "BOM_SUPPLIER PART") "C114586") (field (name "CONTRIBUTOR") "LCSC"))
      (libsource (lib "altium-import") (part "root_0_WS2812B-B_"))
    )
    (comp (ref "LED96")
      (value "WS2812B-B")
      (fields (field (name "BOM_SUPPLIER PART") "C114586") (field (name "CONTRIBUTOR") "LCSC"))
      (libsource (lib "altium-import") (part "root_0_WS2812B-B_"))
    )
    (comp (ref "LED97")
      (value "WS2812B-B")
      (fields (field (name "BOM_SUPPLIER PART") "C114586") (field (name "CONTRIBUTOR") "LCSC"))
      (libsource (lib "altium-import") (part "root_0_WS2812B-B_"))
    )
    (comp (ref "LED98")
      (value "WS2812B-B")
      (fields (field (name "BOM_SUPPLIER PART") "C114586") (field (name "CONTRIBUTOR") "LCSC"))
      (libsource (lib "altium-import") (part "root_0_WS2812B-B_"))
    )
    (comp (ref "LED99")
      (value "WS2812B-B")
      (fields (field (name "BOM_SUPPLIER PART") "C114586") (field (name "CONTRIBUTOR") "LCSC"))
      (libsource (lib "altium-import") (part "root_0_WS2812B-B_"))
    )
    (comp (ref "LED100")
      (value "WS2812B-B")
      (fields (field (name "BOM_SUPPLIER PART") "C114586") (field (name "CONTRIBUTOR") "LCSC"))
      (libsource (lib "altium-import") (part "root_0_WS2812B-B_"))
    )
    (comp (ref "LED101")
      (value "WS2812B-B")
      (fields (field (name "BOM_SUPPLIER PART") "C114586") (field (name "CONTRIBUTOR") "LCSC"))
      (libsource (lib "altium-import") (part "root_2_WS2812B-B_"))
    )
    (comp (ref "LED102")
      (value "WS2812B-B")
      (fields (field (name "BOM_SUPPLIER PART") "C114586") (field (name "CONTRIBUTOR") "LCSC"))
      (libsource (lib "altium-import") (part "root_2_WS2812B-B_"))
    )
    (comp (ref "LED103")
      (value "WS2812B-B")
      (fields (field (name "BOM_SUPPLIER PART") "C114586") (field (name "CONTRIBUTOR") "LCSC"))
      (libsource (lib "altium-import") (part "root_2_WS2812B-B_"))
    )
    (comp (ref "LED104")
      (value "WS2812B-B")
      (fields (field (name "BOM_SUPPLIER PART") "C114586") (field (name "CONTRIBUTOR") "LCSC"))
      (libsource (lib "altium-import") (part "root_2_WS2812B-B_"))
    )
    (comp (ref "LED105")
      (value "WS2812B-B")
      (fields (field (name "BOM_SUPPLIER PART") "C114586") (field (name "CONTRIBUTOR") "LCSC"))
      (libsource (lib "altium-import") (part "root_2_WS2812B-B_"))
    )
    (comp (ref "LED106")
      (value "WS2812B-B")
      (fields (field (name "BOM_SUPPLIER PART") "C114586") (field (name "CONTRIBUTOR") "LCSC"))
      (libsource (lib "altium-import") (part "root_2_WS2812B-B_"))
    )
    (comp (ref "LED107")
      (value "WS2812B-B")
      (fields (field (name "BOM_SUPPLIER PART") "C114586") (field (name "CONTRIBUTOR") "LCSC"))
      (libsource (lib "altium-import") (part "root_2_WS2812B-B_"))
    )
    (comp (ref "LED108")
      (value "WS2812B-B")
      (fields (field (name "BOM_SUPPLIER PART") "C114586") (field (name "CONTRIBUTOR") "LCSC"))
      (libsource (lib "altium-import") (part "root_2_WS2812B-B_"))
    )
    (comp (ref "LED109")
      (value "WS2812B-B")
      (fields (field (name "BOM_SUPPLIER PART") "C114586") (field (name "CONTRIBUTOR") "LCSC"))
      (libsource (lib "altium-import") (part "root_2_WS2812B-B_"))
    )
    (comp (ref "LED110")
      (value "WS2812B-B")
      (fields (field (name "BOM_SUPPLIER PART") "C114586") (field (name "CONTRIBUTOR") "LCSC"))
      (libsource (lib "altium-import") (part "root_2_WS2812B-B_"))
    )
    (comp (ref "LED111")
      (value "WS2812B-B")
      (fields (field (name "BOM_SUPPLIER PART") "C114586") (field (name "CONTRIBUTOR") "LCSC"))
      (libsource (lib "altium-import") (part "root_2_WS2812B-B_"))
    )
    (comp (ref "LED112")
      (value "WS2812B-B")
      (fields (field (name "BOM_SUPPLIER PART") "C114586") (field (name "CONTRIBUTOR") "LCSC"))
      (libsource (lib "altium-import") (part "root_2_WS2812B-B_"))
    )
    (comp (ref "LED113")
      (value "WS2812B-B")
      (fields (field (name "BOM_SUPPLIER PART") "C114586") (field (name "CONTRIBUTOR") "LCSC"))
      (libsource (lib "altium-import") (part "root_2_WS2812B-B_"))
    )
    (comp (ref "LED114")
      (value "WS2812B-B")
      (fields (field (name "BOM_SUPPLIER PART") "C114586") (field (name "CONTRIBUTOR") "LCSC"))
      (libsource (lib "altium-import") (part "root_2_WS2812B-B_"))
    )
    (comp (ref "LED115")
      (value "WS2812B-B")
      (fields (field (name "BOM_SUPPLIER PART") "C114586") (field (name "CONTRIBUTOR") "LCSC"))
      (libsource (lib "altium-import") (part "root_2_WS2812B-B_"))
    )
    (comp (ref "LED116")
      (value "FC-2012HRK-620D")
      (fields (field (name "BOM_SUPPLIER PART") "C84256"))
      (libsource (lib "altium-import") (part "root_2_FC-2012HRK-620D_"))
    )
    (comp (ref "M1")
      (value "ESP-01")
      (fields (field (name "CONTRIBUTOR") "DForest"))
      (libsource (lib "altium-import") (part "root_1_ESP-01_"))
    )
    (comp (ref "Q2")
      (value "LBC817-40LT1G")
      (fields (field (name "BOM_SUPPLIER PART") "C12767"))
      (libsource (lib "altium-import") (part "root_3_LBC817-40LT1G_"))
    )
    (comp (ref "QBOOT")
      (value "PTS810SJM250SMTRLFS")
      (fields (field (name "BOM_SUPPLIER PART") "C116501") (field (name "CONTRIBUTOR") "LCSC"))
      (libsource (lib "altium-import") (part "root_0_PTS810SJM250SMTRLFS_"))
    )
    (comp (ref "QU1")
      (value "RP2040")
      (fields (field (name "BOM_SUPPLIER PART") "C2040") (field (name "CONTRIBUTOR") "LCSC"))
      (libsource (lib "altium-import") (part "root_0_RP2040_"))
    )
    (comp (ref "QU2")
      (value "W25Q128JWPIQ")
      (fields (field (name "BOM_SUPPLIER PART") "C2689660") (field (name "CONTRIBUTOR") "LCSC"))
      (libsource (lib "altium-import") (part "root_0_W25Q128JWPIQ_"))
    )
    (comp (ref "QX1")
      (value "12MHz")
      (fields
        (field (name "BOM_MANUFACTURER PART") "X322512MSB4SI")
        (field (name "BOM_SUPPLIER PART") "C9002")
        (field (name "CONTRIBUTOR") "LCSC")
      )
      (libsource (lib "altium-import") (part "root_0_12MHz_"))
    )
    (comp (ref "R1")
      (value "4.7K")
      (fields
        (field (name "BOM_SUPPLIER PART") "C17673")
        (field (name "BOM_MANUFACTURER PART") "0805W8F4701T5E")
        (field (name "CONTRIBUTOR") "LCSC")
      )
      (libsource (lib "altium-import") (part "root_3_4.7K_"))
    )
    (comp (ref "R2")
      (value "1kΩ")
      (fields
        (field (name "BOM_SUPPLIER PART") "C17513")
        (field (name "BOM_MANUFACTURER PART") "0805W8F1001T5E")
        (field (name "CONTRIBUTOR") "LCSC")
      )
      (libsource (lib "altium-import") (part "root_1_1kΩ_"))
    )
    (comp (ref "R3")
      (value "4.7K")
      (fields
        (field (name "BOM_SUPPLIER PART") "C17673")
        (field (name "BOM_MANUFACTURER PART") "0805W8F4701T5E")
        (field (name "CONTRIBUTOR") "LCSC")
      )
      (libsource (lib "altium-import") (part "root_0_4.7K_"))
    )
    (comp (ref "R4")
      (value "4.7K")
      (fields
        (field (name "BOM_SUPPLIER PART") "C17673")
        (field (name "BOM_MANUFACTURER PART") "0805W8F4701T5E")
        (field (name "CONTRIBUTOR") "LCSC")
      )
      (libsource (lib "altium-import") (part "root_0_4.7K_"))
    )
    (comp (ref "R5")
      (value "10K")
      (fields
        (field (name "BOM_MANUFACTURER PART") "0805W8F1002T5E")
        (field (name "BOM_SUPPLIER PART") "C17414")
      )
      (libsource (lib "altium-import") (part "root_0_10K_"))
    )
    (comp (ref "R6")
      (value "22K")
      (fields
        (field (name "BOM_MANUFACTURER PART") "0805W8F2202T5E")
        (field (name "BOM_SUPPLIER PART") "C17560")
      )
      (libsource (lib "altium-import") (part "root_0_22K_"))
    )
    (comp (ref "R7")
      (value "24Ω")
      (fields
        (field (name "BOM_SUPPLIER PART") "C429050")
        (field (name "BOM_MANUFACTURER PART") "CR0805F24RP05")
        (field (name "CONTRIBUTOR") "LCSC")
      )
      (libsource (lib "altium-import") (part "root_0_24Ω_"))
    )
    (comp (ref "R8")
      (value "1K")
      (fields
        (field (name "BOM_MANUFACTURER PART") "0805W8F1001T5E")
        (field (name "BOM_SUPPLIER PART") "C17513")
      )
      (libsource (lib "altium-import") (part "root_1_1K_"))
    )
    (comp (ref "R9")
      (value "24Ω")
      (fields
        (field (name "BOM_SUPPLIER PART") "C429050")
        (field (name "BOM_MANUFACTURER PART") "CR0805F24RP05")
        (field (name "CONTRIBUTOR") "LCSC")
      )
      (libsource (lib "altium-import") (part "root_0_24Ω_"))
    )
    (comp (ref "R10")
      (value "50")
      (fields
        (field (name "BOM_MANUFACTURER PART") "0805W8F1002T5E")
        (field (name "BOM_SUPPLIER PART") "C17414")
      )
      (libsource (lib "altium-import") (part "root_0_50_"))
    )
    (comp (ref "R11")
      (value "1K")
      (fields
        (field (name "BOM_MANUFACTURER PART") "0805W8F1001T5E")
        (field (name "BOM_SUPPLIER PART") "C17513")
      )
      (libsource (lib "altium-import") (part "root_2_1K_"))
    )
    (comp (ref "R12")
      (value "1K")
      (fields
        (field (name "BOM_MANUFACTURER PART") "0805W8F1001T5E")
        (field (name "BOM_SUPPLIER PART") "C17513")
      )
      (libsource (lib "altium-import") (part "root_2_1K_"))
    )
    (comp (ref "R13")
      (value "100Ω")
      (fields
        (field (name "BOM_SUPPLIER PART") "C17408")
        (field (name "BOM_MANUFACTURER PART") "0805W8F1000T5E")
        (field (name "CONTRIBUTOR") "LCSC")
      )
      (libsource (lib "altium-import") (part "root_0_100Ω_"))
    )
    (comp (ref "RPRST")
      (value "PTS810SJM250SMTRLFS")
      (fields (field (name "BOM_SUPPLIER PART") "C116501") (field (name "CONTRIBUTOR") "LCSC"))
      (libsource (lib "altium-import") (part "root_0_PTS810SJM250SMTRLFS_"))
    )
    (comp (ref "RPSWD")
      (value "HDR-M-2.54_1x4")
      (fields (field (name "BOM_SUPPLIER PART") "C124378") (field (name "CONTRIBUTOR") "LCEDA_Lib"))
      (libsource (lib "altium-import") (part "root_1_HDR-M-2.54_1x4_"))
    )
    (comp (ref "RPUSB")
      (value "HDR-M-2.54_1x4")
      (fields (field (name "BOM_SUPPLIER PART") "C124378") (field (name "CONTRIBUTOR") "LCEDA_Lib"))
      (libsource (lib "altium-import") (part "root_1_HDR-M-2.54_1x4_"))
    )
    (comp (ref "U1")
      (value "BH1750FVI-TR")
      (fields (field (name "BOM_SUPPLIER PART") "C78960"))
      (libsource (lib "altium-import") (part "root_0_BH1750FVI-TR_"))
    )
    (comp (ref "U2")
      (value "AMS1117-3.3")
      (fields (field (name "BOM_SUPPLIER PART") "C6186"))
      (libsource (lib "altium-import") (part "root_0_AMS1117-3.3_"))
    )
    (comp (ref "U3")
      (value "DS1307M/TR")
      (fields (field (name "BOM_SUPPLIER PART") "C356706") (field (name "CONTRIBUTOR") "LCSC"))
      (libsource (lib "altium-import") (part "root_0_DS1307M/TR_"))
    )
    (comp (ref "X1")
      (value "CFV206-60.003KDZF")
      (fields (field (name "BOM_SUPPLIER PART") "C389957") (field (name "CONTRIBUTOR") "LCSC"))
      (libsource (lib "altium-import") (part "root_3_CFV206-60.003KDZF_"))
    )
  )
  (nets
    (net (code "1") (name "+1V1") (class "Default")
      (node (ref "C123") (pin "1") (pinfunction "1_1") (pintype "passive"))
      (node (ref "C124") (pin "1") (pinfunction "1_1") (pintype "passive"))
      (node (ref "QU1") (pin "23") (pinfunction "DVDD_23") (pintype "passive"))
      (node (ref "QU1") (pin "45") (pinfunction "VREG_VOUT_45") (pintype "passive"))
      (node (ref "QU1") (pin "50") (pinfunction "DVDD_50") (pintype "passive"))
    )
    (net (code "2") (name "+5V") (class "Default")
      (node (ref "1") (pin "VBUS") (pinfunction "VBUS_VBUS") (pintype "passive"))
      (node (ref "C1") (pin "1") (pinfunction "1_1") (pintype "passive"))
      (node (ref "C100") (pin "1") (pinfunction "1_1") (pintype "passive"))
      (node (ref "C101") (pin "1") (pinfunction "1_1") (pintype "passive"))
      (node (ref "C102") (pin "1") (pinfunction "1_1") (pintype "passive"))
      (node (ref "C103") (pin "1") (pinfunction "1_1") (pintype "passive"))
      (node (ref "C104") (pin "1") (pinfunction "1_1") (pintype "passive"))
      (node (ref "C105") (pin "1") (pinfunction "1_1") (pintype "passive"))
      (node (ref "C106") (pin "1") (pinfunction "1_1") (pintype "passive"))
      (node (ref "C107") (pin "1") (pinfunction "1_1") (pintype "passive"))
      (node (ref "C108") (pin "1") (pinfunction "1_1") (pintype "passive"))
      (node (ref "C109") (pin "1") (pinfunction "1_1") (pintype "passive"))
      (node (ref "C11") (pin "1") (pinfunction "1_1") (pintype "passive"))
      (node (ref "C110") (pin "1") (pinfunction "1_1") (pintype "passive"))
      (node (ref "C111") (pin "1") (pinfunction "1_1") (pintype "passive"))
      (node (ref "C112") (pin "1") (pinfunction "1_1") (pintype "passive"))
      (node (ref "C113") (pin "1") (pinfunction "1_1") (pintype "passive"))
      (node (ref "C114") (pin "1") (pinfunction "1_1") (pintype "passive"))
      (node (ref "C115") (pin "1") (pinfunction "1_1") (pintype "passive"))
      (node (ref "C116") (pin "1") (pinfunction "1_1") (pintype "passive"))
      (node (ref "C117") (pin "1") (pinfunction "1_1") (pintype "passive"))
      (node (ref "C118") (pin "1") (pinfunction "1_1") (pintype "passive"))
      (node (ref "C119") (pin "1") (pinfunction "1_1") (pintype "passive"))
      (node (ref "C12") (pin "1") (pinfunction "1_1") (pintype "passive"))
      (node (ref "C120") (pin "1") (pinfunction "1_1") (pintype "passive"))
      (node (ref "C121") (pin "1") (pinfunction "1_1") (pintype "passive"))
      (node (ref "C122") (pin "1") (pinfunction "1_1") (pintype "passive"))
      (node (ref "C13") (pin "1") (pinfunction "1_1") (pintype "passive"))
      (node (ref "C14") (pin "1") (pinfunction "1_1") (pintype "passive"))
      (node (ref "C15") (pin "1") (pinfunction "1_1") (pintype "passive"))
      (node (ref "C16") (pin "1") (pinfunction "1_1") (pintype "passive"))
      (node (ref "C17") (pin "1") (pinfunction "1_1") (pintype "passive"))
      (node (ref "C18") (pin "1") (pinfunction "1_1") (pintype "passive"))
      (node (ref "C19") (pin "1") (pinfunction "1_1") (pintype "passive"))
      (node (ref "C2") (pin "2") (pinfunction "2_2") (pintype "passive"))
      (node (ref "C20") (pin "1") (pinfunction "1_1") (pintype "passive"))
      (node (ref "C21") (pin "1") (pinfunction "1_1") (pintype "passive"))
      (node (ref "C22") (pin "1") (pinfunction "1_1") (pintype "passive"))
      (node (ref "C23") (pin "1") (pinfunction "1_1") (pintype "passive"))
      (node (ref "C24") (pin "1") (pinfunction "1_1") (pintype "passive"))
      (node (ref "C25") (pin "1") (pinfunction "1_1") (pintype "passive"))
      (node (ref "C26") (pin "1") (pinfunction "1_1") (pintype "passive"))
      (node (ref "C27") (pin "1") (pinfunction "1_1") (pintype "passive"))
      (node (ref "C28") (pin "1") (pinfunction "1_1") (pintype "passive"))
      (node (ref "C29") (pin "1") (pinfunction "1_1") (pintype "passive"))
      (node (ref "C30") (pin "1") (pinfunction "1_1") (pintype "passive"))
      (node (ref "C31") (pin "1") (pinfunction "1_1") (pintype "passive"))
      (node (ref "C32") (pin "1") (pinfunction "1_1") (pintype "passive"))
      (node (ref "C33") (pin "1") (pinfunction "1_1") (pintype "passive"))
      (node (ref "C34") (pin "1") (pinfunction "1_1") (pintype "passive"))
      (node (ref "C35") (pin "1") (pinfunction "1_1") (pintype "passive"))
      (node (ref "C36") (pin "1") (pinfunction "1_1") (pintype "passive"))
      (node (ref "C37") (pin "1") (pinfunction "1_1") (pintype "passive"))
      (node (ref "C38") (pin "1") (pinfunction "1_1") (pintype "passive"))
      (node (ref "C39") (pin "1") (pinfunction "1_1") (pintype "passive"))
      (node (ref "C40") (pin "1") (pinfunction "1_1") (pintype "passive"))
      (node (ref "C41") (pin "1") (pinfunction "1_1") (pintype "passive"))
      (node (ref "C42") (pin "1") (pinfunction "1_1") (pintype "passive"))
      (node (ref "C43") (pin "1") (pinfunction "1_1") (pintype "passive"))
      (node (ref "C44") (pin "1") (pinfunction "1_1") (pintype "passive"))
      (node (ref "C45") (pin "1") (pinfunction "1_1") (pintype "passive"))
      (node (ref "C46") (pin "1") (pinfunction "1_1") (pintype "passive"))
      (node (ref "C47") (pin "1") (pinfunction "1_1") (pintype "passive"))
      (node (ref "C48") (pin "1") (pinfunction "1_1") (pintype "passive"))
      (node (ref "C49") (pin "1") (pinfunction "1_1") (pintype "passive"))
      (node (ref "C5") (pin "1") (pinfunction "1_1") (pintype "passive"))
      (node (ref "C50") (pin "1") (pinfunction "1_1") (pintype "passive"))
      (node (ref "C51") (pin "1") (pinfunction "1_1") (pintype "passive"))
      (node (ref "C52") (pin "1") (pinfunction "1_1") (pintype "passive"))
      (node (ref "C53") (pin "1") (pinfunction "1_1") (pintype "passive"))
      (node (ref "C54") (pin "1") (pinfunction "1_1") (pintype "passive"))
      (node (ref "C55") (pin "1") (pinfunction "1_1") (pintype "passive"))
      (node (ref "C56") (pin "1") (pinfunction "1_1") (pintype "passive"))
      (node (ref "C57") (pin "1") (pinfunction "1_1") (pintype "passive"))
      (node (ref "C58") (pin "1") (pinfunction "1_1") (pintype "passive"))
      (node (ref "C59") (pin "1") (pinfunction "1_1") (pintype "passive"))
      (node (ref "C60") (pin "1") (pinfunction "1_1") (pintype "passive"))
      (node (ref "C61") (pin "1") (pinfunction "1_1") (pintype "passive"))
      (node (ref "C62") (pin "1") (pinfunction "1_1") (pintype "passive"))
      (node (ref "C63") (pin "1") (pinfunction "1_1") (pintype "passive"))
      (node (ref "C64") (pin "1") (pinfunction "1_1") (pintype "passive"))
      (node (ref "C65") (pin "1") (pinfunction "1_1") (pintype "passive"))
      (node (ref "C66") (pin "1") (pinfunction "1_1") (pintype "passive"))
      (node (ref "C67") (pin "1") (pinfunction "1_1") (pintype "passive"))
      (node (ref "C68") (pin "1") (pinfunction "1_1") (pintype "passive"))
      (node (ref "C69") (pin "1") (pinfunction "1_1") (pintype "passive"))
      (node (ref "C70") (pin "1") (pinfunction "1_1") (pintype "passive"))
      (node (ref "C71") (pin "1") (pinfunction "1_1") (pintype "passive"))
      (node (ref "C72") (pin "1") (pinfunction "1_1") (pintype "passive"))
      (node (ref "C73") (pin "1") (pinfunction "1_1") (pintype "passive"))
      (node (ref "C74") (pin "1") (pinfunction "1_1") (pintype "passive"))
      (node (ref "C75") (pin "1") (pinfunction "1_1") (pintype "passive"))
      (node (ref "C76") (pin "1") (pinfunction "1_1") (pintype "passive"))
      (node (ref "C77") (pin "1") (pinfunction "1_1") (pintype "passive"))
      (node (ref "C78") (pin "1") (pinfunction "1_1") (pintype "passive"))
      (node (ref "C79") (pin "1") (pinfunction "1_1") (pintype "passive"))
      (node (ref "C8") (pin "1") (pinfunction "1_1") (pintype "passive"))
      (node (ref "C80") (pin "1") (pinfunction "1_1") (pintype "passive"))
      (node (ref "C81") (pin "1") (pinfunction "1_1") (pintype "passive"))
      (node (ref "C82") (pin "1") (pinfunction "1_1") (pintype "passive"))
      (node (ref "C83") (pin "1") (pinfunction "1_1") (pintype "passive"))
      (node (ref "C84") (pin "1") (pinfunction "1_1") (pintype "passive"))
      (node (ref "C85") (pin "1") (pinfunction "1_1") (pintype "passive"))
      (node (ref "C86") (pin "1") (pinfunction "1_1") (pintype "passive"))
      (node (ref "C87") (pin "1") (pinfunction "1_1") (pintype "passive"))
      (node (ref "C88") (pin "1") (pinfunction "1_1") (pintype "passive"))
      (node (ref "C89") (pin "1") (pinfunction "1_1") (pintype "passive"))
      (node (ref "C90") (pin "1") (pinfunction "1_1") (pintype "passive"))
      (node (ref "C91") (pin "1") (pinfunction "1_1") (pintype "passive"))
      (node (ref "C92") (pin "1") (pinfunction "1_1") (pintype "passive"))
      (node (ref "C93") (pin "1") (pinfunction "1_1") (pintype "passive"))
      (node (ref "C94") (pin "1") (pinfunction "1_1") (pintype "passive"))
      (node (ref "C95") (pin "1") (pinfunction "1_1") (pintype "passive"))
      (node (ref "C96") (pin "1") (pinfunction "1_1") (pintype "passive"))
      (node (ref "C97") (pin "1") (pinfunction "1_1") (pintype "passive"))
      (node (ref "C98") (pin "1") (pinfunction "1_1") (pintype "passive"))
      (node (ref "C99") (pin "1") (pinfunction "1_1") (pintype "passive"))
      (node (ref "D1") (pin "2") (pinfunction "A_2") (pintype "passive"))
      (node (ref "H1") (pin "1") (pinfunction "1_1") (pintype "passive"))
      (node (ref "H10") (pin "1") (pinfunction "1_1") (pintype "passive"))
      (node (ref "H11") (pin "1") (pinfunction "1_1") (pintype "passive"))
      (node (ref "H12") (pin "1") (pinfunction "1_1") (pintype "passive"))
      (node (ref "H13") (pin "1") (pinfunction "1_1") (pintype "passive"))
      (node (ref "H14") (pin "1") (pinfunction "1_1") (pintype "passive"))
      (node (ref "H15") (pin "1") (pinfunction "1_1") (pintype "passive"))
      (node (ref "H16") (pin "1") (pinfunction "1_1") (pintype "passive"))
      (node (ref "H17") (pin "1") (pinfunction "1_1") (pintype "passive"))
      (node (ref "H18") (pin "1") (pinfunction "1_1") (pintype "passive"))
      (node (ref "H19") (pin "1") (pinfunction "1_1") (pintype "passive"))
      (node (ref "H2") (pin "1") (pinfunction "1_1") (pintype "passive"))
      (node (ref "H20") (pin "1") (pinfunction "1_1") (pintype "passive"))
      (node (ref "H21") (pin "1") (pinfunction "1_1") (pintype "passive"))
      (node (ref "H24") (pin "1") (pinfunction "1_1") (pintype "passive"))
      (node (ref "H3") (pin "1") (pinfunction "1_1") (pintype "passive"))
      (node (ref "H4") (pin "1") (pinfunction "1_1") (pintype "passive"))
      (node (ref "H5") (pin "1") (pinfunction "1_1") (pintype "passive"))
      (node (ref "H6") (pin "1") (pinfunction "1_1") (pintype "passive"))
      (node (ref "H7") (pin "1") (pinfunction "1_1") (pintype "passive"))
      (node (ref "H8") (pin "1") (pinfunction "1_1") (pintype "passive"))
      (node (ref "H9") (pin "1") (pinfunction "1_1") (pintype "passive"))
      (node (ref "JP4") (pin "1") (pinfunction "1_1") (pintype "passive"))
      (node (ref "LED1") (pin "1") (pinfunction "VDD_1") (pintype "passive"))
      (node (ref "LED10") (pin "1") (pinfunction "VDD_1") (pintype "passive"))
      (node (ref "LED100") (pin "1") (pinfunction "VDD_1") (pintype "passive"))
      (node (ref "LED101") (pin "1") (pinfunction "VDD_1") (pintype "passive"))
      (node (ref "LED102") (pin "1") (pinfunction "VDD_1") (pintype "passive"))
      (node (ref "LED103") (pin "1") (pinfunction "VDD_1") (pintype "passive"))
      (node (ref "LED104") (pin "1") (pinfunction "VDD_1") (pintype "passive"))
      (node (ref "LED105") (pin "1") (pinfunction "VDD_1") (pintype "passive"))
      (node (ref "LED106") (pin "1") (pinfunction "VDD_1") (pintype "passive"))
      (node (ref "LED107") (pin "1") (pinfunction "VDD_1") (pintype "passive"))
      (node (ref "LED108") (pin "1") (pinfunction "VDD_1") (pintype "passive"))
      (node (ref "LED109") (pin "1") (pinfunction "VDD_1") (pintype "passive"))
      (node (ref "LED11") (pin "1") (pinfunction "VDD_1") (pintype "passive"))
      (node (ref "LED110") (pin "1") (pinfunction "VDD_1") (pintype "passive"))
      (node (ref "LED111") (pin "1") (pinfunction "VDD_1") (pintype "passive"))
      (node (ref "LED112") (pin "1") (pinfunction "VDD_1") (pintype "passive"))
      (node (ref "LED113") (pin "1") (pinfunction "VDD_1") (pintype "passive"))
      (node (ref "LED114") (pin "1") (pinfunction "VDD_1") (pintype "passive"))
      (node (ref "LED115") (pin "1") (pinfunction "VDD_1") (pintype "passive"))
      (node (ref "LED12") (pin "1") (pinfunction "VDD_1") (pintype "passive"))
      (node (ref "LED13") (pin "1") (pinfunction "VDD_1") (pintype "passive"))
      (node (ref "LED14") (pin "1") (pinfunction "VDD_1") (pintype "passive"))
      (node (ref "LED15") (pin "1") (pinfunction "VDD_1") (pintype "passive"))
      (node (ref "LED16") (pin "1") (pinfunction "VDD_1") (pintype "passive"))
      (node (ref "LED17") (pin "1") (pinfunction "VDD_1") (pintype "passive"))
      (node (ref "LED18") (pin "1") (pinfunction "VDD_1") (pintype "passive"))
      (node (ref "LED19") (pin "1") (pinfunction "VDD_1") (pintype "passive"))
      (node (ref "LED20") (pin "1") (pinfunction "VDD_1") (pintype "passive"))
      (node (ref "LED21") (pin "1") (pinfunction "VDD_1") (pintype "passive"))
      (node (ref "LED22") (pin "1") (pinfunction "VDD_1") (pintype "passive"))
      (node (ref "LED23") (pin "1") (pinfunction "VDD_1") (pintype "passive"))
      (node (ref "LED24") (pin "1") (pinfunction "VDD_1") (pintype "passive"))
      (node (ref "LED25") (pin "1") (pinfunction "VDD_1") (pintype "passive"))
      (node (ref "LED26") (pin "1") (pinfunction "VDD_1") (pintype "passive"))
      (node (ref "LED27") (pin "1") (pinfunction "VDD_1") (pintype "passive"))
      (node (ref "LED28") (pin "1") (pinfunction "VDD_1") (pintype "passive"))
      (node (ref "LED29") (pin "1") (pinfunction "VDD_1") (pintype "passive"))
      (node (ref "LED3") (pin "1") (pinfunction "VDD_1") (pintype "passive"))
      (node (ref "LED30") (pin "1") (pinfunction "VDD_1") (pintype "passive"))
      (node (ref "LED31") (pin "1") (pinfunction "VDD_1") (pintype "passive"))
      (node (ref "LED32") (pin "1") (pinfunction "VDD_1") (pintype "passive"))
      (node (ref "LED33") (pin "1") (pinfunction "VDD_1") (pintype "passive"))
      (node (ref "LED34") (pin "1") (pinfunction "VDD_1") (pintype "passive"))
      (node (ref "LED35") (pin "1") (pinfunction "VDD_1") (pintype "passive"))
      (node (ref "LED36") (pin "1") (pinfunction "VDD_1") (pintype "passive"))
      (node (ref "LED37") (pin "1") (pinfunction "VDD_1") (pintype "passive"))
      (node (ref "LED38") (pin "1") (pinfunction "VDD_1") (pintype "passive"))
      (node (ref "LED39") (pin "1") (pinfunction "VDD_1") (pintype "passive"))
      (node (ref "LED4") (pin "1") (pinfunction "VDD_1") (pintype "passive"))
      (node (ref "LED40") (pin "1") (pinfunction "VDD_1") (pintype "passive"))
      (node (ref "LED41") (pin "1") (pinfunction "VDD_1") (pintype "passive"))
      (node (ref "LED42") (pin "1") (pinfunction "VDD_1") (pintype "passive"))
      (node (ref "LED43") (pin "1") (pinfunction "VDD_1") (pintype "passive"))
      (node (ref "LED44") (pin "1") (pinfunction "VDD_1") (pintype "passive"))
      (node (ref "LED45") (pin "1") (pinfunction "VDD_1") (pintype "passive"))
      (node (ref "LED46") (pin "1") (pinfunction "VDD_1") (pintype "passive"))
      (node (ref "LED47") (pin "1") (pinfunction "VDD_1") (pintype "passive"))
      (node (ref "LED48") (pin "1") (pinfunction "VDD_1") (pintype "passive"))
      (node (ref "LED49") (pin "1") (pinfunction "VDD_1") (pintype "passive"))
      (node (ref "LED5") (pin "1") (pinfunction "VDD_1") (pintype "passive"))
      (node (ref "LED50") (pin "1") (pinfunction "VDD_1") (pintype "passive"))
      (node (ref "LED51") (pin "1") (pinfunction "VDD_1") (pintype "passive"))
      (node (ref "LED52") (pin "1") (pinfunction "VDD_1") (pintype "passive"))
      (node (ref "LED53") (pin "1") (pinfunction "VDD_1") (pintype "passive"))
      (node (ref "LED54") (pin "1") (pinfunction "VDD_1") (pintype "passive"))
      (node (ref "LED55") (pin "1") (pinfunction "VDD_1") (pintype "passive"))
      (node (ref "LED56") (pin "1") (pinfunction "VDD_1") (pintype "passive"))
      (node (ref "LED57") (pin "1") (pinfunction "VDD_1") (pintype "passive"))
      (node (ref "LED58") (pin "1") (pinfunction "VDD_1") (pintype "passive"))
      (node (ref "LED59") (pin "1") (pinfunction "VDD_1") (pintype "passive"))
      (node (ref "LED6") (pin "1") (pinfunction "VDD_1") (pintype "passive"))
      (node (ref "LED60") (pin "1") (pinfunction "VDD_1") (pintype "passive"))
      (node (ref "LED61") (pin "1") (pinfunction "VDD_1") (pintype "passive"))
      (node (ref "LED62") (pin "1") (pinfunction "VDD_1") (pintype "passive"))
      (node (ref "LED63") (pin "1") (pinfunction "VDD_1") (pintype "passive"))
      (node (ref "LED64") (pin "1") (pinfunction "VDD_1") (pintype "passive"))
      (node (ref "LED65") (pin "1") (pinfunction "VDD_1") (pintype "passive"))
      (node (ref "LED66") (pin "1") (pinfunction "VDD_1") (pintype "passive"))
      (node (ref "LED67") (pin "1") (pinfunction "VDD_1") (pintype "passive"))
      (node (ref "LED68") (pin "1") (pinfunction "VDD_1") (pintype "passive"))
      (node (ref "LED69") (pin "1") (pinfunction "VDD_1") (pintype "passive"))
      (node (ref "LED7") (pin "1") (pinfunction "VDD_1") (pintype "passive"))
      (node (ref "LED70") (pin "1") (pinfunction "VDD_1") (pintype "passive"))
      (node (ref "LED71") (pin "1") (pinfunction "VDD_1") (pintype "passive"))
      (node (ref "LED72") (pin "1") (pinfunction "VDD_1") (pintype "passive"))
      (node (ref "LED73") (pin "1") (pinfunction "VDD_1") (pintype "passive"))
      (node (ref "LED74") (pin "1") (pinfunction "VDD_1") (pintype "passive"))
      (node (ref "LED75") (pin "1") (pinfunction "VDD_1") (pintype "passive"))
      (node (ref "LED76") (pin "1") (pinfunction "VDD_1") (pintype "passive"))
      (node (ref "LED77") (pin "1") (pinfunction "VDD_1") (pintype "passive"))
      (node (ref "LED78") (pin "1") (pinfunction "VDD_1") (pintype "passive"))
      (node (ref "LED79") (pin "1") (pinfunction "VDD_1") (pintype "passive"))
      (node (ref "LED8") (pin "1") (pinfunction "VDD_1") (pintype "passive"))
      (node (ref "LED80") (pin "1") (pinfunction "VDD_1") (pintype "passive"))
      (node (ref "LED81") (pin "1") (pinfunction "VDD_1") (pintype "passive"))
      (node (ref "LED82") (pin "1") (pinfunction "VDD_1") (pintype "passive"))
      (node (ref "LED83") (pin "1") (pinfunction "VDD_1") (pintype "passive"))
      (node (ref "LED84") (pin "1") (pinfunction "VDD_1") (pintype "passive"))
      (node (ref "LED85") (pin "1") (pinfunction "VDD_1") (pintype "passive"))
      (node (ref "LED86") (pin "1") (pinfunction "VDD_1") (pintype "passive"))
      (node (ref "LED87") (pin "1") (pinfunction "VDD_1") (pintype "passive"))
      (node (ref "LED88") (pin "1") (pinfunction "VDD_1") (pintype "passive"))
      (node (ref "LED89") (pin "1") (pinfunction "VDD_1") (pintype "passive"))
      (node (ref "LED9") (pin "1") (pinfunction "VDD_1") (pintype "passive"))
      (node (ref "LED90") (pin "1") (pinfunction "VDD_1") (pintype "passive"))
      (node (ref "LED91") (pin "1") (pinfunction "VDD_1") (pintype "passive"))
      (node (ref "LED92") (pin "1") (pinfunction "VDD_1") (pintype "passive"))
      (node (ref "LED93") (pin "1") (pinfunction "VDD_1") (pintype "passive"))
      (node (ref "LED94") (pin "1") (pinfunction "VDD_1") (pintype "passive"))
      (node (ref "LED95") (pin "1") (pinfunction "VDD_1") (pintype "passive"))
      (node (ref "LED96") (pin "1") (pinfunction "VDD_1") (pintype "passive"))
      (node (ref "LED97") (pin "1") (pinfunction "VDD_1") (pintype "passive"))
      (node (ref "LED98") (pin "1") (pinfunction "VDD_1") (pintype "passive"))
      (node (ref "LED99") (pin "1") (pinfunction "VDD_1") (pintype "passive"))
      (node (ref "R6") (pin "2") (pinfunction "2_2") (pintype "passive"))
      (node (ref "R8") (pin "2") (pinfunction "2_2") (pintype "passive"))
      (node (ref "RPUSB") (pin "1") (pinfunction "1_1") (pintype "passive"))
      (node (ref "U2") (pin "3") (pinfunction "In_3") (pintype "passive"))
    )
    (net (code "3") (name "/ADC0") (class "Default")
      (node (ref "QU1") (pin "38") (pinfunction "GPIO26_ADC0_38") (pintype "passive"))
    )
    (net (code "4") (name "/ADC1") (class "Default")
      (node (ref "QU1") (pin "39") (pinfunction "GPIO27_ADC1_39") (pintype "passive"))
    )
    (net (code "5") (name "/ADC2") (class "Default")
      (node (ref "QU1") (pin "40") (pinfunction "GPIO28_ADC2_40") (pintype "passive"))
    )
    (net (code "6") (name "/ADC3") (class "Default")
      (node (ref "QU1") (pin "41") (pinfunction "GPIO29_ADC3_41") (pintype "passive"))
    )
    (net (code "7") (name "/GPIO 0") (class "Default")
      (node (ref "1") (pin "GP0") (pinfunction "GP0_GP0") (pintype "passive"))
      (node (ref "M1") (pin "7") (pinfunction "GPIO3/RX_7") (pintype "passive"))
      (node (ref "QU1") (pin "2") (pinfunction "GPIO0_2") (pintype "passive"))
    )
    (net (code "8") (name "/GPIO 1") (class "Default")
      (node (ref "1") (pin "GP1") (pinfunction "GP1_GP1") (pintype "passive"))
      (node (ref "M1") (pin "2") (pinfunction "GPIO1/TX_2") (pintype "passive"))
      (node (ref "QU1") (pin "3") (pinfunction "GPIO1_3") (pintype "passive"))
    )
    (net (code "9") (name "/GPIO 2") (class "Default")
      (node (ref "1") (pin "GP2") (pinfunction "GP2_GP2") (pintype "passive"))
      (node (ref "H22") (pin "2") (pinfunction "2_2") (pintype "passive"))
      (node (ref "QU1") (pin "4") (pinfunction "GPIO2_4") (pintype "passive"))
      (node (ref "R3") (pin "2") (pinfunction "2_2") (pintype "passive"))
      (node (ref "U1") (pin "4") (pinfunction "SDA_4") (pintype "passive"))
      (node (ref "U3") (pin "5") (pinfunction "SDA_5") (pintype "passive"))
    )
    (net (code "10") (name "/GPIO 3") (class "Default")
      (node (ref "1") (pin "GP3") (pinfunction "GP3_GP3") (pintype "passive"))
      (node (ref "H22") (pin "3") (pinfunction "3_3") (pintype "passive"))
      (node (ref "QU1") (pin "5") (pinfunction "GPIO3_5") (pintype "passive"))
      (node (ref "R4") (pin "2") (pinfunction "2_2") (pintype "passive"))
      (node (ref "U1") (pin "6") (pinfunction "SCL_6") (pintype "passive"))
      (node (ref "U3") (pin "6") (pinfunction "SCL_6") (pintype "passive"))
    )
    (net (code "11") (name "/GPIO 4") (class "Default")
      (node (ref "QU1") (pin "6") (pinfunction "GPIO4_6") (pintype "passive"))
    )
    (net (code "12") (name "/GPIO 5") (class "Default")
      (node (ref "QU1") (pin "7") (pinfunction "GPIO5_7") (pintype "passive"))
    )
    (net (code "13") (name "/GPIO 6") (class "Default")
      (node (ref "QU1") (pin "8") (pinfunction "GPIO6_8") (pintype "passive"))
    )
    (net (code "14") (name "/GPIO 7") (class "Default")
      (node (ref "QU1") (pin "9") (pinfunction "GPIO7_9") (pintype "passive"))
    )
    (net (code "15") (name "/GPIO 8") (class "Default")
      (node (ref "QU1") (pin "11") (pinfunction "GPIO8_11") (pintype "passive"))
    )
    (net (code "16") (name "/GPIO 9") (class "Default")
      (node (ref "QU1") (pin "12") (pinfunction "GPIO9_12") (pintype "passive"))
    )
    (net (code "17") (name "/GPIO 10") (class "Default")
      (node (ref "QU1") (pin "13") (pinfunction "GPIO10_13") (pintype "passive"))
    )
    (net (code "18") (name "/GPIO 11") (class "Default")
      (node (ref "QU1") (pin "14") (pinfunction "GPIO11_14") (pintype "passive"))
    )
    (net (code "19") (name "/GPIO 12") (class "Default")
      (node (ref "QU1") (pin "15") (pinfunction "GPIO12_15") (pintype "passive"))
    )
    (net (code "20") (name "/GPIO 13") (class "Default")
      (node (ref "QU1") (pin "16") (pinfunction "GPIO13_16") (pintype "passive"))
    )
    (net (code "21") (name "/GPIO 14") (class "Default")
      (node (ref "QU1") (pin "17") (pinfunction "GPIO14_17") (pintype "passive"))
    )
    (net (code "22") (name "/GPIO 15") (class "Default")
      (node (ref "QU1") (pin "18") (pinfunction "GPIO15_18") (pintype "passive"))
    )
    (net (code "23") (name "/GPIO 16") (class "Default")
      (node (ref "1") (pin "GP16") (pinfunction "GP16_GP16") (pintype "passive"))
      (node (ref "JP7") (pin "1") (pinfunction "1_1") (pintype "passive"))
      (node (ref "QU1") (pin "27") (pinfunction "GPIO16_27") (pintype "passive"))
    )
    (net (code "24") (name "/GPIO 17") (class "Default")
      (node (ref "QU1") (pin "28") (pinfunction "GPIO17_28") (pintype "passive"))
    )
    (net (code "25") (name "/GPIO 18") (class "Default")
      (node (ref "QU1") (pin "29") (pinfunction "GPIO18_29") (pintype "passive"))
    )
    (net (code "26") (name "/GPIO 19") (class "Default")
      (node (ref "QU1") (pin "30") (pinfunction "GPIO19_30") (pintype "passive"))
    )
    (net (code "27") (name "/GPIO 20") (class "Default")
      (node (ref "QU1") (pin "31") (pinfunction "GPIO20_31") (pintype "passive"))
    )
    (net (code "28") (name "/GPIO 21") (class "Default")
      (node (ref "QU1") (pin "32") (pinfunction "GPIO21_32") (pintype "passive"))
    )
    (net (code "29") (name "/GPIO 22") (class "Default")
      (node (ref "1") (pin "GP22") (pinfunction "GP22_GP22") (pintype "passive"))
      (node (ref "JP6") (pin "1") (pinfunction "1_1") (pintype "passive"))
      (node (ref "QU1") (pin "34") (pinfunction "GPIO22_34") (pintype "passive"))
    )
    (net (code "30") (name "/GPIO 23") (class "Default")
      (node (ref "QU1") (pin "35") (pinfunction "GPIO23_35") (pintype "passive"))
    )
    (net (code "31") (name "/GPIO 24") (class "Default")
      (node (ref "QU1") (pin "36") (pinfunction "GPIO24_36") (pintype "passive"))
    )
    (net (code "32") (name "/GPIO 25") (class "Default")
      (node (ref "QU1") (pin "37") (pinfunction "GPIO25_37") (pintype "passive"))
      (node (ref "R13") (pin "1") (pinfunction "1_1") (pintype "passive"))
    )
    (net (code "33") (name "/QSPI_CLK") (class "Default")
      (node (ref "QU1") (pin "52") (pinfunction "QSPI_SCLK_52") (pintype "passive"))
      (node (ref "QU2") (pin "6") (pinfunction "CLK_6") (pintype "passive"))
    )
    (net (code "34") (name "/QSPI_SD0") (class "Default")
      (node (ref "QU1") (pin "53") (pinfunction "QSPI_SD0_53") (pintype "passive"))
      (node (ref "QU2") (pin "5") (pinfunction "DI(IO0)_5") (pintype "passive"))
    )
    (net (code "35") (name "/QSPI_SD1") (class "Default")
      (node (ref "QU1") (pin "55") (pinfunction "QSPI_SD1_55") (pintype "passive"))
      (node (ref "QU2") (pin "2") (pinfunction "DO(IO1)_2") (pintype "passive"))
    )
    (net (code "36") (name "/QSPI_SD2") (class "Default")
      (node (ref "QU1") (pin "54") (pinfunction "QSPI_SD2_54") (pintype "passive"))
      (node (ref "QU2") (pin "3") (pinfunction "WP#(IO2)_3") (pintype "passive"))
    )
    (net (code "37") (name "/QSPI_SD3") (class "Default")
      (node (ref "QU1") (pin "51") (pinfunction "QSPI_SD3_51") (pintype "passive"))
      (node (ref "QU2") (pin "7") (pinfunction "HOLD#_or_RESET#(IO3)_7") (pintype "passive"))
    )
    (net (code "38") (name "/QSPI_SS") (class "Default")
      (node (ref "QU1") (pin "56") (pinfunction "QSPI_SS_56") (pintype "passive"))
      (node (ref "QU2") (pin "1") (pinfunction "CS#_1") (pintype "passive"))
      (node (ref "R11") (pin "1") (pinfunction "1_1") (pintype "passive"))
      (node (ref "R12") (pin "2") (pinfunction "2_2") (pintype "passive"))
    )
    (net (code "39") (name "/RUN") (class "Default")
      (node (ref "QU1") (pin "26") (pinfunction "RUN_26") (pintype "passive"))
      (node (ref "RPRST") (pin "2") (pinfunction "2_2") (pintype "passive"))
    )
    (net (code "40") (name "/SWCLK") (class "Default")
      (node (ref "QU1") (pin "24") (pinfunction "SWCLK_24") (pintype "passive"))
      (node (ref "RPSWD") (pin "3") (pinfunction "3_3") (pintype "passive"))
    )
    (net (code "41") (name "/SWD") (class "Default")
      (node (ref "QU1") (pin "25") (pinfunction "SWD_25") (pintype "passive"))
      (node (ref "RPSWD") (pin "2") (pinfunction "2_2") (pintype "passive"))
    )
    (net (code "42") (name "/USB_D+") (class "Default")
      (node (ref "R7") (pin "2") (pinfunction "2_2") (pintype "passive"))
      (node (ref "RPUSB") (pin "3") (pinfunction "3_3") (pintype "passive"))
    )
    (net (code "43") (name "/USB_D-") (class "Default")
      (node (ref "R9") (pin "2") (pinfunction "2_2") (pintype "passive"))
      (node (ref "RPUSB") (pin "2") (pinfunction "2_2") (pintype "passive"))
    )
    (net (code "44") (name "/XIN") (class "Default")
      (node (ref "QU1") (pin "20") (pinfunction "XIN_20") (pintype "passive"))
      (node (ref "QX1") (pin "1") (pinfunction "OSC1_1") (pintype "passive"))
    )
    (net (code "45") (name "/XOUT") (class "Default")
      (node (ref "QU1") (pin "21") (pinfunction "XOUT_21") (pintype "passive"))
      (node (ref "QX1") (pin "3") (pinfunction "OSC2_3") (pintype "passive"))
    )
    (net (code "46") (name "GND") (class "Default")
      (node (ref "1") (pin "GND") (pinfunction "GND_GND") (pintype "passive"))
      (node (ref "1") (pin "GND1") (pinfunction "GND1_GND1") (pintype "passive"))
      (node (ref "1") (pin "GND2") (pinfunction "GND2_GND2") (pintype "passive"))
      (node (ref "1") (pin "GND4") (pinfunction "GND4_GND4") (pintype "passive"))
      (node (ref "1") (pin "GND5") (pinfunction "GND5_GND5") (pintype "passive"))
      (node (ref "BT1") (pin "2") (pinfunction "2_2") (pintype "passive"))
      (node (ref "C1") (pin "2") (pinfunction "2_2") (pintype "passive"))
      (node (ref "C10") (pin "1") (pinfunction "1_1") (pintype "passive"))
      (node (ref "C100") (pin "2") (pinfunction "2_2") (pintype "passive"))
      (node (ref "C101") (pin "2") (pinfunction "2_2") (pintype "passive"))
      (node (ref "C102") (pin "2") (pinfunction "2_2") (pintype "passive"))
      (node (ref "C103") (pin "2") (pinfunction "2_2") (pintype "passive"))
      (node (ref "C104") (pin "2") (pinfunction "2_2") (pintype "passive"))
      (node (ref "C105") (pin "2") (pinfunction "2_2") (pintype "passive"))
      (node (ref "C106") (pin "2") (pinfunction "2_2") (pintype "passive"))
      (node (ref "C107") (pin "2") (pinfunction "2_2") (pintype "passive"))
      (node (ref "C108") (pin "2") (pinfunction "2_2") (pintype "passive"))
      (node (ref "C109") (pin "2") (pinfunction "2_2") (pintype "passive"))
      (node (ref "C11") (pin "2") (pinfunction "2_2") (pintype "passive"))
      (node (ref "C110") (pin "2") (pinfunction "2_2") (pintype "passive"))
      (node (ref "C111") (pin "2") (pinfunction "2_2") (pintype "passive"))
      (node (ref "C112") (pin "2") (pinfunction "2_2") (pintype "passive"))
      (node (ref "C113") (pin "2") (pinfunction "2_2") (pintype "passive"))
      (node (ref "C114") (pin "2") (pinfunction "2_2") (pintype "passive"))
      (node (ref "C115") (pin "2") (pinfunction "2_2") (pintype "passive"))
      (node (ref "C116") (pin "2") (pinfunction "2_2") (pintype "passive"))
      (node (ref "C117") (pin "2") (pinfunction "2_2") (pintype "passive"))
      (node (ref "C118") (pin "2") (pinfunction "2_2") (pintype "passive"))
      (node (ref "C119") (pin "2") (pinfunction "2_2") (pintype "passive"))
      (node (ref "C12") (pin "2") (pinfunction "2_2") (pintype "passive"))
      (node (ref "C120") (pin "2") (pinfunction "2_2") (pintype "passive"))
      (node (ref "C121") (pin "2") (pinfunction "2_2") (pintype "passive"))
      (node (ref "C122") (pin "2") (pinfunction "2_2") (pintype "passive"))
      (node (ref "C123") (pin "2") (pinfunction "2_2") (pintype "passive"))
      (node (ref "C124") (pin "2") (pinfunction "2_2") (pintype "passive"))
      (node (ref "C125") (pin "1") (pinfunction "1_1") (pintype "passive"))
      (node (ref "C126") (pin "1") (pinfunction "1_1") (pintype "passive"))
      (node (ref "C127") (pin "1") (pinfunction "1_1") (pintype "passive"))
      (node (ref "C128") (pin "1") (pinfunction "1_1") (pintype "passive"))
      (node (ref "C129") (pin "1") (pinfunction "1_1") (pintype "passive"))
      (node (ref "C13") (pin "2") (pinfunction "2_2") (pintype "passive"))
      (node (ref "C130") (pin "2") (pinfunction "2_2") (pintype "passive"))
      (node (ref "C131") (pin "1") (pinfunction "1_1") (pintype "passive"))
      (node (ref "C132") (pin "1") (pinfunction "1_1") (pintype "passive"))
      (node (ref "C133") (pin "1") (pinfunction "1_1") (pintype "passive"))
      (node (ref "C14") (pin "2") (pinfunction "2_2") (pintype "passive"))
      (node (ref "C15") (pin "2") (pinfunction "2_2") (pintype "passive"))
      (node (ref "C16") (pin "2") (pinfunction "2_2") (pintype "passive"))
      (node (ref "C17") (pin "2") (pinfunction "2_2") (pintype "passive"))
      (node (ref "C18") (pin "2") (pinfunction "2_2") (pintype "passive"))
      (node (ref "C19") (pin "2") (pinfunction "2_2") (pintype "passive"))
      (node (ref "C2") (pin "1") (pinfunction "1_1") (pintype "passive"))
      (node (ref "C20") (pin "2") (pinfunction "2_2") (pintype "passive"))
      (node (ref "C21") (pin "2") (pinfunction "2_2") (pintype "passive"))
      (node (ref "C22") (pin "2") (pinfunction "2_2") (pintype "passive"))
      (node (ref "C23") (pin "2") (pinfunction "2_2") (pintype "passive"))
      (node (ref "C24") (pin "2") (pinfunction "2_2") (pintype "passive"))
      (node (ref "C25") (pin "2") (pinfunction "2_2") (pintype "passive"))
      (node (ref "C26") (pin "2") (pinfunction "2_2") (pintype "passive"))
      (node (ref "C27") (pin "2") (pinfunction "2_2") (pintype "passive"))
      (node (ref "C28") (pin "2") (pinfunction "2_2") (pintype "passive"))
      (node (ref "C29") (pin "2") (pinfunction "2_2") (pintype "passive"))
      (node (ref "C3") (pin "2") (pinfunction "2_2") (pintype "passive"))
      (node (ref "C30") (pin "2") (pinfunction "2_2") (pintype "passive"))
      (node (ref "C31") (pin "2") (pinfunction "2_2") (pintype "passive"))
      (node (ref "C32") (pin "2") (pinfunction "2_2") (pintype "passive"))
      (node (ref "C33") (pin "2") (pinfunction "2_2") (pintype "passive"))
      (node (ref "C34") (pin "2") (pinfunction "2_2") (pintype "passive"))
      (node (ref "C35") (pin "2") (pinfunction "2_2") (pintype "passive"))
      (node (ref "C36") (pin "2") (pinfunction "2_2") (pintype "passive"))
      (node (ref "C37") (pin "2") (pinfunction "2_2") (pintype "passive"))
      (node (ref "C38") (pin "2") (pinfunction "2_2") (pintype "passive"))
      (node (ref "C39") (pin "2") (pinfunction "2_2") (pintype "passive"))
      (node (ref "C4") (pin "2") (pinfunction "2_2") (pintype "passive"))
      (node (ref "C40") (pin "2") (pinfunction "2_2") (pintype "passive"))
      (node (ref "C41") (pin "2") (pinfunction "2_2") (pintype "passive"))
      (node (ref "C42") (pin "2") (pinfunction "2_2") (pintype "passive"))
      (node (ref "C43") (pin "2") (pinfunction "2_2") (pintype "passive"))
      (node (ref "C44") (pin "2") (pinfunction "2_2") (pintype "passive"))
      (node (ref "C45") (pin "2") (pinfunction "2_2") (pintype "passive"))
      (node (ref "C46") (pin "2") (pinfunction "2_2") (pintype "passive"))
      (node (ref "C47") (pin "2") (pinfunction "2_2") (pintype "passive"))
      (node (ref "C48") (pin "2") (pinfunction "2_2") (pintype "passive"))
      (node (ref "C49") (pin "2") (pinfunction "2_2") (pintype "passive"))
      (node (ref "C5") (pin "2") (pinfunction "2_2") (pintype "passive"))
      (node (ref "C50") (pin "2") (pinfunction "2_2") (pintype "passive"))
      (node (ref "C51") (pin "2") (pinfunction "2_2") (pintype "passive"))
      (node (ref "C52") (pin "2") (pinfunction "2_2") (pintype "passive"))
      (node (ref "C53") (pin "2") (pinfunction "2_2") (pintype "passive"))
      (node (ref "C54") (pin "2") (pinfunction "2_2") (pintype "passive"))
      (node (ref "C55") (pin "2") (pinfunction "2_2") (pintype "passive"))
      (node (ref "C56") (pin "2") (pinfunction "2_2") (pintype "passive"))
      (node (ref "C57") (pin "2") (pinfunction "2_2") (pintype "passive"))
      (node (ref "C58") (pin "2") (pinfunction "2_2") (pintype "passive"))
      (node (ref "C59") (pin "2") (pinfunction "2_2") (pintype "passive"))
      (node (ref "C6") (pin "1") (pinfunction "1_1") (pintype "passive"))
      (node (ref "C60") (pin "2") (pinfunction "2_2") (pintype "passive"))
      (node (ref "C61") (pin "2") (pinfunction "2_2") (pintype "passive"))
      (node (ref "C62") (pin "2") (pinfunction "2_2") (pintype "passive"))
      (node (ref "C63") (pin "2") (pinfunction "2_2") (pintype "passive"))
      (node (ref "C64") (pin "2") (pinfunction "2_2") (pintype "passive"))
      (node (ref "C65") (pin "2") (pinfunction "2_2") (pintype "passive"))
      (node (ref "C66") (pin "2") (pinfunction "2_2") (pintype "passive"))
      (node (ref "C67") (pin "2") (pinfunction "2_2") (pintype "passive"))
      (node (ref "C68") (pin "2") (pinfunction "2_2") (pintype "passive"))
      (node (ref "C69") (pin "2") (pinfunction "2_2") (pintype "passive"))
      (node (ref "C7") (pin "2") (pinfunction "2_2") (pintype "passive"))
      (node (ref "C70") (pin "2") (pinfunction "2_2") (pintype "passive"))
      (node (ref "C71") (pin "2") (pinfunction "2_2") (pintype "passive"))
      (node (ref "C72") (pin "2") (pinfunction "2_2") (pintype "passive"))
      (node (ref "C73") (pin "2") (pinfunction "2_2") (pintype "passive"))
      (node (ref "C74") (pin "2") (pinfunction "2_2") (pintype "passive"))
      (node (ref "C75") (pin "2") (pinfunction "2_2") (pintype "passive"))
      (node (ref "C76") (pin "2") (pinfunction "2_2") (pintype "passive"))
      (node (ref "C77") (pin "2") (pinfunction "2_2") (pintype "passive"))
      (node (ref "C78") (pin "2") (pinfunction "2_2") (pintype "passive"))
      (node (ref "C79") (pin "2") (pinfunction "2_2") (pintype "passive"))
      (node (ref "C8") (pin "2") (pinfunction "2_2") (pintype "passive"))
      (node (ref "C80") (pin "2") (pinfunction "2_2") (pintype "passive"))
      (node (ref "C81") (pin "2") (pinfunction "2_2") (pintype "passive"))
      (node (ref "C82") (pin "2") (pinfunction "2_2") (pintype "passive"))
      (node (ref "C83") (pin "2") (pinfunction "2_2") (pintype "passive"))
      (node (ref "C84") (pin "2") (pinfunction "2_2") (pintype "passive"))
      (node (ref "C85") (pin "2") (pinfunction "2_2") (pintype "passive"))
      (node (ref "C86") (pin "2") (pinfunction "2_2") (pintype "passive"))
      (node (ref "C87") (pin "2") (pinfunction "2_2") (pintype "passive"))
      (node (ref "C88") (pin "2") (pinfunction "2_2") (pintype "passive"))
      (node (ref "C89") (pin "2") (pinfunction "2_2") (pintype "passive"))
      (node (ref "C9") (pin "2") (pinfunction "2_2") (pintype "passive"))
      (node (ref "C90") (pin "2") (pinfunction "2_2") (pintype "passive"))
      (node (ref "C91") (pin "2") (pinfunction "2_2") (pintype "passive"))
      (node (ref "C92") (pin "2") (pinfunction "2_2") (pintype "passive"))
      (node (ref "C93") (pin "2") (pinfunction "2_2") (pintype "passive"))
      (node (ref "C94") (pin "2") (pinfunction "2_2") (pintype "passive"))
      (node (ref "C95") (pin "2") (pinfunction "2_2") (pintype "passive"))
      (node (ref "C96") (pin "2") (pinfunction "2_2") (pintype "passive"))
      (node (ref "C97") (pin "2") (pinfunction "2_2") (pintype "passive"))
      (node (ref "C98") (pin "2") (pinfunction "2_2") (pintype "passive"))
      (node (ref "C99") (pin "2") (pinfunction "2_2") (pintype "passive"))
      (node (ref "ESPRST") (pin "4") (pinfunction "4_4") (pintype "passive"))
      (node (ref "H1") (pin "3") (pinfunction "3_3") (pintype "passive"))
      (node (ref "H10") (pin "3") (pinfunction "3_3") (pintype "passive"))
      (node (ref "H11") (pin "3") (pinfunction "3_3") (pintype "passive"))
      (node (ref "H12") (pin "3") (pinfunction "3_3") (pintype "passive"))
      (node (ref "H13") (pin "3") (pinfunction "3_3") (pintype "passive"))
      (node (ref "H14") (pin "3") (pinfunction "3_3") (pintype "passive"))
      (node (ref "H15") (pin "3") (pinfunction "3_3") (pintype "passive"))
      (node (ref "H16") (pin "3") (pinfunction "3_3") (pintype "passive"))
      (node (ref "H17") (pin "3") (pinfunction "3_3") (pintype "passive"))
      (node (ref "H18") (pin "3") (pinfunction "3_3") (pintype "passive"))
      (node (ref "H19") (pin "3") (pinfunction "3_3") (pintype "passive"))
      (node (ref "H2") (pin "3") (pinfunction "3_3") (pintype "passive"))
      (node (ref "H20") (pin "3") (pinfunction "3_3") (pintype "passive"))
      (node (ref "H21") (pin "3") (pinfunction "3_3") (pintype "passive"))
      (node (ref "H22") (pin "1") (pinfunction "1_1") (pintype "passive"))
      (node (ref "H23") (pin "3") (pinfunction "3_3") (pintype "passive"))
      (node (ref "H24") (pin "3") (pinfunction "3_3") (pintype "passive"))
      (node (ref "H3") (pin "3") (pinfunction "3_3") (pintype "passive"))
      (node (ref "H4") (pin "3") (pinfunction "3_3") (pintype "passive"))
      (node (ref "H5") (pin "3") (pinfunction "3_3") (pintype "passive"))
      (node (ref "H6") (pin "3") (pinfunction "3_3") (pintype "passive"))
      (node (ref "H7") (pin "3") (pinfunction "3_3") (pintype "passive"))
      (node (ref "H8") (pin "3") (pinfunction "3_3") (pintype "passive"))
      (node (ref "H9") (pin "3") (pinfunction "3_3") (pintype "passive"))
      (node (ref "LED1") (pin "3") (pinfunction "VSS_3") (pintype "passive"))
      (node (ref "LED10") (pin "3") (pinfunction "VSS_3") (pintype "passive"))
      (node (ref "LED100") (pin "3") (pinfunction "VSS_3") (pintype "passive"))
      (node (ref "LED101") (pin "3") (pinfunction "VSS_3") (pintype "passive"))
      (node (ref "LED102") (pin "3") (pinfunction "VSS_3") (pintype "passive"))
      (node (ref "LED103") (pin "3") (pinfunction "VSS_3") (pintype "passive"))
      (node (ref "LED104") (pin "3") (pinfunction "VSS_3") (pintype "passive"))
      (node (ref "LED105") (pin "3") (pinfunction "VSS_3") (pintype "passive"))
      (node (ref "LED106") (pin "3") (pinfunction "VSS_3") (pintype "passive"))
      (node (ref "LED107") (pin "3") (pinfunction "VSS_3") (pintype "passive"))
      (node (ref "LED108") (pin "3") (pinfunction "VSS_3") (pintype "passive"))
      (node (ref "LED109") (pin "3") (pinfunction "VSS_3") (pintype "passive"))
      (node (ref "LED11") (pin "3") (pinfunction "VSS_3") (pintype "passive"))
      (node (ref "LED110") (pin "3") (pinfunction "VSS_3") (pintype "passive"))
      (node (ref "LED111") (pin "3") (pinfunction "VSS_3") (pintype "passive"))
      (node (ref "LED112") (pin "3") (pinfunction "VSS_3") (pintype "passive"))
      (node (ref "LED113") (pin "3") (pinfunction "VSS_3") (pintype "passive"))
      (node (ref "LED114") (pin "3") (pinfunction "VSS_3") (pintype "passive"))
      (node (ref "LED115") (pin "3") (pinfunction "VSS_3") (pintype "passive"))
      (node (ref "LED116") (pin "1") (pinfunction "-_1") (pintype "passive"))
      (node (ref "LED12") (pin "3") (pinfunction "VSS_3") (pintype "passive"))
      (node (ref "LED13") (pin "3") (pinfunction "VSS_3") (pintype "passive"))
      (node (ref "LED14") (pin "3") (pinfunction "VSS_3") (pintype "passive"))
      (node (ref "LED15") (pin "3") (pinfunction "VSS_3") (pintype "passive"))
      (node (ref "LED16") (pin "3") (pinfunction "VSS_3") (pintype "passive"))
      (node (ref "LED17") (pin "3") (pinfunction "VSS_3") (pintype "passive"))
      (node (ref "LED18") (pin "3") (pinfunction "VSS_3") (pintype "passive"))
      (node (ref "LED19") (pin "3") (pinfunction "VSS_3") (pintype "passive"))
      (node (ref "LED2") (pin "3") (pinfunction "VSS_3") (pintype "passive"))
      (node (ref "LED20") (pin "3") (pinfunction "VSS_3") (pintype "passive"))
      (node (ref "LED21") (pin "3") (pinfunction "VSS_3") (pintype "passive"))
      (node (ref "LED22") (pin "3") (pinfunction "VSS_3") (pintype "passive"))
      (node (ref "LED23") (pin "3") (pinfunction "VSS_3") (pintype "passive"))
      (node (ref "LED24") (pin "3") (pinfunction "VSS_3") (pintype "passive"))
      (node (ref "LED25") (pin "3") (pinfunction "VSS_3") (pintype "passive"))
      (node (ref "LED26") (pin "3") (pinfunction "VSS_3") (pintype "passive"))
      (node (ref "LED27") (pin "3") (pinfunction "VSS_3") (pintype "passive"))
      (node (ref "LED28") (pin "3") (pinfunction "VSS_3") (pintype "passive"))
      (node (ref "LED29") (pin "3") (pinfunction "VSS_3") (pintype "passive"))
      (node (ref "LED3") (pin "3") (pinfunction "VSS_3") (pintype "passive"))
      (node (ref "LED30") (pin "3") (pinfunction "VSS_3") (pintype "passive"))
      (node (ref "LED31") (pin "3") (pinfunction "VSS_3") (pintype "passive"))
      (node (ref "LED32") (pin "3") (pinfunction "VSS_3") (pintype "passive"))
      (node (ref "LED33") (pin "3") (pinfunction "VSS_3") (pintype "passive"))
      (node (ref "LED34") (pin "3") (pinfunction "VSS_3") (pintype "passive"))
      (node (ref "LED35") (pin "3") (pinfunction "VSS_3") (pintype "passive"))
      (node (ref "LED36") (pin "3") (pinfunction "VSS_3") (pintype "passive"))
      (node (ref "LED37") (pin "3") (pinfunction "VSS_3") (pintype "passive"))
      (node (ref "LED38") (pin "3") (pinfunction "VSS_3") (pintype "passive"))
      (node (ref "LED39") (pin "3") (pinfunction "VSS_3") (pintype "passive"))
      (node (ref "LED4") (pin "3") (pinfunction "VSS_3") (pintype "passive"))
      (node (ref "LED40") (pin "3") (pinfunction "VSS_3") (pintype "passive"))
      (node (ref "LED41") (pin "3") (pinfunction "VSS_3") (pintype "passive"))
      (node (ref "LED42") (pin "3") (pinfunction "VSS_3") (pintype "passive"))
      (node (ref "LED43") (pin "3") (pinfunction "VSS_3") (pintype "passive"))
      (node (ref "LED44") (pin "3") (pinfunction "VSS_3") (pintype "passive"))
      (node (ref "LED45") (pin "3") (pinfunction "VSS_3") (pintype "passive"))
      (node (ref "LED46") (pin "3") (pinfunction "VSS_3") (pintype "passive"))
      (node (ref "LED47") (pin "3") (pinfunction "VSS_3") (pintype "passive"))
      (node (ref "LED48") (pin "3") (pinfunction "VSS_3") (pintype "passive"))
      (node (ref "LED49") (pin "3") (pinfunction "VSS_3") (pintype "passive"))
      (node (ref "LED5") (pin "3") (pinfunction "VSS_3") (pintype "passive"))
      (node (ref "LED50") (pin "3") (pinfunction "VSS_3") (pintype "passive"))
      (node (ref "LED51") (pin "3") (pinfunction "VSS_3") (pintype "passive"))
      (node (ref "LED52") (pin "3") (pinfunction "VSS_3") (pintype "passive"))
      (node (ref "LED53") (pin "3") (pinfunction "VSS_3") (pintype "passive"))
      (node (ref "LED54") (pin "3") (pinfunction "VSS_3") (pintype "passive"))
      (node (ref "LED55") (pin "3") (pinfunction "VSS_3") (pintype "passive"))
      (node (ref "LED56") (pin "3") (pinfunction "VSS_3") (pintype "passive"))
      (node (ref "LED57") (pin "3") (pinfunction "VSS_3") (pintype "passive"))
      (node (ref "LED58") (pin "3") (pinfunction "VSS_3") (pintype "passive"))
      (node (ref "LED59") (pin "3") (pinfunction "VSS_3") (pintype "passive"))
      (node (ref "LED6") (pin "3") (pinfunction "VSS_3") (pintype "passive"))
      (node (ref "LED60") (pin "3") (pinfunction "VSS_3") (pintype "passive"))
      (node (ref "LED61") (pin "3") (pinfunction "VSS_3") (pintype "passive"))
      (node (ref "LED62") (pin "3") (pinfunction "VSS_3") (pintype "passive"))
      (node (ref "LED63") (pin "3") (pinfunction "VSS_3") (pintype "passive"))
      (node (ref "LED64") (pin "3") (pinfunction "VSS_3") (pintype "passive"))
      (node (ref "LED65") (pin "3") (pinfunction "VSS_3") (pintype "passive"))
      (node (ref "LED66") (pin "3") (pinfunction "VSS_3") (pintype "passive"))
      (node (ref "LED67") (pin "3") (pinfunction "VSS_3") (pintype "passive"))
      (node (ref "LED68") (pin "3") (pinfunction "VSS_3") (pintype "passive"))
      (node (ref "LED69") (pin "3") (pinfunction "VSS_3") (pintype "passive"))
      (node (ref "LED7") (pin "3") (pinfunction "VSS_3") (pintype "passive"))
      (node (ref "LED70") (pin "3") (pinfunction "VSS_3") (pintype "passive"))
      (node (ref "LED71") (pin "3") (pinfunction "VSS_3") (pintype "passive"))
      (node (ref "LED72") (pin "3") (pinfunction "VSS_3") (pintype "passive"))
      (node (ref "LED73") (pin "3") (pinfunction "VSS_3") (pintype "passive"))
      (node (ref "LED74") (pin "3") (pinfunction "VSS_3") (pintype "passive"))
      (node (ref "LED75") (pin "3") (pinfunction "VSS_3") (pintype "passive"))
      (node (ref "LED76") (pin "3") (pinfunction "VSS_3") (pintype "passive"))
      (node (ref "LED77") (pin "3") (pinfunction "VSS_3") (pintype "passive"))
      (node (ref "LED78") (pin "3") (pinfunction "VSS_3") (pintype "passive"))
      (node (ref "LED79") (pin "3") (pinfunction "VSS_3") (pintype "passive"))
      (node (ref "LED8") (pin "3") (pinfunction "VSS_3") (pintype "passive"))
      (node (ref "LED80") (pin "3") (pinfunction "VSS_3") (pintype "passive"))
      (node (ref "LED81") (pin "3") (pinfunction "VSS_3") (pintype "passive"))
      (node (ref "LED82") (pin "3") (pinfunction "VSS_3") (pintype "passive"))
      (node (ref "LED83") (pin "3") (pinfunction "VSS_3") (pintype "passive"))
      (node (ref "LED84") (pin "3") (pinfunction "VSS_3") (pintype "passive"))
      (node (ref "LED85") (pin "3") (pinfunction "VSS_3") (pintype "passive"))
      (node (ref "LED86") (pin "3") (pinfunction "VSS_3") (pintype "passive"))
      (node (ref "LED87") (pin "3") (pinfunction "VSS_3") (pintype "passive"))
      (node (ref "LED88") (pin "3") (pinfunction "VSS_3") (pintype "passive"))
      (node (ref "LED89") (pin "3") (pinfunction "VSS_3") (pintype "passive"))
      (node (ref "LED9") (pin "3") (pinfunction "VSS_3") (pintype "passive"))
      (node (ref "LED90") (pin "3") (pinfunction "VSS_3") (pintype "passive"))
      (node (ref "LED91") (pin "3") (pinfunction "VSS_3") (pintype "passive"))
      (node (ref "LED92") (pin "3") (pinfunction "VSS_3") (pintype "passive"))
      (node (ref "LED93") (pin "3") (pinfunction "VSS_3") (pintype "passive"))
      (node (ref "LED94") (pin "3") (pinfunction "VSS_3") (pintype "passive"))
      (node (ref "LED95") (pin "3") (pinfunction "VSS_3") (pintype "passive"))
      (node (ref "LED96") (pin "3") (pinfunction "VSS_3") (pintype "passive"))
      (node (ref "LED97") (pin "3") (pinfunction "VSS_3") (pintype "passive"))
      (node (ref "LED98") (pin "3") (pinfunction "VSS_3") (pintype "passive"))
      (node (ref "LED99") (pin "3") (pinfunction "VSS_3") (pintype "passive"))
      (node (ref "M1") (pin "1") (pinfunction "GND_1") (pintype "passive"))
      (node (ref "QBOOT") (pin "4") (pinfunction "4_4") (pintype "passive"))
      (node (ref "QU1") (pin "19") (pinfunction "TESTEN_19") (pintype "passive"))
      (node (ref "QU1") (pin "57") (pinfunction "GND_57") (pintype "passive"))
      (node (ref "QU2") (pin "4") (pinfunction "GND_4") (pintype "passive"))
      (node (ref "QX1") (pin "2") (pinfunction "GND_2") (pintype "passive"))
      (node (ref "QX1") (pin "4") (pinfunction "GND_4") (pintype "passive"))
      (node (ref "R1") (pin "2") (pinfunction "2_2") (pintype "passive"))
      (node (ref "R5") (pin "1") (pinfunction "1_1") (pintype "passive"))
      (node (ref "RPRST") (pin "4") (pinfunction "4_4") (pintype "passive"))
      (node (ref "RPSWD") (pin "4") (pinfunction "4_4") (pintype "passive"))
      (node (ref "RPUSB") (pin "4") (pinfunction "4_4") (pintype "passive"))
      (node (ref "U1") (pin "3") (pinfunction "GND_3") (pintype "passive"))
      (node (ref "U2") (pin "1") (pinfunction "GND_1") (pintype "passive"))
      (node (ref "U3") (pin "4") (pinfunction "GND_4") (pintype "passive"))
    )
    (net (code "47") (name "Net-(D1-C)") (class "Default")
      (node (ref "C4") (pin "1") (pinfunction "1_1") (pintype "passive"))
      (node (ref "D1") (pin "1") (pinfunction "C_1") (pintype "passive"))
      (node (ref "JP4") (pin "2") (pinfunction "2_2") (pintype "passive"))
      (node (ref "LED2") (pin "1") (pinfunction "VDD_1") (pintype "passive"))
    )
    (net (code "48") (name "Net-(H24-Pad2)") (class "Default")
      (node (ref "H24") (pin "2") (pinfunction "2_2") (pintype "passive"))
      (node (ref "JP6") (pin "2") (pinfunction "2_2") (pintype "passive"))
      (node (ref "JP7") (pin "2") (pinfunction "2_2") (pintype "passive"))
      (node (ref "R10") (pin "1") (pinfunction "1_1") (pintype "passive"))
    )
    (net (code "49") (name "Net-(LED1-DIN)") (class "Default")
      (node (ref "LED1") (pin "4") (pinfunction "DIN_4") (pintype "passive"))
      (node (ref "LED16") (pin "2") (pinfunction "DOUT_2") (pintype "passive"))
    )
    (net (code "50") (name "Net-(LED1-DOUT)") (class "Default")
      (node (ref "LED1") (pin "2") (pinfunction "DOUT_2") (pintype "passive"))
      (node (ref "LED3") (pin "4") (pinfunction "DIN_4") (pintype "passive"))
    )
    (net (code "51") (name "Net-(LED2-DIN)") (class "Default")
      (node (ref "JP1") (pin "2") (pinfunction "2_2") (pintype "passive"))
      (node (ref "JP2") (pin "2") (pinfunction "2_2") (pintype "passive"))
      (node (ref "JP5") (pin "2") (pinfunction "2_2") (pintype "passive"))
      (node (ref "LED2") (pin "4") (pinfunction "DIN_4") (pintype "passive"))
    )
    (net (code "52") (name "Net-(LED2-DOUT)") (class "Default")
      (node (ref "H23") (pin "2") (pinfunction "2_2") (pintype "passive"))
      (node (ref "JP2") (pin "1") (pinfunction "1_1") (pintype "passive"))
      (node (ref "JP3") (pin "2") (pinfunction "2_2") (pintype "passive"))
      (node (ref "LED2") (pin "2") (pinfunction "DOUT_2") (pintype "passive"))
    )
    (net (code "53") (name "Net-(LED6-DOUT)") (class "Default")
      (node (ref "LED6") (pin "2") (pinfunction "DOUT_2") (pintype "passive"))
      (node (ref "LED7") (pin "4") (pinfunction "DIN_4") (pintype "passive"))
    )
    (net (code "54") (name "Net-(LED8-DOUT)") (class "Default")
      (node (ref "LED8") (pin "2") (pinfunction "DOUT_2") (pintype "passive"))
      (node (ref "LED9") (pin "4") (pinfunction "DIN_4") (pintype "passive"))
    )
    (net (code "55") (name "Net-(LED10-DIN)") (class "Default")
      (node (ref "LED10") (pin "4") (pinfunction "DIN_4") (pintype "passive"))
      (node (ref "LED9") (pin "2") (pinfunction "DOUT_2") (pintype "passive"))
    )
    (net (code "56") (name "Net-(LED10-DOUT)") (class "Default")
      (node (ref "LED10") (pin "2") (pinfunction "DOUT_2") (pintype "passive"))
      (node (ref "LED11") (pin "4") (pinfunction "DIN_4") (pintype "passive"))
    )
    (net (code "57") (name "Net-(LED11-DOUT)") (class "Default")
      (node (ref "LED11") (pin "2") (pinfunction "DOUT_2") (pintype "passive"))
      (node (ref "LED12") (pin "4") (pinfunction "DIN_4") (pintype "passive"))
    )
    (net (code "58") (name "Net-(LED12-DOUT)") (class "Default")
      (node (ref "LED12") (pin "2") (pinfunction "DOUT_2") (pintype "passive"))
      (node (ref "LED15") (pin "4") (pinfunction "DIN_4") (pintype "passive"))
    )
    (net (code "59") (name "Net-(LED13-DIN)") (class "Default")
      (node (ref "LED13") (pin "4") (pinfunction "DIN_4") (pintype "passive"))
      (node (ref "LED14") (pin "2") (pinfunction "DOUT_2") (pintype "passive"))
    )
    (net (code "60") (name "Net-(LED13-DOUT)") (class "Default")
      (node (ref "LED13") (pin "2") (pinfunction "DOUT_2") (pintype "passive"))
      (node (ref "LED16") (pin "4") (pinfunction "DIN_4") (pintype "passive"))
    )
    (net (code "61") (name "Net-(LED14-DIN)") (class "Default")
      (node (ref "LED14") (pin "4") (pinfunction "DIN_4") (pintype "passive"))
      (node (ref "LED15") (pin "2") (pinfunction "DOUT_2") (pintype "passive"))
    )
    (net (code "62") (name "Net-(LED17-DIN)") (class "Default")
      (node (ref "LED17") (pin "4") (pinfunction "DIN_4") (pintype "passive"))
      (node (ref "LED7") (pin "2") (pinfunction "DOUT_2") (pintype "passive"))
    )
    (net (code "63") (name "Net-(LED17-DOUT)") (class "Default")
      (node (ref "LED17") (pin "2") (pinfunction "DOUT_2") (pintype "passive"))
      (node (ref "LED5") (pin "4") (pinfunction "DIN_4") (pintype "passive"))
    )
    (net (code "64") (name "Net-(LED18-DIN)") (class "Default")
      (node (ref "LED18") (pin "4") (pinfunction "DIN_4") (pintype "passive"))
      (node (ref "LED19") (pin "2") (pinfunction "DOUT_2") (pintype "passive"))
    )
    (net (code "65") (name "Net-(LED18-DOUT)") (class "Default")
      (node (ref "LED18") (pin "2") (pinfunction "DOUT_2") (pintype "passive"))
      (node (ref "LED6") (pin "4") (pinfunction "DIN_4") (pintype "passive"))
    )
    (net (code "66") (name "Net-(LED19-DIN)") (class "Default")
      (node (ref "LED19") (pin "4") (pinfunction "DIN_4") (pintype "passive"))
      (node (ref "LED20") (pin "2") (pinfunction "DOUT_2") (pintype "passive"))
    )
    (net (code "67") (name "Net-(LED20-DIN)") (class "Default")
      (node (ref "LED20") (pin "4") (pinfunction "DIN_4") (pintype "passive"))
      (node (ref "LED21") (pin "2") (pinfunction "DOUT_2") (pintype "passive"))
    )
    (net (code "68") (name "Net-(LED21-DIN)") (class "Default")
      (node (ref "LED21") (pin "4") (pinfunction "DIN_4") (pintype "passive"))
      (node (ref "LED22") (pin "2") (pinfunction "DOUT_2") (pintype "passive"))
    )
    (net (code "69") (name "Net-(LED23-DIN)") (class "Default")
      (node (ref "LED23") (pin "4") (pinfunction "DIN_4") (pintype "passive"))
      (node (ref "LED5") (pin "2") (pinfunction "DOUT_2") (pintype "passive"))
    )
    (net (code "70") (name "Net-(LED23-DOUT)") (class "Default")
      (node (ref "LED23") (pin "2") (pinfunction "DOUT_2") (pintype "passive"))
      (node (ref "LED4") (pin "4") (pinfunction "DIN_4") (pintype "passive"))
    )
    (net (code "71") (name "Net-(LED24-DIN)") (class "Default")
      (node (ref "LED24") (pin "4") (pinfunction "DIN_4") (pintype "passive"))
      (node (ref "LED33") (pin "2") (pinfunction "DOUT_2") (pintype "passive"))
    )
    (net (code "72") (name "Net-(LED24-DOUT)") (class "Default")
      (node (ref "LED24") (pin "2") (pinfunction "DOUT_2") (pintype "passive"))
      (node (ref "LED34") (pin "4") (pinfunction "DIN_4") (pintype "passive"))
    )
    (net (code "73") (name "Net-(LED25-DIN)") (class "Default")
      (node (ref "H1") (pin "2") (pinfunction "2_2") (pintype "passive"))
      (node (ref "H5") (pin "2") (pinfunction "2_2") (pintype "passive"))
      (node (ref "LED25") (pin "4") (pinfunction "DIN_4") (pintype "passive"))
      (node (ref "LED4") (pin "2") (pinfunction "DOUT_2") (pintype "passive"))
    )
    (net (code "74") (name "Net-(LED25-DOUT)") (class "Default")
      (node (ref "LED25") (pin "2") (pinfunction "DOUT_2") (pintype "passive"))
      (node (ref "LED26") (pin "4") (pinfunction "DIN_4") (pintype "passive"))
    )
    (net (code "75") (name "Net-(LED26-DOUT)") (class "Default")
      (node (ref "LED26") (pin "2") (pinfunction "DOUT_2") (pintype "passive"))
      (node (ref "LED27") (pin "4") (pinfunction "DIN_4") (pintype "passive"))
    )
    (net (code "76") (name "Net-(LED27-DOUT)") (class "Default")
      (node (ref "LED27") (pin "2") (pinfunction "DOUT_2") (pintype "passive"))
      (node (ref "LED28") (pin "4") (pinfunction "DIN_4") (pintype "passive"))
    )
    (net (code "77") (name "Net-(LED28-DOUT)") (class "Default")
      (node (ref "LED28") (pin "2") (pinfunction "DOUT_2") (pintype "passive"))
      (node (ref "LED29") (pin "4") (pinfunction "DIN_4") (pintype "passive"))
    )
    (net (code "78") (name "Net-(LED29-DOUT)") (class "Default")
      (node (ref "LED29") (pin "2") (pinfunction "DOUT_2") (pintype "passive"))
      (node (ref "LED32") (pin "4") (pinfunction "DIN_4") (pintype "passive"))
    )
    (net (code "79") (name "Net-(LED30-DIN)") (class "Default")
      (node (ref "LED30") (pin "4") (pinfunction "DIN_4") (pintype "passive"))
      (node (ref "LED31") (pin "2") (pinfunction "DOUT_2") (pintype "passive"))
    )
    (net (code "80") (name "Net-(LED30-DOUT)") (class "Default")
      (node (ref "LED30") (pin "2") (pinfunction "DOUT_2") (pintype "passive"))
      (node (ref "LED33") (pin "4") (pinfunction "DIN_4") (pintype "passive"))
    )
    (net (code "81") (name "Net-(LED31-DIN)") (class "Default")
      (node (ref "LED31") (pin "4") (pinfunction "DIN_4") (pintype "passive"))
      (node (ref "LED32") (pin "2") (pinfunction "DOUT_2") (pintype "passive"))
    )
    (net (code "82") (name "Net-(LED34-DOUT)") (class "Default")
      (node (ref "H6") (pin "2") (pinfunction "2_2") (pintype "passive"))
      (node (ref "H8") (pin "2") (pinfunction "2_2") (pintype "passive"))
      (node (ref "LED34") (pin "2") (pinfunction "DOUT_2") (pintype "passive"))
      (node (ref "LED44") (pin "4") (pinfunction "DIN_4") (pintype "passive"))
    )
    (net (code "83") (name "Net-(LED35-DIN)") (class "Default")
      (node (ref "LED35") (pin "4") (pinfunction "DIN_4") (pintype "passive"))
      (node (ref "LED45") (pin "2") (pinfunction "DOUT_2") (pintype "passive"))
    )
    (net (code "84") (name "Net-(LED35-DOUT)") (class "Default")
      (node (ref "H7") (pin "2") (pinfunction "2_2") (pintype "passive"))
      (node (ref "H9") (pin "2") (pinfunction "2_2") (pintype "passive"))
      (node (ref "LED35") (pin "2") (pinfunction "DOUT_2") (pintype "passive"))
      (node (ref "LED47") (pin "4") (pinfunction "DIN_4") (pintype "passive"))
    )
    (net (code "85") (name "Net-(LED36-DIN)") (class "Default")
      (node (ref "LED36") (pin "4") (pinfunction "DIN_4") (pintype "passive"))
      (node (ref "LED39") (pin "2") (pinfunction "DOUT_2") (pintype "passive"))
    )
    (net (code "86") (name "Net-(LED36-DOUT)") (class "Default")
      (node (ref "LED36") (pin "2") (pinfunction "DOUT_2") (pintype "passive"))
      (node (ref "LED45") (pin "4") (pinfunction "DIN_4") (pintype "passive"))
    )
    (net (code "87") (name "Net-(LED37-DIN)") (class "Default")
      (node (ref "LED37") (pin "4") (pinfunction "DIN_4") (pintype "passive"))
      (node (ref "LED40") (pin "2") (pinfunction "DOUT_2") (pintype "passive"))
    )
    (net (code "88") (name "Net-(LED37-DOUT)") (class "Default")
      (node (ref "LED37") (pin "2") (pinfunction "DOUT_2") (pintype "passive"))
      (node (ref "LED38") (pin "4") (pinfunction "DIN_4") (pintype "passive"))
    )
    (net (code "89") (name "Net-(LED38-DOUT)") (class "Default")
      (node (ref "LED38") (pin "2") (pinfunction "DOUT_2") (pintype "passive"))
      (node (ref "LED39") (pin "4") (pinfunction "DIN_4") (pintype "passive"))
    )
    (net (code "90") (name "Net-(LED40-DIN)") (class "Default")
      (node (ref "LED40") (pin "4") (pinfunction "DIN_4") (pintype "passive"))
      (node (ref "LED41") (pin "2") (pinfunction "DOUT_2") (pintype "passive"))
    )
    (net (code "91") (name "Net-(LED41-DIN)") (class "Default")
      (node (ref "LED41") (pin "4") (pinfunction "DIN_4") (pintype "passive"))
      (node (ref "LED42") (pin "2") (pinfunction "DOUT_2") (pintype "passive"))
    )
    (net (code "92") (name "Net-(LED42-DIN)") (class "Default")
      (node (ref "LED42") (pin "4") (pinfunction "DIN_4") (pintype "passive"))
      (node (ref "LED43") (pin "2") (pinfunction "DOUT_2") (pintype "passive"))
    )
    (net (code "93") (name "Net-(LED43-DIN)") (class "Default")
      (node (ref "LED43") (pin "4") (pinfunction "DIN_4") (pintype "passive"))
      (node (ref "LED44") (pin "2") (pinfunction "DOUT_2") (pintype "passive"))
    )
    (net (code "94") (name "Net-(LED46-DIN)") (class "Default")
      (node (ref "LED46") (pin "4") (pinfunction "DIN_4") (pintype "passive"))
      (node (ref "LED55") (pin "2") (pinfunction "DOUT_2") (pintype "passive"))
    )
    (net (code "95") (name "Net-(LED46-DOUT)") (class "Default")
      (node (ref "LED46") (pin "2") (pinfunction "DOUT_2") (pintype "passive"))
      (node (ref "LED56") (pin "4") (pinfunction "DIN_4") (pintype "passive"))
    )
    (net (code "96") (name "Net-(LED47-DOUT)") (class "Default")
      (node (ref "LED47") (pin "2") (pinfunction "DOUT_2") (pintype "passive"))
      (node (ref "LED48") (pin "4") (pinfunction "DIN_4") (pintype "passive"))
    )
    (net (code "97") (name "Net-(LED48-DOUT)") (class "Default")
      (node (ref "LED48") (pin "2") (pinfunction "DOUT_2") (pintype "passive"))
      (node (ref "LED49") (pin "4") (pinfunction "DIN_4") (pintype "passive"))
    )
    (net (code "98") (name "Net-(LED49-DOUT)") (class "Default")
      (node (ref "LED49") (pin "2") (pinfunction "DOUT_2") (pintype "passive"))
      (node (ref "LED50") (pin "4") (pinfunction "DIN_4") (pintype "passive"))
    )
    (net (code "99") (name "Net-(LED50-DOUT)") (class "Default")
      (node (ref "LED50") (pin "2") (pinfunction "DOUT_2") (pintype "passive"))
      (node (ref "LED51") (pin "4") (pinfunction "DIN_4") (pintype "passive"))
    )
    (net (code "100") (name "Net-(LED51-DOUT)") (class "Default")
      (node (ref "LED51") (pin "2") (pinfunction "DOUT_2") (pintype "passive"))
      (node (ref "LED54") (pin "4") (pinfunction "DIN_4") (pintype "passive"))
    )
    (net (code "101") (name "Net-(LED52-DIN)") (class "Default")
      (node (ref "LED52") (pin "4") (pinfunction "DIN_4") (pintype "passive"))
      (node (ref "LED53") (pin "2") (pinfunction "DOUT_2") (pintype "passive"))
    )
    (net (code "102") (name "Net-(LED52-DOUT)") (class "Default")
      (node (ref "LED52") (pin "2") (pinfunction "DOUT_2") (pintype "passive"))
      (node (ref "LED55") (pin "4") (pinfunction "DIN_4") (pintype "passive"))
    )
    (net (code "103") (name "Net-(LED53-DIN)") (class "Default")
      (node (ref "LED53") (pin "4") (pinfunction "DIN_4") (pintype "passive"))
      (node (ref "LED54") (pin "2") (pinfunction "DOUT_2") (pintype "passive"))
    )
    (net (code "104") (name "Net-(LED56-DOUT)") (class "Default")
      (node (ref "H10") (pin "2") (pinfunction "2_2") (pintype "passive"))
      (node (ref "H12") (pin "2") (pinfunction "2_2") (pintype "passive"))
      (node (ref "LED56") (pin "2") (pinfunction "DOUT_2") (pintype "passive"))
      (node (ref "LED66") (pin "4") (pinfunction "DIN_4") (pintype "passive"))
    )
    (net (code "105") (name "Net-(LED57-DIN)") (class "Default")
      (node (ref "LED57") (pin "4") (pinfunction "DIN_4") (pintype "passive"))
      (node (ref "LED67") (pin "2") (pinfunction "DOUT_2") (pintype "passive"))
    )
    (net (code "106") (name "Net-(LED57-DOUT)") (class "Default")
      (node (ref "H11") (pin "2") (pinfunction "2_2") (pintype "passive"))
      (node (ref "H13") (pin "2") (pinfunction "2_2") (pintype "passive"))
      (node (ref "LED57") (pin "2") (pinfunction "DOUT_2") (pintype "passive"))
      (node (ref "LED69") (pin "4") (pinfunction "DIN_4") (pintype "passive"))
    )
    (net (code "107") (name "Net-(LED58-DIN)") (class "Default")
      (node (ref "LED58") (pin "4") (pinfunction "DIN_4") (pintype "passive"))
      (node (ref "LED61") (pin "2") (pinfunction "DOUT_2") (pintype "passive"))
    )
    (net (code "108") (name "Net-(LED58-DOUT)") (class "Default")
      (node (ref "LED58") (pin "2") (pinfunction "DOUT_2") (pintype "passive"))
      (node (ref "LED67") (pin "4") (pinfunction "DIN_4") (pintype "passive"))
    )
    (net (code "109") (name "Net-(LED59-DIN)") (class "Default")
      (node (ref "LED59") (pin "4") (pinfunction "DIN_4") (pintype "passive"))
      (node (ref "LED62") (pin "2") (pinfunction "DOUT_2") (pintype "passive"))
    )
    (net (code "110") (name "Net-(LED59-DOUT)") (class "Default")
      (node (ref "LED59") (pin "2") (pinfunction "DOUT_2") (pintype "passive"))
      (node (ref "LED60") (pin "4") (pinfunction "DIN_4") (pintype "passive"))
    )
    (net (code "111") (name "Net-(LED60-DOUT)") (class "Default")
      (node (ref "LED60") (pin "2") (pinfunction "DOUT_2") (pintype "passive"))
      (node (ref "LED61") (pin "4") (pinfunction "DIN_4") (pintype "passive"))
    )
    (net (code "112") (name "Net-(LED62-DIN)") (class "Default")
      (node (ref "LED62") (pin "4") (pinfunction "DIN_4") (pintype "passive"))
      (node (ref "LED63") (pin "2") (pinfunction "DOUT_2") (pintype "passive"))
    )
    (net (code "113") (name "Net-(LED63-DIN)") (class "Default")
      (node (ref "LED63") (pin "4") (pinfunction "DIN_4") (pintype "passive"))
      (node (ref "LED64") (pin "2") (pinfunction "DOUT_2") (pintype "passive"))
    )
    (net (code "114") (name "Net-(LED64-DIN)") (class "Default")
      (node (ref "LED64") (pin "4") (pinfunction "DIN_4") (pintype "passive"))
      (node (ref "LED65") (pin "2") (pinfunction "DOUT_2") (pintype "passive"))
    )
    (net (code "115") (name "Net-(LED65-DIN)") (class "Default")
      (node (ref "LED65") (pin "4") (pinfunction "DIN_4") (pintype "passive"))
      (node (ref "LED66") (pin "2") (pinfunction "DOUT_2") (pintype "passive"))
    )
    (net (code "116") (name "Net-(LED68-DIN)") (class "Default")
      (node (ref "LED68") (pin "4") (pinfunction "DIN_4") (pintype "passive"))
      (node (ref "LED77") (pin "2") (pinfunction "DOUT_2") (pintype "passive"))
    )
    (net (code "117") (name "Net-(LED68-DOUT)") (class "Default")
      (node (ref "LED68") (pin "2") (pinfunction "DOUT_2") (pintype "passive"))
      (node (ref "LED78") (pin "4") (pinfunction "DIN_4") (pintype "passive"))
    )
    (net (code "118") (name "Net-(LED69-DOUT)") (class "Default")
      (node (ref "LED69") (pin "2") (pinfunction "DOUT_2") (pintype "passive"))
      (node (ref "LED70") (pin "4") (pinfunction "DIN_4") (pintype "passive"))
    )
    (net (code "119") (name "Net-(LED70-DOUT)") (class "Default")
      (node (ref "LED70") (pin "2") (pinfunction "DOUT_2") (pintype "passive"))
      (node (ref "LED71") (pin "4") (pinfunction "DIN_4") (pintype "passive"))
    )
    (net (code "120") (name "Net-(LED71-DOUT)") (class "Default")
      (node (ref "LED71") (pin "2") (pinfunction "DOUT_2") (pintype "passive"))
      (node (ref "LED72") (pin "4") (pinfunction "DIN_4") (pintype "passive"))
    )
    (net (code "121") (name "Net-(LED72-DOUT)") (class "Default")
      (node (ref "LED72") (pin "2") (pinfunction "DOUT_2") (pintype "passive"))
      (node (ref "LED73") (pin "4") (pinfunction "DIN_4") (pintype "passive"))
    )
    (net (code "122") (name "Net-(LED73-DOUT)") (class "Default")
      (node (ref "LED73") (pin "2") (pinfunction "DOUT_2") (pintype "passive"))
      (node (ref "LED76") (pin "4") (pinfunction "DIN_4") (pintype "passive"))
    )
    (net (code "123") (name "Net-(LED74-DIN)") (class "Default")
      (node (ref "LED74") (pin "4") (pinfunction "DIN_4") (pintype "passive"))
      (node (ref "LED75") (pin "2") (pinfunction "DOUT_2") (pintype "passive"))
    )
    (net (code "124") (name "Net-(LED74-DOUT)") (class "Default")
      (node (ref "LED74") (pin "2") (pinfunction "DOUT_2") (pintype "passive"))
      (node (ref "LED77") (pin "4") (pinfunction "DIN_4") (pintype "passive"))
    )
    (net (code "125") (name "Net-(LED75-DIN)") (class "Default")
      (node (ref "LED75") (pin "4") (pinfunction "DIN_4") (pintype "passive"))
      (node (ref "LED76") (pin "2") (pinfunction "DOUT_2") (pintype "passive"))
    )
    (net (code "126") (name "Net-(LED78-DOUT)") (class "Default")
      (node (ref "H14") (pin "2") (pinfunction "2_2") (pintype "passive"))
      (node (ref "H16") (pin "2") (pinfunction "2_2") (pintype "passive"))
      (node (ref "LED78") (pin "2") (pinfunction "DOUT_2") (pintype "passive"))
      (node (ref "LED88") (pin "4") (pinfunction "DIN_4") (pintype "passive"))
    )
    (net (code "127") (name "Net-(LED79-DIN)") (class "Default")
      (node (ref "LED79") (pin "4") (pinfunction "DIN_4") (pintype "passive"))
      (node (ref "LED89") (pin "2") (pinfunction "DOUT_2") (pintype "passive"))
    )
    (net (code "128") (name "Net-(LED79-DOUT)") (class "Default")
      (node (ref "H15") (pin "2") (pinfunction "2_2") (pintype "passive"))
      (node (ref "H17") (pin "2") (pinfunction "2_2") (pintype "passive"))
      (node (ref "LED79") (pin "2") (pinfunction "DOUT_2") (pintype "passive"))
      (node (ref "LED91") (pin "4") (pinfunction "DIN_4") (pintype "passive"))
    )
    (net (code "129") (name "Net-(LED80-DIN)") (class "Default")
      (node (ref "LED80") (pin "4") (pinfunction "DIN_4") (pintype "passive"))
      (node (ref "LED83") (pin "2") (pinfunction "DOUT_2") (pintype "passive"))
    )
    (net (code "130") (name "Net-(LED80-DOUT)") (class "Default")
      (node (ref "LED80") (pin "2") (pinfunction "DOUT_2") (pintype "passive"))
      (node (ref "LED89") (pin "4") (pinfunction "DIN_4") (pintype "passive"))
    )
    (net (code "131") (name "Net-(LED81-DIN)") (class "Default")
      (node (ref "LED81") (pin "4") (pinfunction "DIN_4") (pintype "passive"))
      (node (ref "LED84") (pin "2") (pinfunction "DOUT_2") (pintype "passive"))
    )
    (net (code "132") (name "Net-(LED81-DOUT)") (class "Default")
      (node (ref "LED81") (pin "2") (pinfunction "DOUT_2") (pintype "passive"))
      (node (ref "LED82") (pin "4") (pinfunction "DIN_4") (pintype "passive"))
    )
    (net (code "133") (name "Net-(LED82-DOUT)") (class "Default")
      (node (ref "LED82") (pin "2") (pinfunction "DOUT_2") (pintype "passive"))
      (node (ref "LED83") (pin "4") (pinfunction "DIN_4") (pintype "passive"))
    )
    (net (code "134") (name "Net-(LED84-DIN)") (class "Default")
      (node (ref "LED84") (pin "4") (pinfunction "DIN_4") (pintype "passive"))
      (node (ref "LED85") (pin "2") (pinfunction "DOUT_2") (pintype "passive"))
    )
    (net (code "135") (name "Net-(LED85-DIN)") (class "Default")
      (node (ref "LED85") (pin "4") (pinfunction "DIN_4") (pintype "passive"))
      (node (ref "LED86") (pin "2") (pinfunction "DOUT_2") (pintype "passive"))
    )
    (net (code "136") (name "Net-(LED86-DIN)") (class "Default")
      (node (ref "LED86") (pin "4") (pinfunction "DIN_4") (pintype "passive"))
      (node (ref "LED87") (pin "2") (pinfunction "DOUT_2") (pintype "passive"))
    )
    (net (code "137") (name "Net-(LED87-DIN)") (class "Default")
      (node (ref "LED87") (pin "4") (pinfunction "DIN_4") (pintype "passive"))
      (node (ref "LED88") (pin "2") (pinfunction "DOUT_2") (pintype "passive"))
    )
    (net (code "138") (name "Net-(LED90-DIN)") (class "Default")
      (node (ref "LED90") (pin "4") (pinfunction "DIN_4") (pintype "passive"))
      (node (ref "LED99") (pin "2") (pinfunction "DOUT_2") (pintype "passive"))
    )
    (net (code "139") (name "Net-(LED91-DOUT)") (class "Default")
      (node (ref "LED91") (pin "2") (pinfunction "DOUT_2") (pintype "passive"))
      (node (ref "LED92") (pin "4") (pinfunction "DIN_4") (pintype "passive"))
    )
    (net (code "140") (name "Net-(LED92-DOUT)") (class "Default")
      (node (ref "LED92") (pin "2") (pinfunction "DOUT_2") (pintype "passive"))
      (node (ref "LED93") (pin "4") (pinfunction "DIN_4") (pintype "passive"))
    )
    (net (code "141") (name "Net-(LED93-DOUT)") (class "Default")
      (node (ref "LED93") (pin "2") (pinfunction "DOUT_2") (pintype "passive"))
      (node (ref "LED94") (pin "4") (pinfunction "DIN_4") (pintype "passive"))
    )
    (net (code "142") (name "Net-(LED94-DOUT)") (class "Default")
      (node (ref "LED94") (pin "2") (pinfunction "DOUT_2") (pintype "passive"))
      (node (ref "LED95") (pin "4") (pinfunction "DIN_4") (pintype "passive"))
    )
    (net (code "143") (name "Net-(LED95-DOUT)") (class "Default")
      (node (ref "LED95") (pin "2") (pinfunction "DOUT_2") (pintype "passive"))
      (node (ref "LED98") (pin "4") (pinfunction "DIN_4") (pintype "passive"))
    )
    (net (code "144") (name "Net-(LED96-DIN)") (class "Default")
      (node (ref "LED96") (pin "4") (pinfunction "DIN_4") (pintype "passive"))
      (node (ref "LED97") (pin "2") (pinfunction "DOUT_2") (pintype "passive"))
    )
    (net (code "145") (name "Net-(LED96-DOUT)") (class "Default")
      (node (ref "LED96") (pin "2") (pinfunction "DOUT_2") (pintype "passive"))
      (node (ref "LED99") (pin "4") (pinfunction "DIN_4") (pintype "passive"))
    )
    (net (code "146") (name "Net-(LED97-DIN)") (class "Default")
      (node (ref "LED97") (pin "4") (pinfunction "DIN_4") (pintype "passive"))
      (node (ref "LED98") (pin "2") (pinfunction "DOUT_2") (pintype "passive"))
    )
    (net (code "147") (name "Net-(LED100-DIN)") (class "Default")
      (node (ref "LED100") (pin "4") (pinfunction "DIN_4") (pintype "passive"))
      (node (ref "LED90") (pin "2") (pinfunction "DOUT_2") (pintype "passive"))
    )
    (net (code "148") (name "Net-(LED100-DOUT)") (class "Default")
      (node (ref "H18") (pin "2") (pinfunction "2_2") (pintype "passive"))
      (node (ref "LED100") (pin "2") (pinfunction "DOUT_2") (pintype "passive"))
      (node (ref "LED113") (pin "4") (pinfunction "DIN_4") (pintype "passive"))
    )
    (net (code "149") (name "Net-(LED101-DIN)") (class "Default")
      (node (ref "LED101") (pin "4") (pinfunction "DIN_4") (pintype "passive"))
      (node (ref "LED111") (pin "2") (pinfunction "DOUT_2") (pintype "passive"))
    )
    (net (code "150") (name "Net-(LED101-DOUT)") (class "Default")
      (node (ref "H19") (pin "2") (pinfunction "2_2") (pintype "passive"))
      (node (ref "LED101") (pin "2") (pinfunction "DOUT_2") (pintype "passive"))
      (node (ref "LED112") (pin "4") (pinfunction "DIN_4") (pintype "passive"))
    )
    (net (code "151") (name "Net-(LED102-DIN)") (class "Default")
      (node (ref "LED102") (pin "4") (pinfunction "DIN_4") (pintype "passive"))
      (node (ref "LED105") (pin "2") (pinfunction "DOUT_2") (pintype "passive"))
    )
    (net (code "152") (name "Net-(LED102-DOUT)") (class "Default")
      (node (ref "LED102") (pin "2") (pinfunction "DOUT_2") (pintype "passive"))
      (node (ref "LED111") (pin "4") (pinfunction "DIN_4") (pintype "passive"))
    )
    (net (code "153") (name "Net-(LED103-DIN)") (class "Default")
      (node (ref "LED103") (pin "4") (pinfunction "DIN_4") (pintype "passive"))
      (node (ref "LED106") (pin "2") (pinfunction "DOUT_2") (pintype "passive"))
    )
    (net (code "154") (name "Net-(LED103-DOUT)") (class "Default")
      (node (ref "LED103") (pin "2") (pinfunction "DOUT_2") (pintype "passive"))
      (node (ref "LED104") (pin "4") (pinfunction "DIN_4") (pintype "passive"))
    )
    (net (code "155") (name "Net-(LED104-DOUT)") (class "Default")
      (node (ref "LED104") (pin "2") (pinfunction "DOUT_2") (pintype "passive"))
      (node (ref "LED105") (pin "4") (pinfunction "DIN_4") (pintype "passive"))
    )
    (net (code "156") (name "Net-(LED106-DIN)") (class "Default")
      (node (ref "LED106") (pin "4") (pinfunction "DIN_4") (pintype "passive"))
      (node (ref "LED107") (pin "2") (pinfunction "DOUT_2") (pintype "passive"))
    )
    (net (code "157") (name "Net-(LED107-DIN)") (class "Default")
      (node (ref "LED107") (pin "4") (pinfunction "DIN_4") (pintype "passive"))
      (node (ref "LED108") (pin "2") (pinfunction "DOUT_2") (pintype "passive"))
    )
    (net (code "158") (name "Net-(LED108-DIN)") (class "Default")
      (node (ref "LED108") (pin "4") (pinfunction "DIN_4") (pintype "passive"))
      (node (ref "LED109") (pin "2") (pinfunction "DOUT_2") (pintype "passive"))
    )
    (net (code "159") (name "Net-(LED109-DIN)") (class "Default")
      (node (ref "LED109") (pin "4") (pinfunction "DIN_4") (pintype "passive"))
      (node (ref "LED110") (pin "2") (pinfunction "DOUT_2") (pintype "passive"))
    )
    (net (code "160") (name "Net-(LED110-DIN)") (class "Default")
      (node (ref "H20") (pin "2") (pinfunction "2_2") (pintype "passive"))
      (node (ref "LED110") (pin "4") (pinfunction "DIN_4") (pintype "passive"))
      (node (ref "LED113") (pin "2") (pinfunction "DOUT_2") (pintype "passive"))
    )
    (net (code "161") (name "Net-(LED114-DIN)") (class "Default")
      (node (ref "H3") (pin "2") (pinfunction "2_2") (pintype "passive"))
      (node (ref "LED114") (pin "4") (pinfunction "DIN_4") (pintype "passive"))
      (node (ref "LED3") (pin "2") (pinfunction "DOUT_2") (pintype "passive"))
    )
    (net (code "162") (name "Net-(LED114-DOUT)") (class "Default")
      (node (ref "H4") (pin "2") (pinfunction "2_2") (pintype "passive"))
      (node (ref "LED114") (pin "2") (pinfunction "DOUT_2") (pintype "passive"))
      (node (ref "LED22") (pin "4") (pinfunction "DIN_4") (pintype "passive"))
    )
    (net (code "163") (name "Net-(LED115-DIN)") (class "Default")
      (node (ref "H23") (pin "1") (pinfunction "1_1") (pintype "passive"))
      (node (ref "JP3") (pin "1") (pinfunction "1_1") (pintype "passive"))
      (node (ref "LED115") (pin "4") (pinfunction "DIN_4") (pintype "passive"))
    )
    (net (code "164") (name "Net-(LED115-DOUT)") (class "Default")
      (node (ref "H2") (pin "2") (pinfunction "2_2") (pintype "passive"))
      (node (ref "LED115") (pin "2") (pinfunction "DOUT_2") (pintype "passive"))
      (node (ref "LED8") (pin "4") (pinfunction "DIN_4") (pintype "passive"))
    )
    (net (code "165") (name "Net-(LED116-+)") (class "Default")
      (node (ref "LED116") (pin "2") (pinfunction "+_2") (pintype "passive"))
      (node (ref "R13") (pin "2") (pinfunction "2_2") (pintype "passive"))
    )
    (net (code "166") (name "Net-(M1-RST)") (class "Default")
      (node (ref "ESPRST") (pin "2") (pinfunction "2_2") (pintype "passive"))
      (node (ref "M1") (pin "6") (pinfunction "RST_6") (pintype "passive"))
    )
    (net (code "167") (name "Net-(Q2-B)") (class "Default")
      (node (ref "Q2") (pin "1") (pinfunction "B_1") (pintype "passive"))
      (node (ref "R5") (pin "2") (pinfunction "2_2") (pintype "passive"))
      (node (ref "R6") (pin "1") (pinfunction "1_1") (pintype "passive"))
    )
    (net (code "168") (name "Net-(Q2-C)") (class "Default")
      (node (ref "JP5") (pin "1") (pinfunction "1_1") (pintype "passive"))
      (node (ref "Q2") (pin "3") (pinfunction "C_3") (pintype "passive"))
      (node (ref "R8") (pin "1") (pinfunction "1_1") (pintype "passive"))
    )
    (net (code "169") (name "Net-(Q2-E)") (class "Default")
      (node (ref "JP1") (pin "1") (pinfunction "1_1") (pintype "passive"))
      (node (ref "Q2") (pin "2") (pinfunction "E_2") (pintype "passive"))
      (node (ref "R10") (pin "2") (pinfunction "2_2") (pintype "passive"))
    )
    (net (code "170") (name "Net-(QBOOT-Pad2)") (class "Default")
      (node (ref "QBOOT") (pin "2") (pinfunction "2_2") (pintype "passive"))
      (node (ref "R11") (pin "2") (pinfunction "2_2") (pintype "passive"))
    )
    (net (code "171") (name "Net-(QU1-USB_DM)") (class "Default")
      (node (ref "QU1") (pin "46") (pinfunction "USB_DM_46") (pintype "passive"))
      (node (ref "R9") (pin "1") (pinfunction "1_1") (pintype "passive"))
    )
    (net (code "172") (name "Net-(QU1-USB_DP)") (class "Default")
      (node (ref "QU1") (pin "47") (pinfunction "USB_DP_47") (pintype "passive"))
      (node (ref "R7") (pin "1") (pinfunction "1_1") (pintype "passive"))
    )
    (net (code "173") (name "Net-(U1-ADDR)") (class "Default")
      (node (ref "R1") (pin "1") (pinfunction "1_1") (pintype "passive"))
      (node (ref "U1") (pin "2") (pinfunction "ADDR_2") (pintype "passive"))
    )
    (net (code "174") (name "Net-(U1-DVI)") (class "Default")
      (node (ref "C7") (pin "1") (pinfunction "1_1") (pintype "passive"))
      (node (ref "R2") (pin "1") (pinfunction "1_1") (pintype "passive"))
      (node (ref "U1") (pin "5") (pinfunction "DVI_5") (pintype "passive"))
    )
    (net (code "175") (name "Net-(U3-VBAT)") (class "Default")
      (node (ref "BT1") (pin "1") (pinfunction "1_1") (pintype "passive"))
      (node (ref "U3") (pin "3") (pinfunction "VBAT_3") (pintype "passive"))
    )
    (net (code "176") (name "Net-(U3-X1)") (class "Default")
      (node (ref "U3") (pin "1") (pinfunction "X1_1") (pintype "passive"))
      (node (ref "X1") (pin "1") (pinfunction "OSC1_1") (pintype "passive"))
    )
    (net (code "177") (name "Net-(U3-X2)") (class "Default")
      (node (ref "U3") (pin "2") (pinfunction "X2_2") (pintype "passive"))
      (node (ref "X1") (pin "2") (pinfunction "OSC2_2") (pintype "passive"))
    )
    (net (code "178") (name "VCC") (class "Default")
      (node (ref "C10") (pin "2") (pinfunction "2_2") (pintype "passive"))
      (node (ref "C125") (pin "2") (pinfunction "2_2") (pintype "passive"))
      (node (ref "C126") (pin "2") (pinfunction "2_2") (pintype "passive"))
      (node (ref "C127") (pin "2") (pinfunction "2_2") (pintype "passive"))
      (node (ref "C128") (pin "2") (pinfunction "2_2") (pintype "passive"))
      (node (ref "C129") (pin "2") (pinfunction "2_2") (pintype "passive"))
      (node (ref "C130") (pin "1") (pinfunction "1_1") (pintype "passive"))
      (node (ref "C131") (pin "2") (pinfunction "2_2") (pintype "passive"))
      (node (ref "C132") (pin "2") (pinfunction "2_2") (pintype "passive"))
      (node (ref "C133") (pin "2") (pinfunction "2_2") (pintype "passive"))
      (node (ref "C3") (pin "1") (pinfunction "1_1") (pintype "passive"))
      (node (ref "C6") (pin "2") (pinfunction "2_2") (pintype "passive"))
      (node (ref "C9") (pin "1") (pinfunction "1_1") (pintype "passive"))
      (node (ref "H21") (pin "2") (pinfunction "2_2") (pintype "passive"))
      (node (ref "M1") (pin "8") (pinfunction "VCC_8") (pintype "passive"))
      (node (ref "QU1") (pin "1") (pinfunction "IOVDD_1") (pintype "passive"))
      (node (ref "QU1") (pin "10") (pinfunction "IOVDD_10") (pintype "passive"))
      (node (ref "QU1") (pin "22") (pinfunction "IOVDD_22") (pintype "passive"))
      (node (ref "QU1") (pin "33") (pinfunction "IOVDD_33") (pintype "passive"))
      (node (ref "QU1") (pin "42") (pinfunction "IOVDD_42") (pintype "passive"))
      (node (ref "QU1") (pin "43") (pinfunction "ADC_AVDD_43") (pintype "passive"))
      (node (ref "QU1") (pin "44") (pinfunction "VREG_IN_44") (pintype "passive"))
      (node (ref "QU1") (pin "48") (pinfunction "USB_VDD_48") (pintype "passive"))
      (node (ref "QU1") (pin "49") (pinfunction "IOVDD_49") (pintype "passive"))
      (node (ref "QU2") (pin "8") (pinfunction "VCC_8") (pintype "passive"))
      (node (ref "R12") (pin "1") (pinfunction "1_1") (pintype "passive"))
      (node (ref "R2") (pin "2") (pinfunction "2_2") (pintype "passive"))
      (node (ref "R3") (pin "1") (pinfunction "1_1") (pintype "passive"))
      (node (ref "R4") (pin "1") (pinfunction "1_1") (pintype "passive"))
      (node (ref "RPSWD") (pin "1") (pinfunction "1_1") (pintype "passive"))
      (node (ref "U1") (pin "1") (pinfunction "VCC_1") (pintype "passive"))
      (node (ref "U2") (pin "2") (pinfunction "Out_2") (pintype "passive"))
      (node (ref "U3") (pin "8") (pinfunction "VCC_8") (pintype "passive"))
    )
    (net (code "179") (name "unconnected-(1-Pad3V3(OUT))") (class "Default")
      (node (ref "1") (pin "3V3(OUT)") (pinfunction "3V3(OUT)_3V3(OUT)") (pintype "passive"))
    )
    (net (code "180") (name "unconnected-(1-Pad3V3_EN)") (class "Default")
      (node (ref "1") (pin "3V3_EN") (pinfunction "3V3_EN_3V3_EN") (pintype "passive"))
    )
    (net (code "181") (name "unconnected-(1-PadADC_VREF)") (class "Default")
      (node (ref "1") (pin "ADC_VREF") (pinfunction "ADC_VREF_ADC_VREF") (pintype "passive"))
    )
    (net (code "182") (name "unconnected-(1-PadGND3)") (class "Default")
      (node (ref "1") (pin "GND3") (pinfunction "GND3_GND3") (pintype "passive"))
    )
    (net (code "183") (name "unconnected-(1-PadGND6)") (class "Default")
      (node (ref "1") (pin "GND6") (pinfunction "GND6_GND6") (pintype "passive"))
    )
    (net (code "184") (name "unconnected-(1-PadGND7)") (class "Default")
      (node (ref "1") (pin "GND7") (pinfunction "GND7_GND7") (pintype "passive"))
    )
    (net (code "185") (name "unconnected-(1-PadGND8)") (class "Default")
      (node (ref "1") (pin "GND8") (pinfunction "GND8_GND8") (pintype "passive"))
    )
    (net (code "186") (name "unconnected-(1-PadGP4)") (class "Default")
      (node (ref "1") (pin "GP4") (pinfunction "GP4_GP4") (pintype "passive"))
    )
    (net (code "187") (name "unconnected-(1-PadGP5)") (class "Default")
      (node (ref "1") (pin "GP5") (pinfunction "GP5_GP5") (pintype "passive"))
    )
    (net (code "188") (name "unconnected-(1-PadGP6)") (class "Default")
      (node (ref "1") (pin "GP6") (pinfunction "GP6_GP6") (pintype "passive"))
    )
    (net (code "189") (name "unconnected-(1-PadGP7)") (class "Default")
      (node (ref "1") (pin "GP7") (pinfunction "GP7_GP7") (pintype "passive"))
    )
    (net (code "190") (name "unconnected-(1-PadGP8)") (class "Default")
      (node (ref "1") (pin "GP8") (pinfunction "GP8_GP8") (pintype "passive"))
    )
    (net (code "191") (name "unconnected-(1-PadGP9)") (class "Default")
      (node (ref "1") (pin "GP9") (pinfunction "GP9_GP9") (pintype "passive"))
    )
    (net (code "192") (name "unconnected-(1-PadGP10)") (class "Default")
      (node (ref "1") (pin "GP10") (pinfunction "GP10_GP10") (pintype "passive"))
    )
    (net (code "193") (name "unconnected-(1-PadGP11)") (class "Default")
      (node (ref "1") (pin "GP11") (pinfunction "GP11_GP11") (pintype "passive"))
    )
    (net (code "194") (name "unconnected-(1-PadGP12)") (class "Default")
      (node (ref "1") (pin "GP12") (pinfunction "GP12_GP12") (pintype "passive"))
    )
    (net (code "195") (name "unconnected-(1-PadGP13)") (class "Default")
      (node (ref "1") (pin "GP13") (pinfunction "GP13_GP13") (pintype "passive"))
    )
    (net (code "196") (name "unconnected-(1-PadGP14)") (class "Default")
      (node (ref "1") (pin "GP14") (pinfunction "GP14_GP14") (pintype "passive"))
    )
    (net (code "197") (name "unconnected-(1-PadGP15)") (class "Default")
      (node (ref "1") (pin "GP15") (pinfunction "GP15_GP15") (pintype "passive"))
    )
    (net (code "198") (name "unconnected-(1-PadGP17)") (class "Default")
      (node (ref "1") (pin "GP17") (pinfunction "GP17_GP17") (pintype "passive"))
    )
    (net (code "199") (name "unconnected-(1-PadGP18)") (class "Default")
      (node (ref "1") (pin "GP18") (pinfunction "GP18_GP18") (pintype "passive"))
    )
    (net (code "200") (name "unconnected-(1-PadGP19)") (class "Default")
      (node (ref "1") (pin "GP19") (pinfunction "GP19_GP19") (pintype "passive"))
    )
    (net (code "201") (name "unconnected-(1-PadGP20)") (class "Default")
      (node (ref "1") (pin "GP20") (pinfunction "GP20_GP20") (pintype "passive"))
    )
    (net (code "202") (name "unconnected-(1-PadGP21)") (class "Default")
      (node (ref "1") (pin "GP21") (pinfunction "GP21_GP21") (pintype "passive"))
    )
    (net (code "203") (name "unconnected-(1-PadGP26)") (class "Default")
      (node (ref "1") (pin "GP26") (pinfunction "GP26_GP26") (pintype "passive"))
    )
    (net (code "204") (name "unconnected-(1-PadGP27)") (class "Default")
      (node (ref "1") (pin "GP27") (pinfunction "GP27_GP27") (pintype "passive"))
    )
    (net (code "205") (name "unconnected-(1-PadGP28)") (class "Default")
      (node (ref "1") (pin "GP28") (pinfunction "GP28_GP28") (pintype "passive"))
    )
    (net (code "206") (name "unconnected-(1-PadRUN)") (class "Default")
      (node (ref "1") (pin "RUN") (pinfunction "RUN_RUN") (pintype "passive"))
    )
    (net (code "207") (name "unconnected-(1-PadSWCLK)") (class "Default")
      (node (ref "1") (pin "SWCLK") (pinfunction "SWCLK_SWCLK") (pintype "passive"))
    )
    (net (code "208") (name "unconnected-(1-PadSWDIO)") (class "Default")
      (node (ref "1") (pin "SWDIO") (pinfunction "SWDIO_SWDIO") (pintype "passive"))
    )
    (net (code "209") (name "unconnected-(1-PadVSYS)") (class "Default")
      (node (ref "1") (pin "VSYS") (pinfunction "VSYS_VSYS") (pintype "passive"))
    )
    (net (code "210") (name "unconnected-(ESPRST-Pad1)") (class "Default")
      (node (ref "ESPRST") (pin "1") (pinfunction "1_1") (pintype "passive"))
    )
    (net (code "211") (name "unconnected-(ESPRST-Pad3)") (class "Default")
      (node (ref "ESPRST") (pin "3") (pinfunction "3_3") (pintype "passive"))
    )
    (net (code "212") (name "unconnected-(LED112-DOUT-Pad2)") (class "Default")
      (node (ref "LED112") (pin "2") (pinfunction "DOUT_2") (pintype "passive"))
    )
    (net (code "213") (name "unconnected-(M1-CH_PD-Pad4)") (class "Default")
      (node (ref "M1") (pin "4") (pinfunction "CH_PD_4") (pintype "passive"))
    )
    (net (code "214") (name "unconnected-(M1-GPIO0-Pad5)") (class "Default")
      (node (ref "M1") (pin "5") (pinfunction "GPIO0_5") (pintype "passive"))
    )
    (net (code "215") (name "unconnected-(M1-GPIO2-Pad3)") (class "Default")
      (node (ref "M1") (pin "3") (pinfunction "GPIO2_3") (pintype "passive"))
    )
    (net (code "216") (name "unconnected-(QBOOT-Pad1)") (class "Default")
      (node (ref "QBOOT") (pin "1") (pinfunction "1_1") (pintype "passive"))
    )
    (net (code "217") (name "unconnected-(QBOOT-Pad3)") (class "Default")
      (node (ref "QBOOT") (pin "3") (pinfunction "3_3") (pintype "passive"))
    )
    (net (code "218") (name "unconnected-(QU2-EP-Pad9)") (class "Default")
      (node (ref "QU2") (pin "9") (pinfunction "EP_9") (pintype "passive"))
    )
    (net (code "219") (name "unconnected-(RPRST-Pad1)") (class "Default")
      (node (ref "RPRST") (pin "1") (pinfunction "1_1") (pintype "passive"))
    )
    (net (code "220") (name "unconnected-(RPRST-Pad3)") (class "Default")
      (node (ref "RPRST") (pin "3") (pinfunction "3_3") (pintype "passive"))
    )
    (net (code "221") (name "unconnected-(U1-EP-Pad7)") (class "Default")
      (node (ref "U1") (pin "7") (pinfunction "EP_7") (pintype "passive"))
    )
    (net (code "222") (name "unconnected-(U2-TAB-Pad4)") (class "Default")
      (node (ref "U2") (pin "4") (pinfunction "TAB_4") (pintype "passive"))
    )
    (net (code "223") (name "unconnected-(U3-SQW{slash}OUT-Pad7)") (class "Default")
      (node (ref "U3") (pin "7") (pinfunction "SQW/OUT_7") (pintype "passive"))
    )
  )
)
